# PX4FMUv2_4.net
KiCad netlist of a schematic drawn in EAGLE
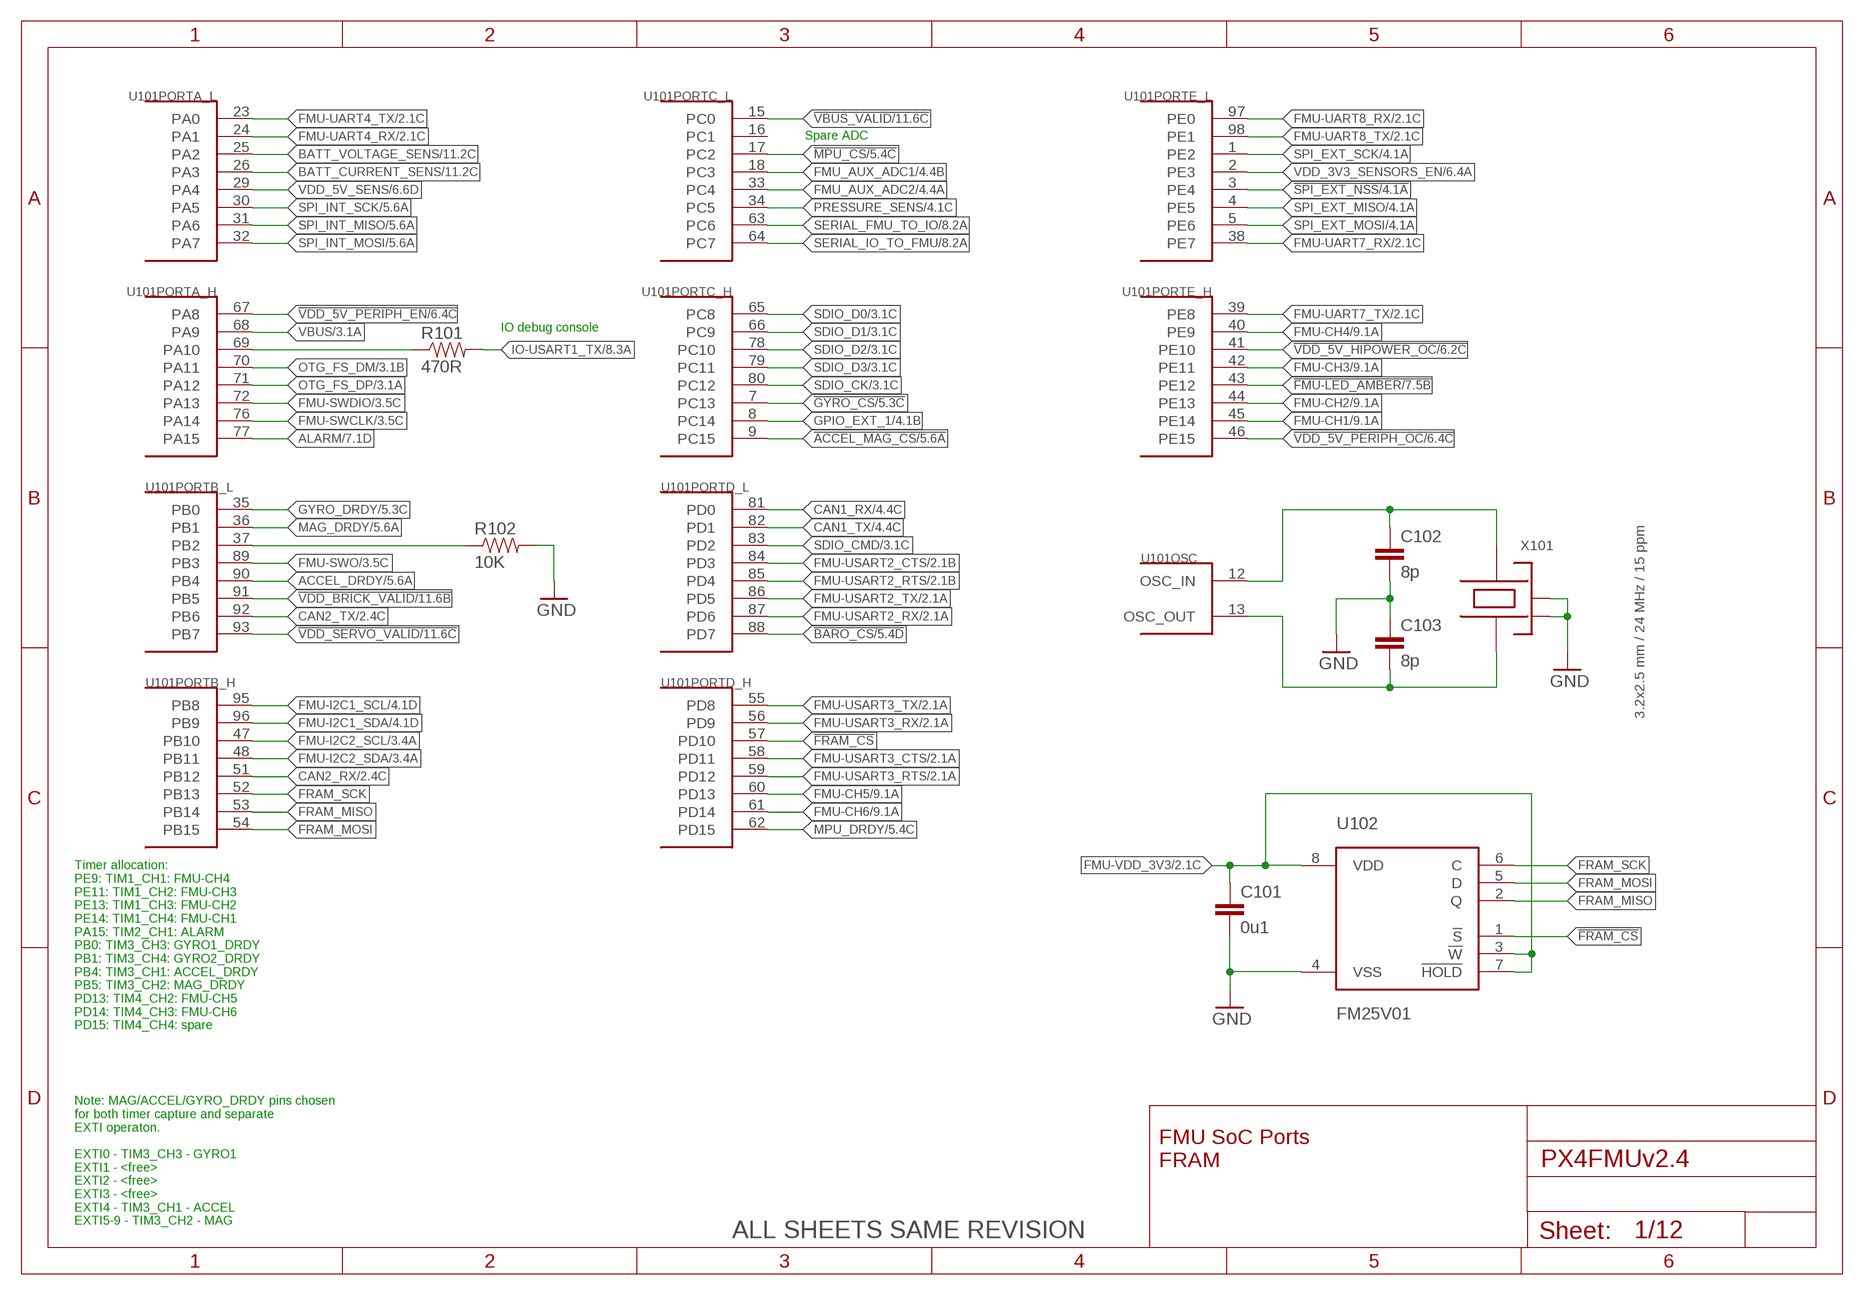
[diagram p0: schematic, sheet 1]
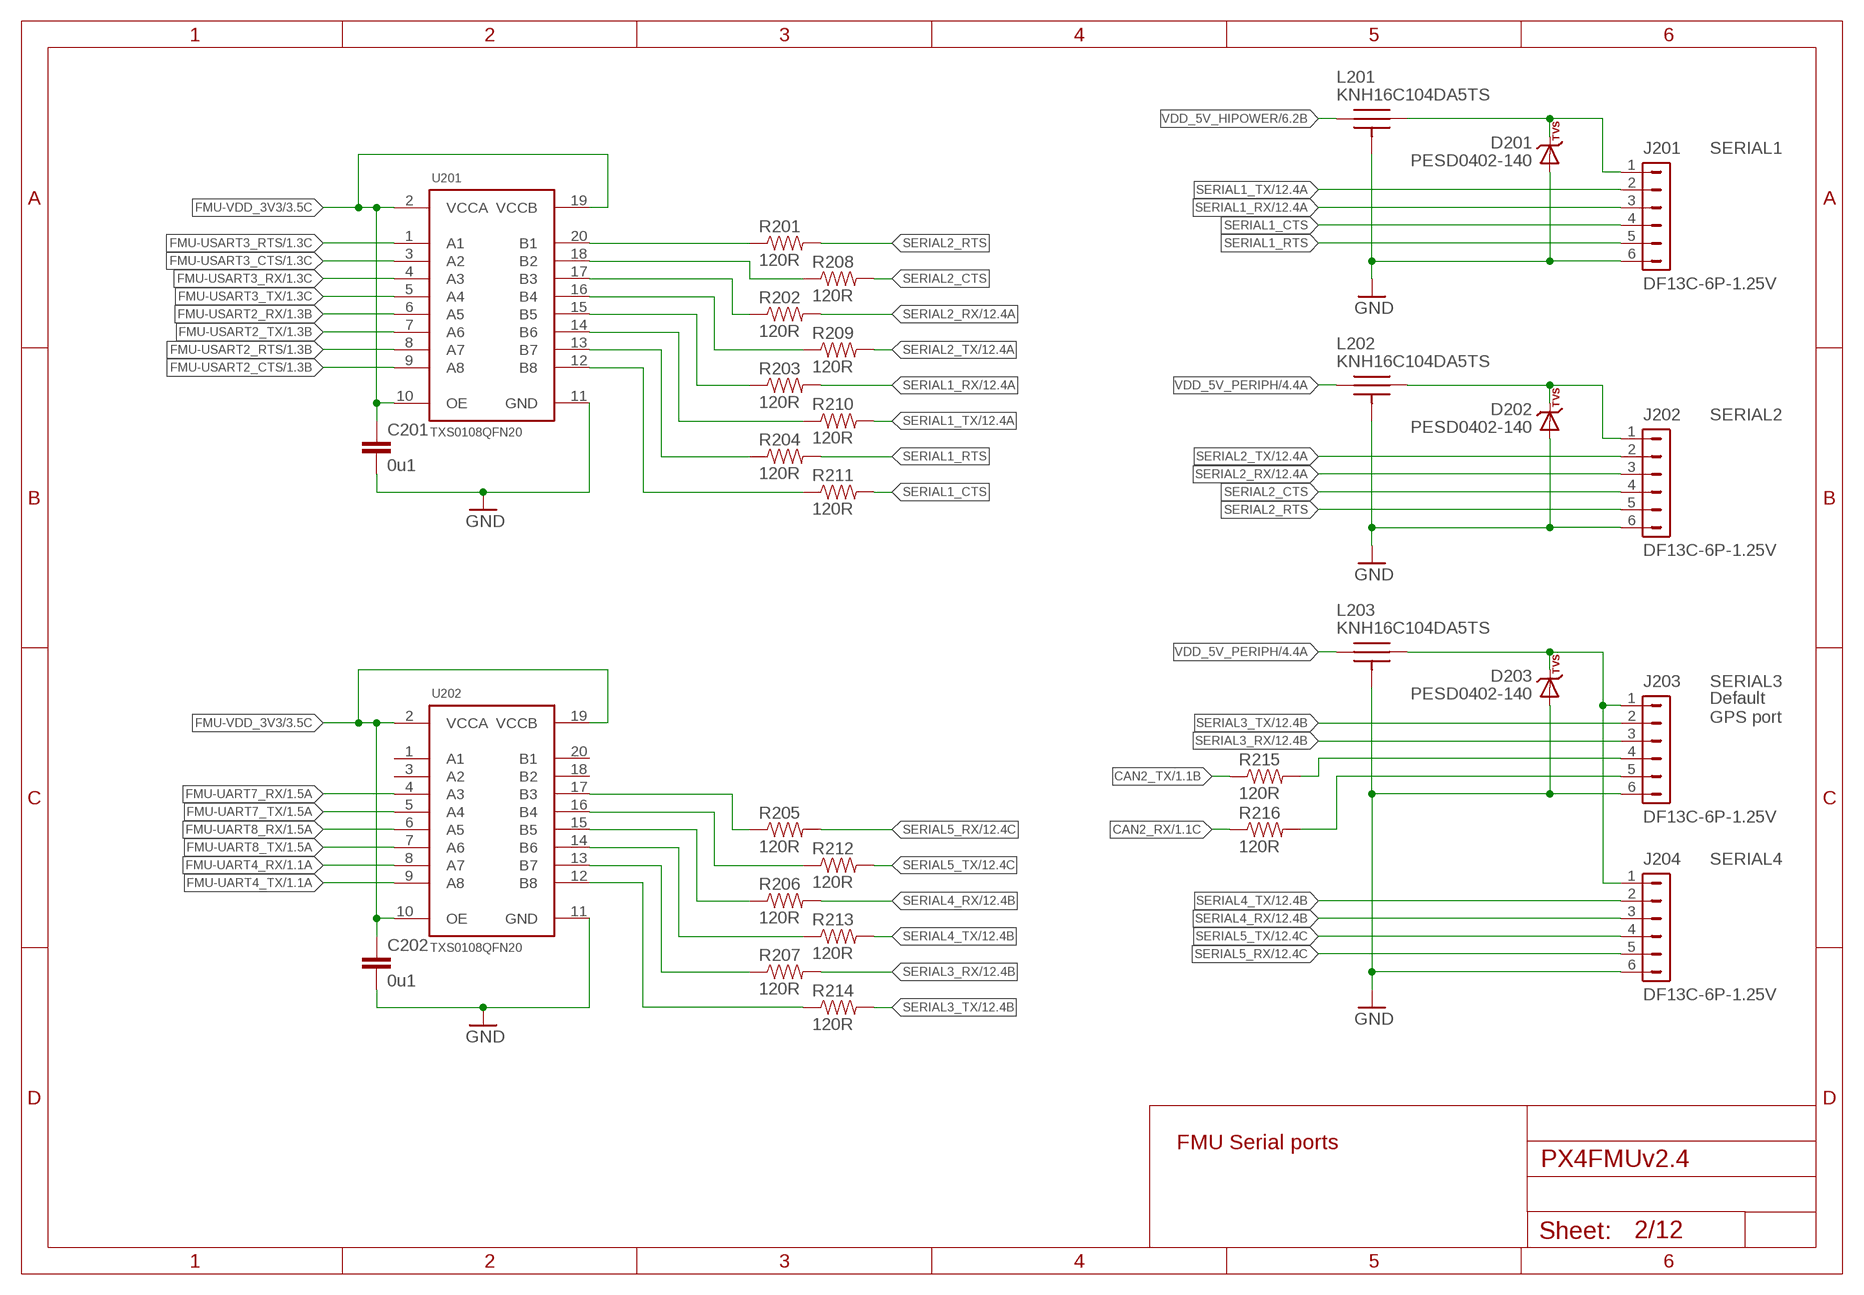
[diagram p1: schematic, sheet 2]
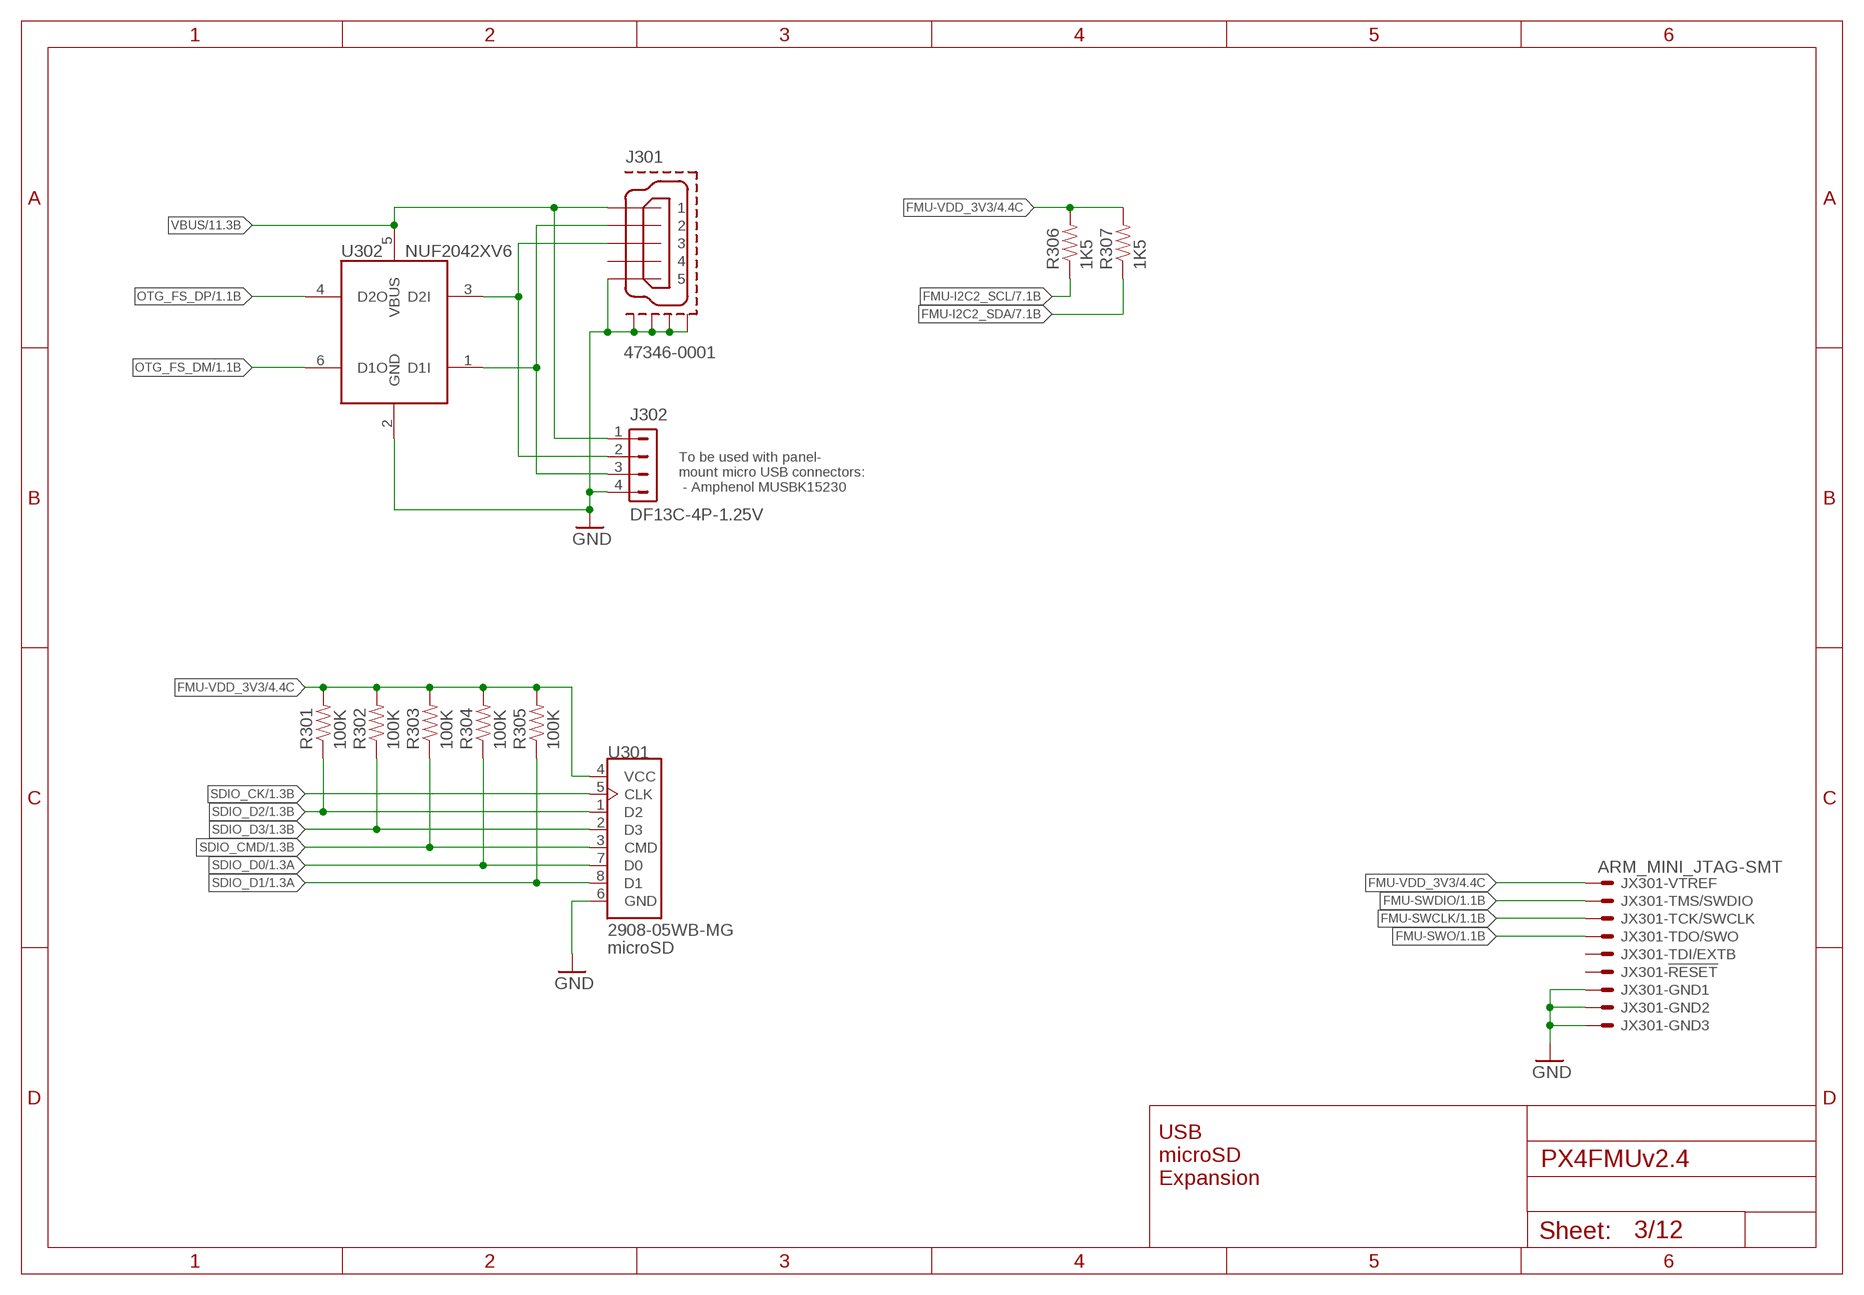
[diagram p2: schematic, sheet 3]
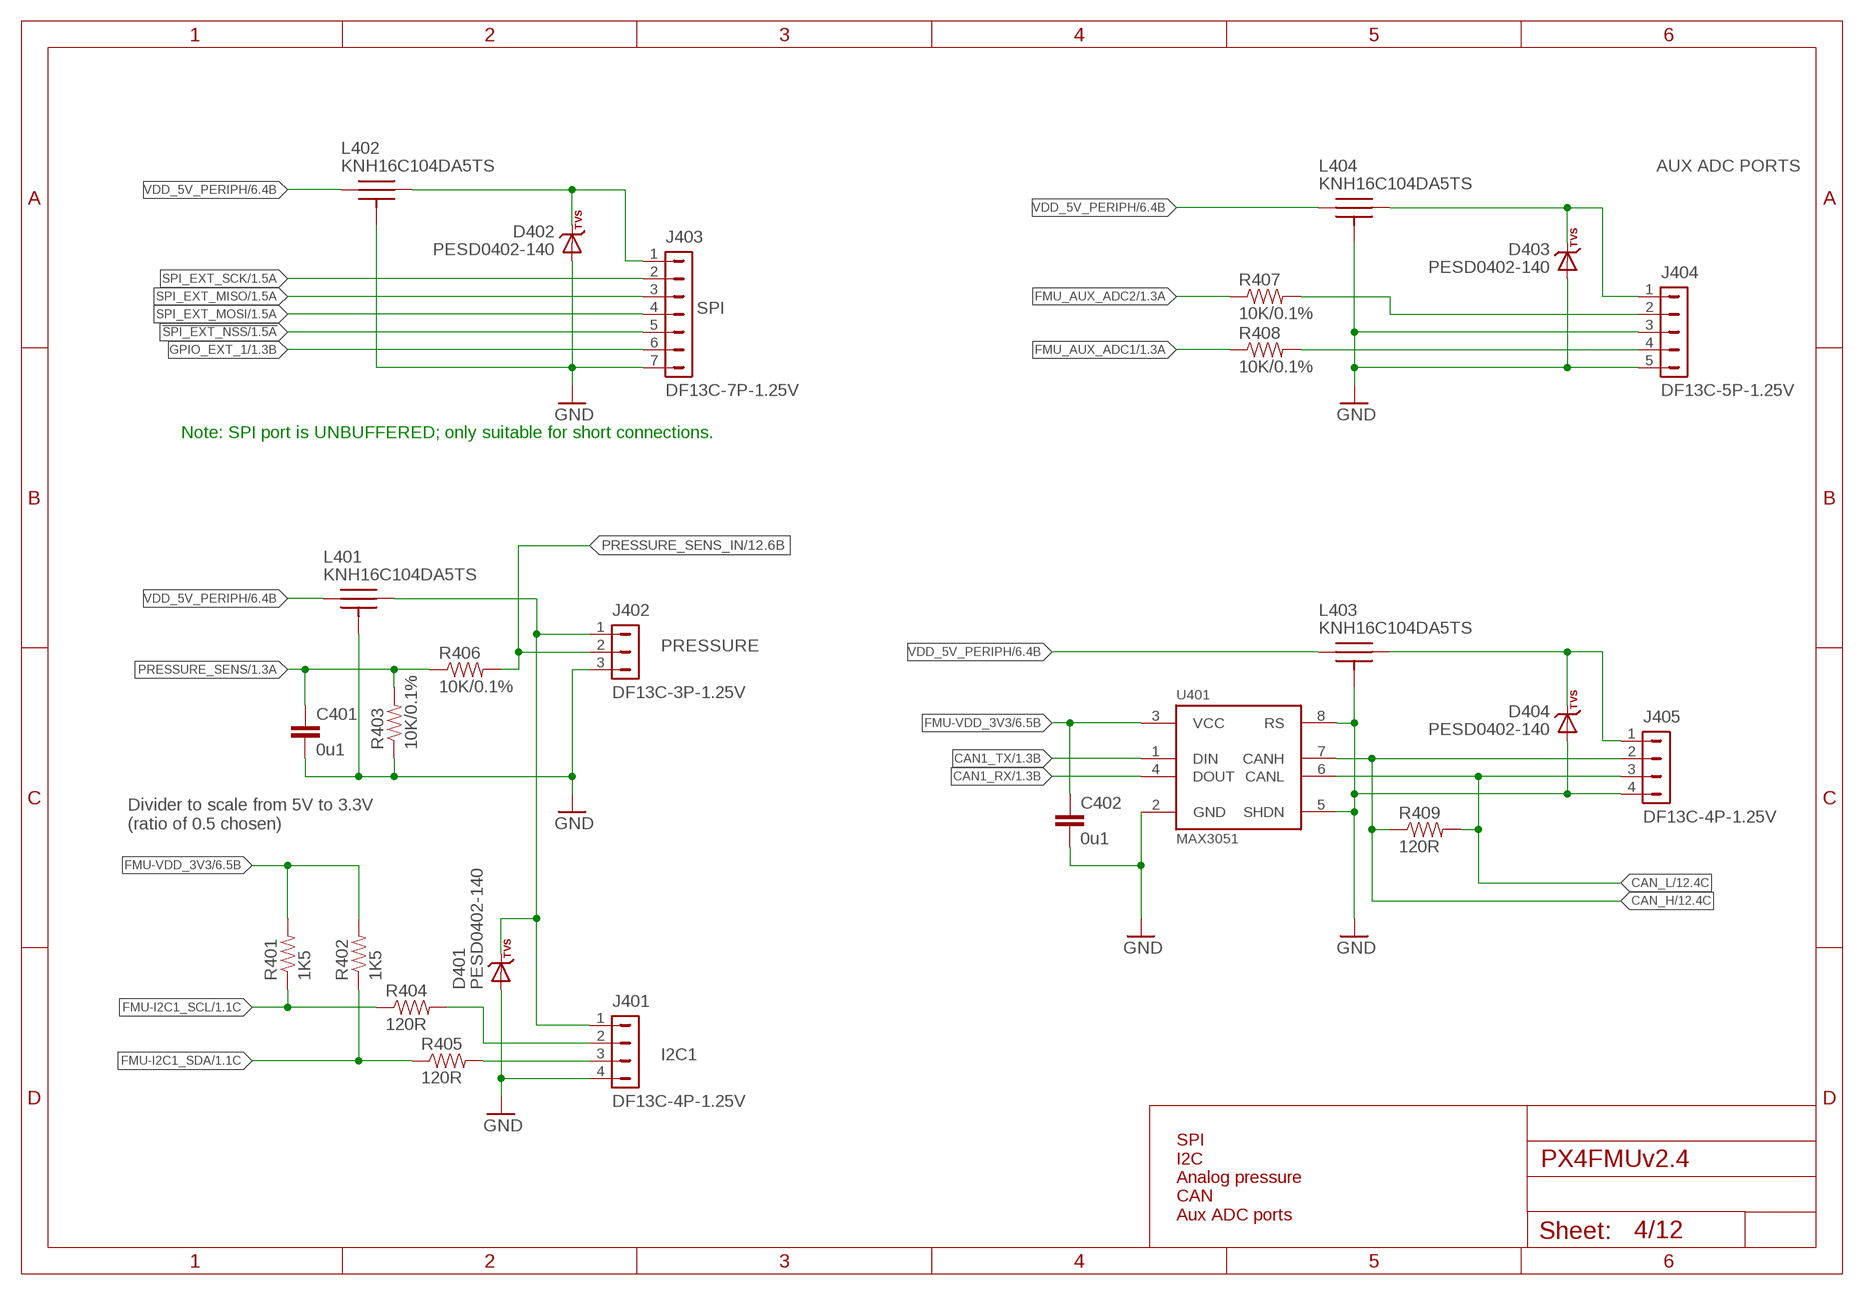
[diagram p3: schematic, sheet 4]
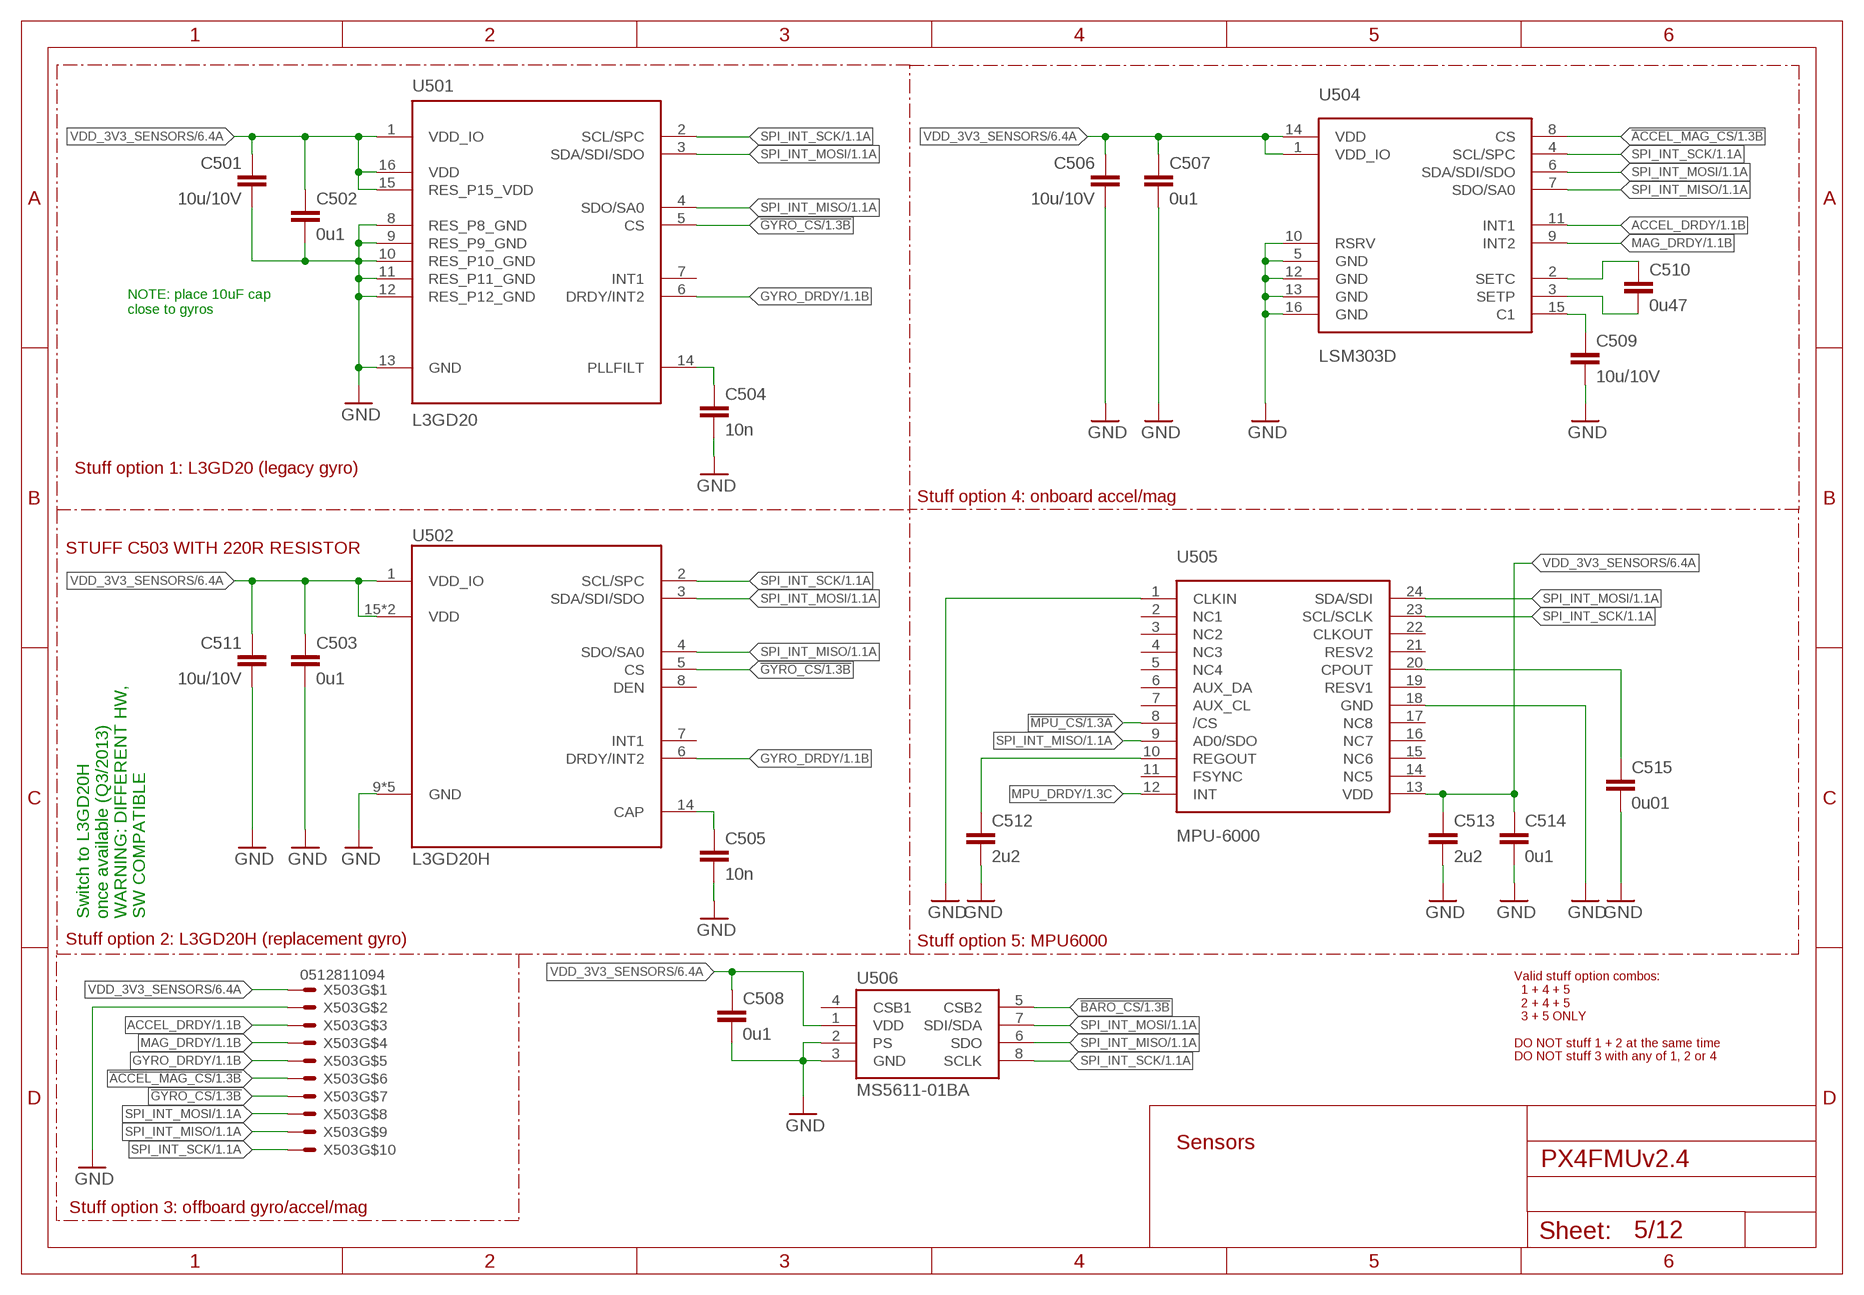
[diagram p4: schematic, sheet 5]
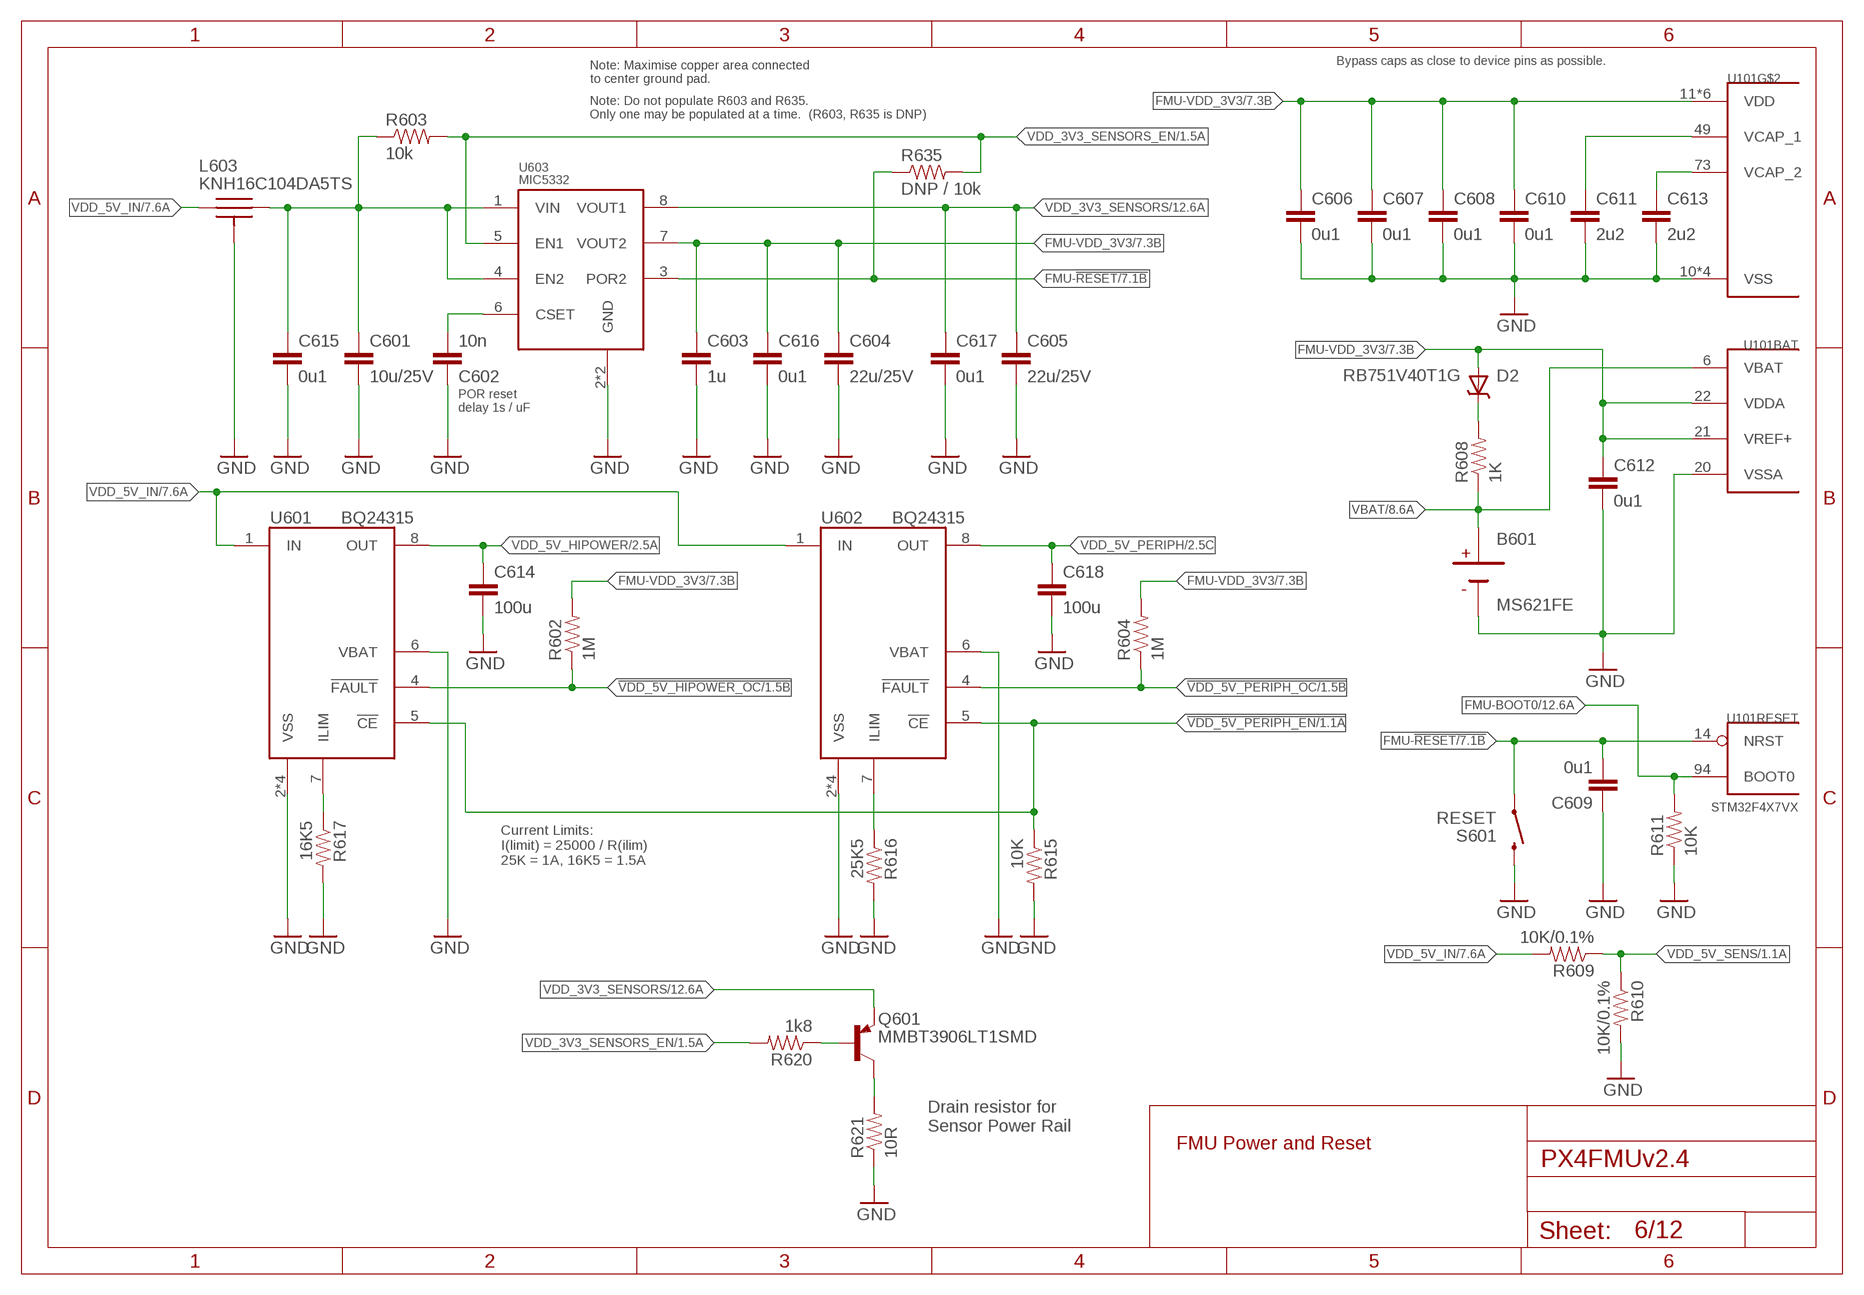
[diagram p5: schematic, sheet 6]
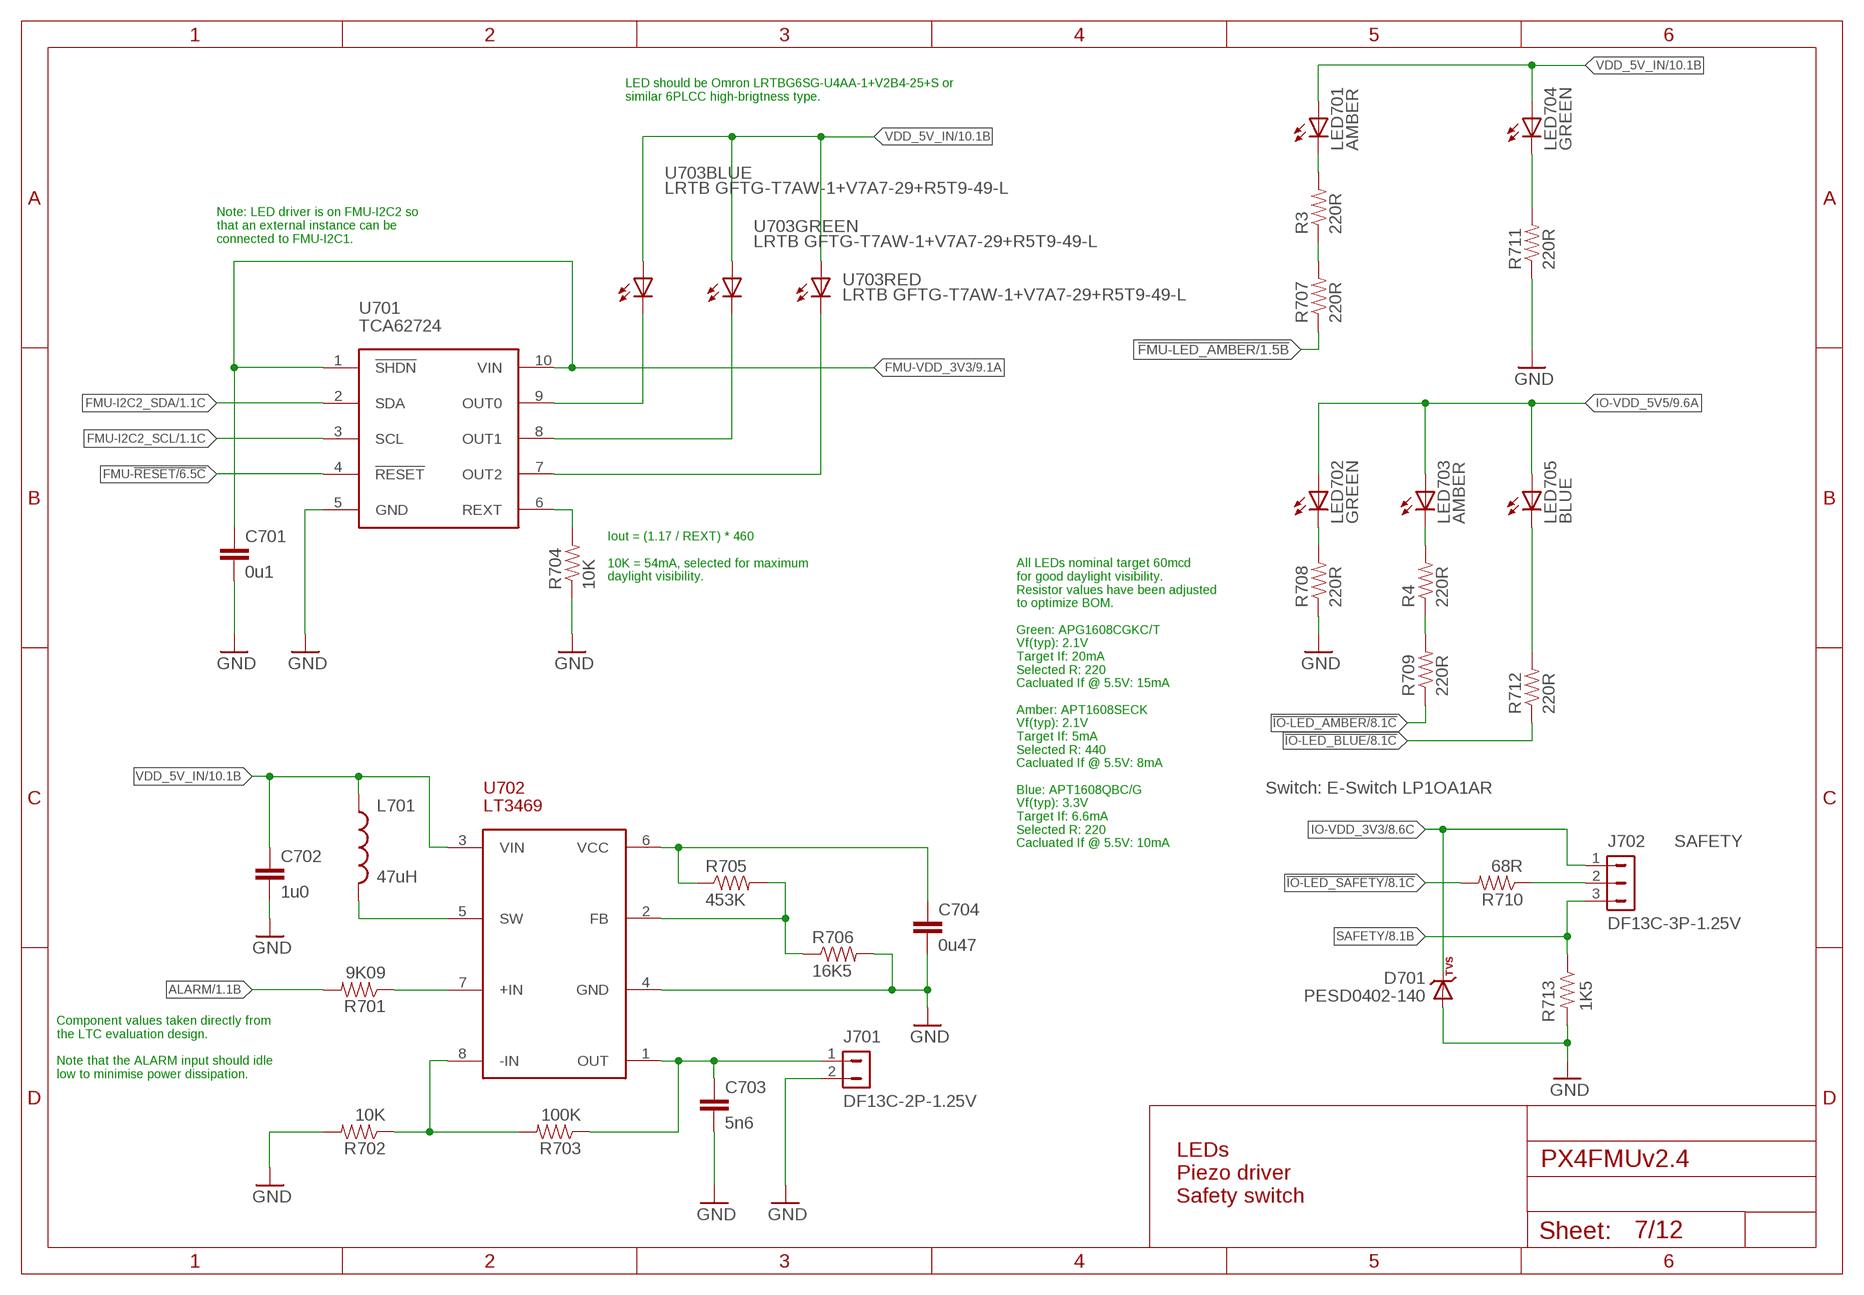
[diagram p6: schematic, sheet 7]
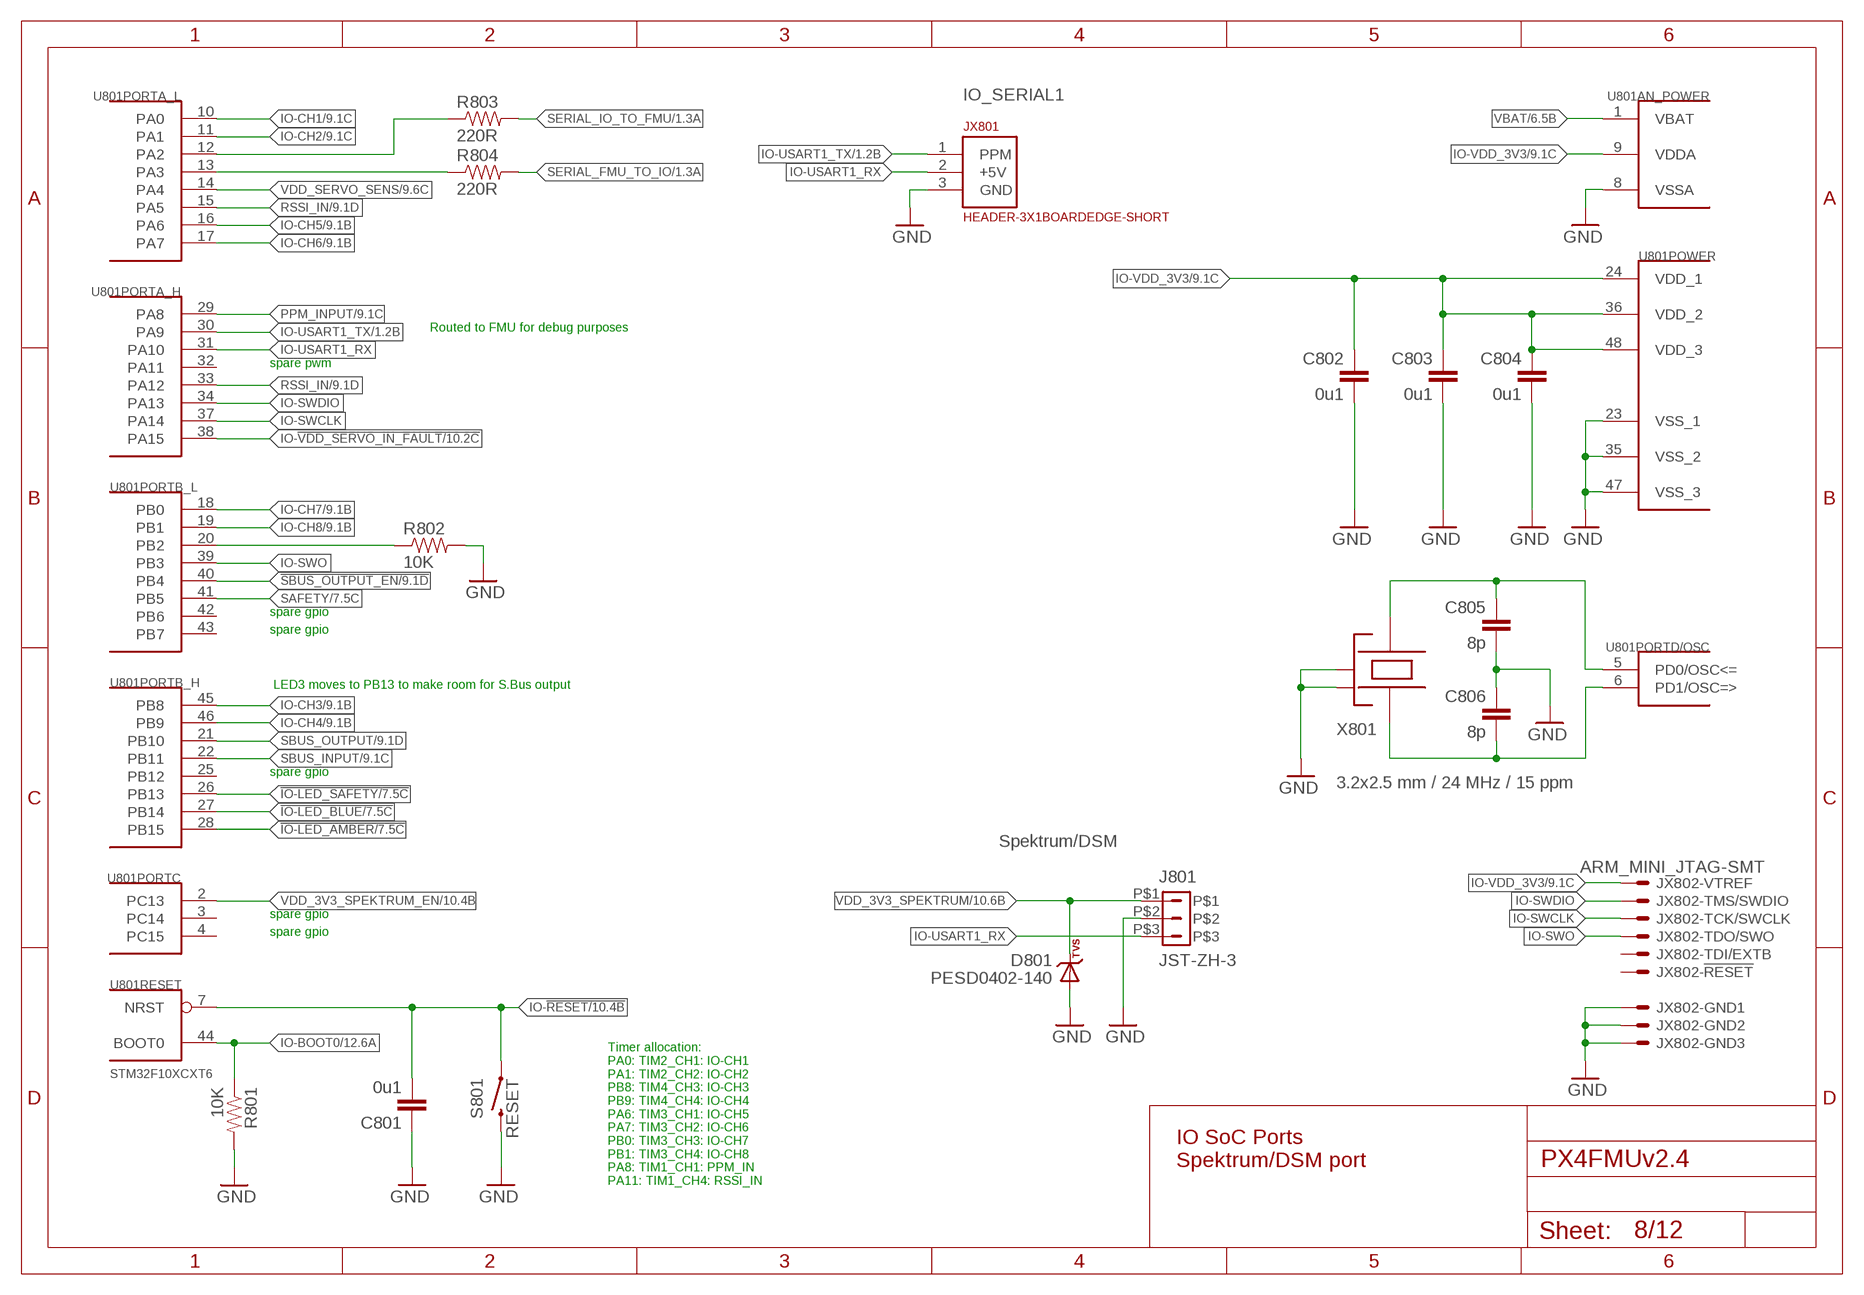
[diagram p7: schematic, sheet 8]
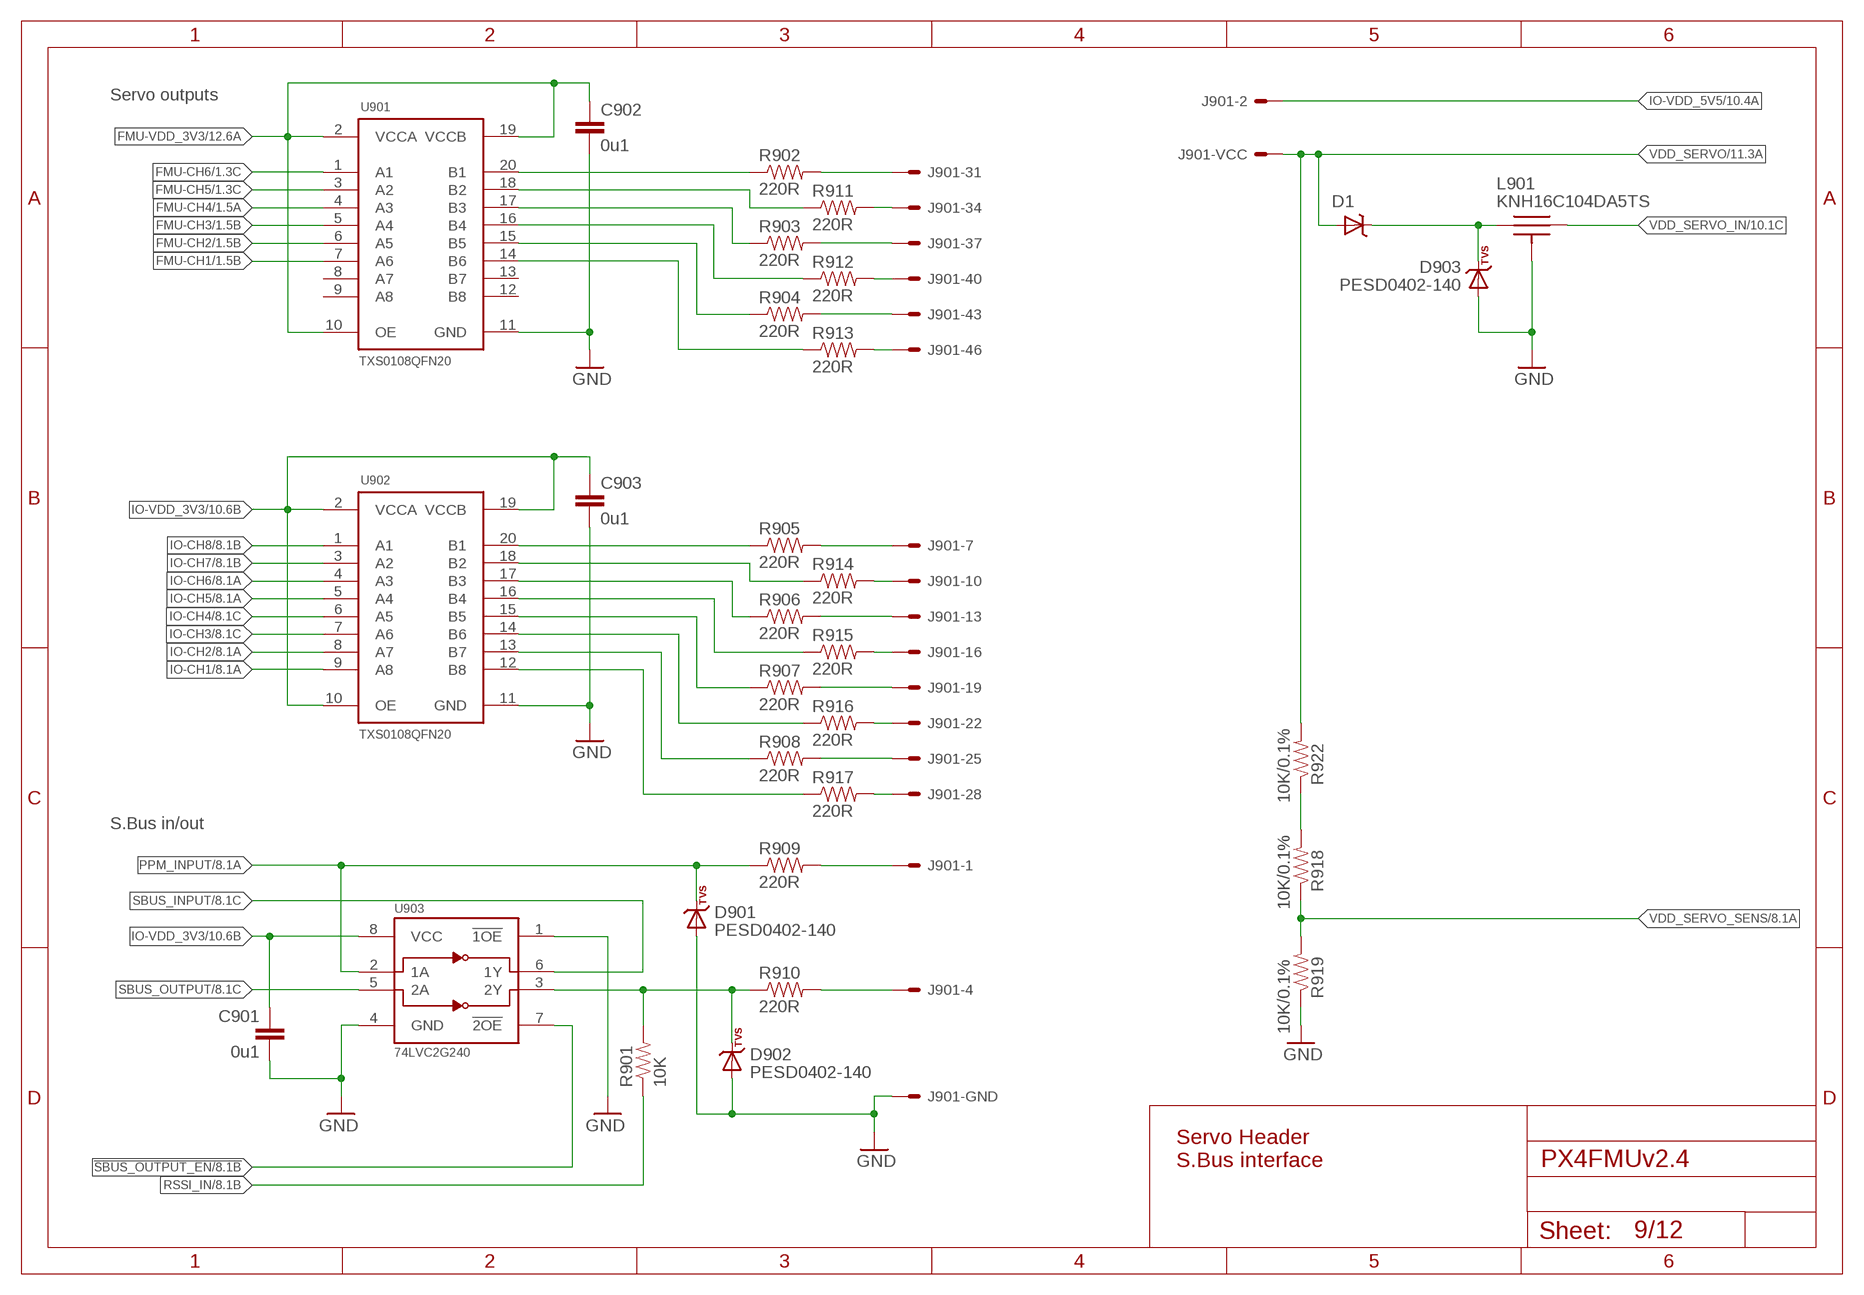
[diagram p8: schematic, sheet 9]
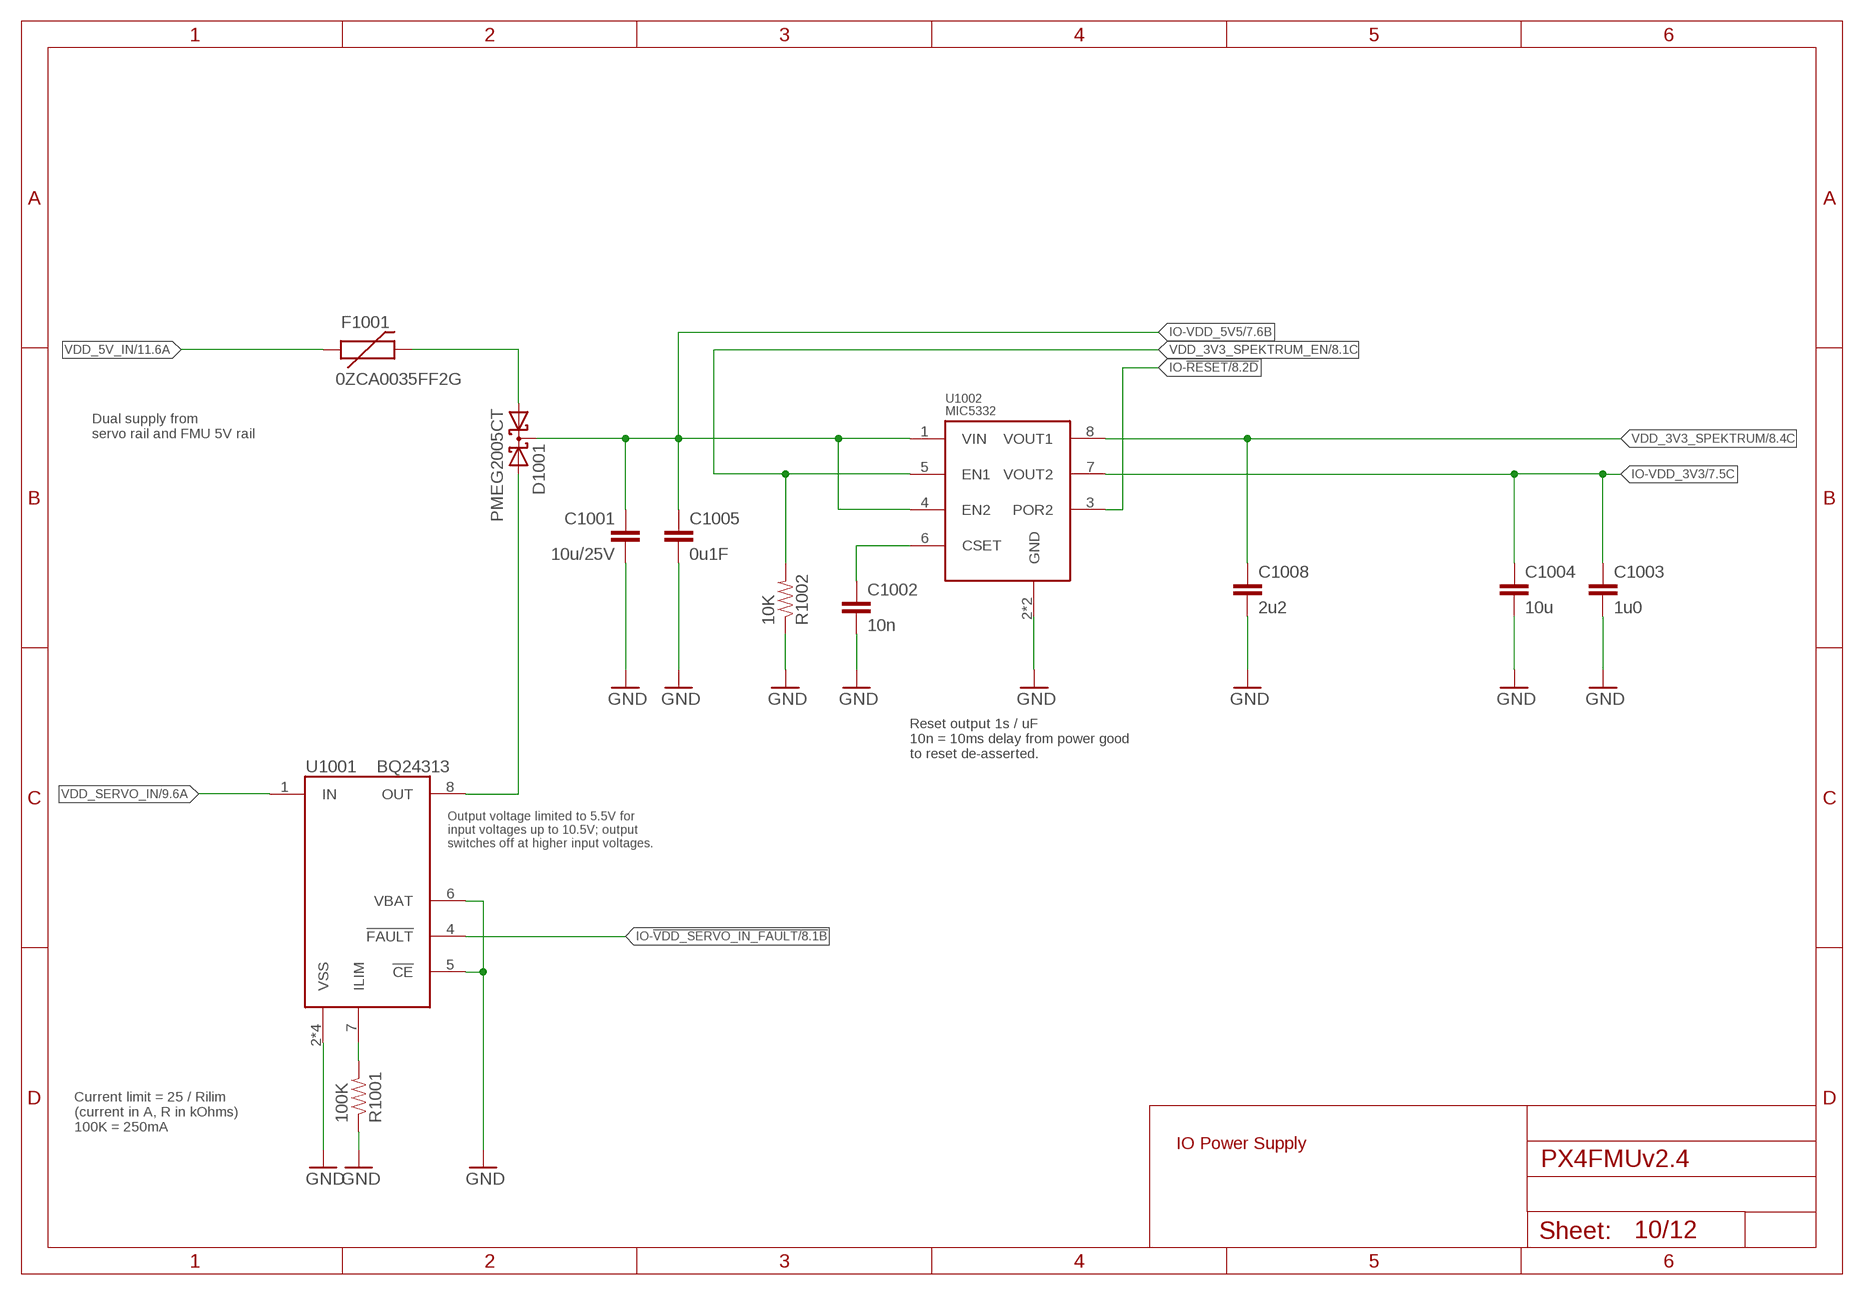
[diagram p9: schematic, sheet 10]
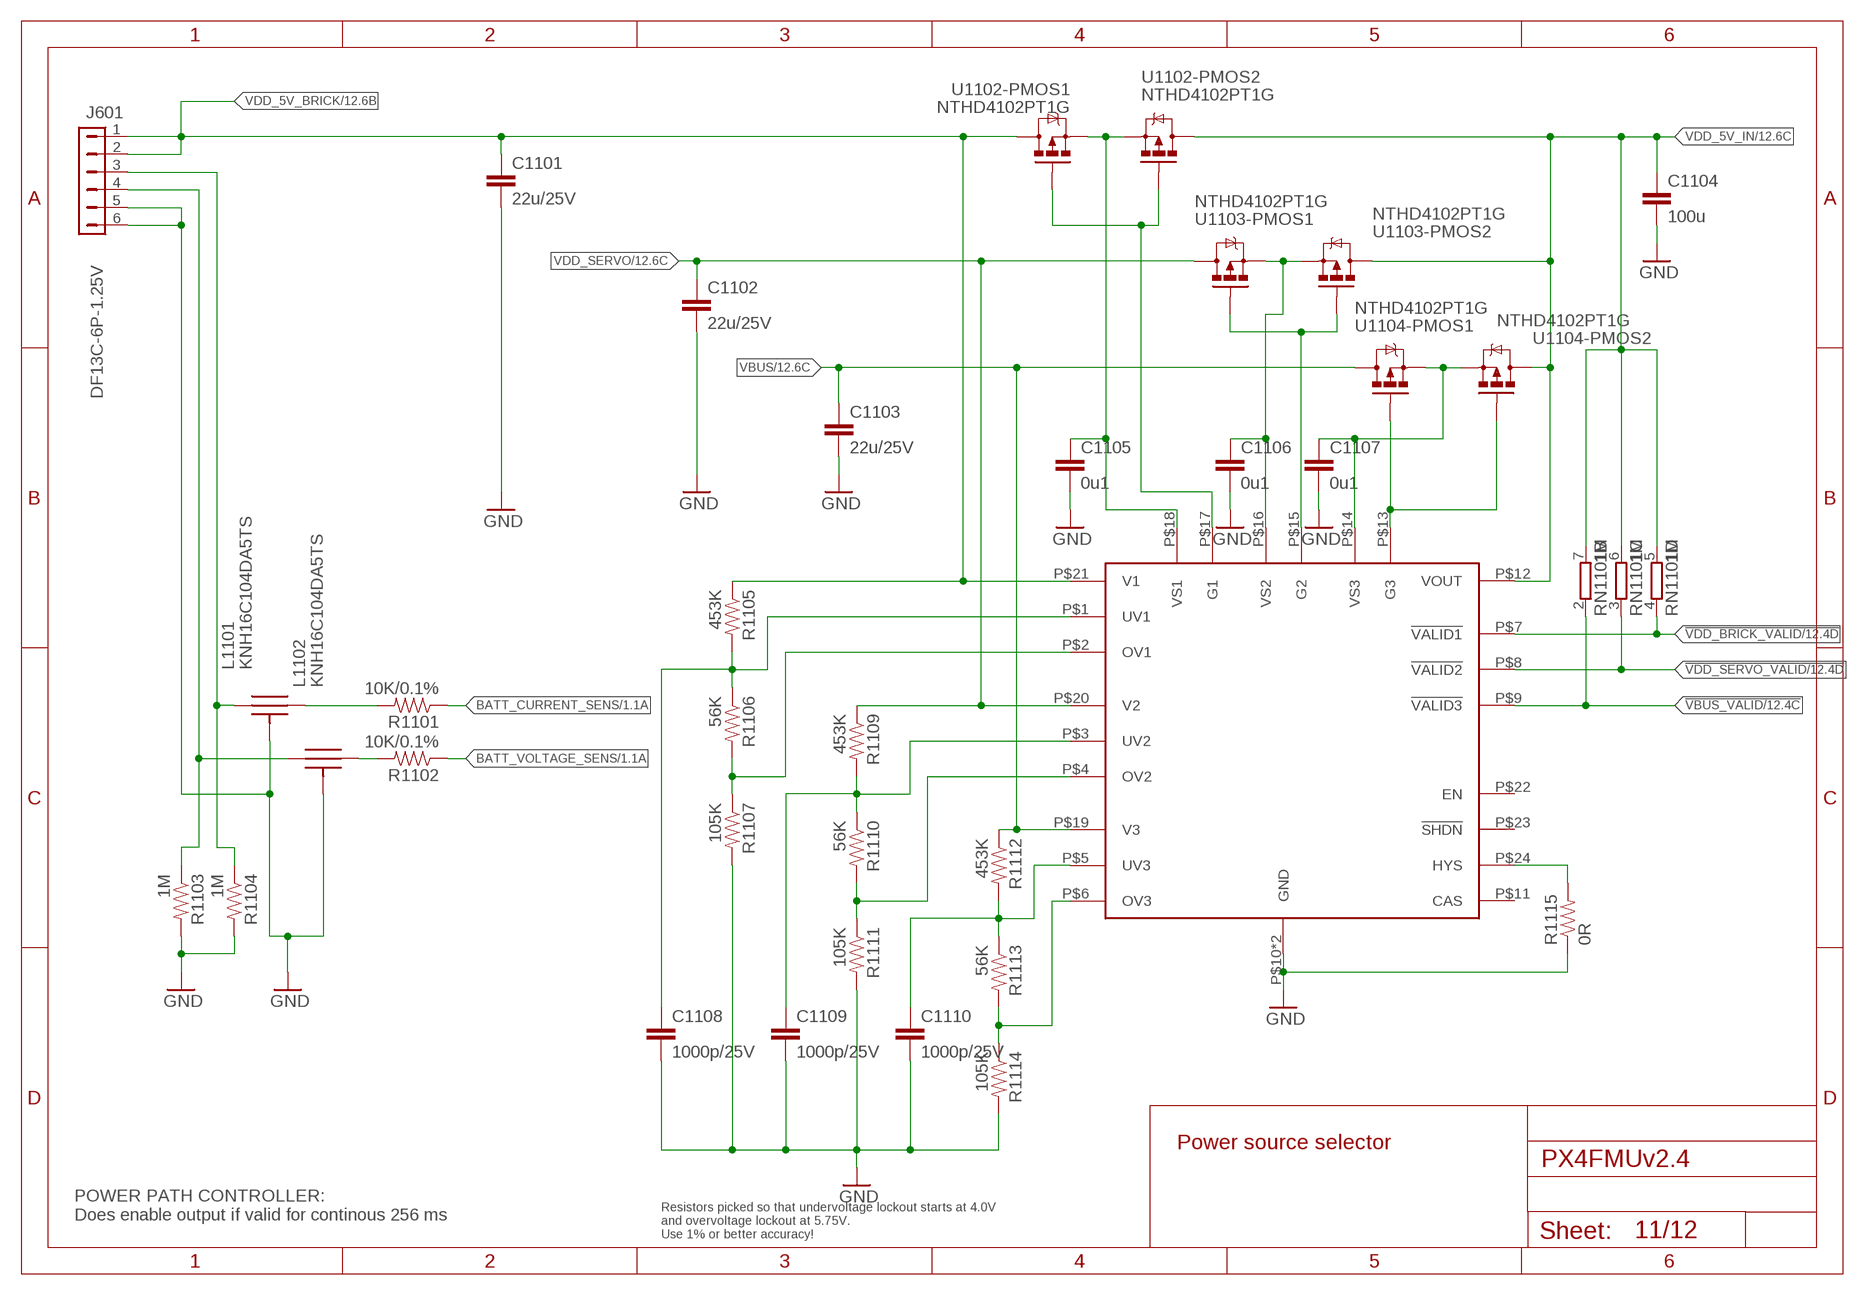
[diagram p10: schematic, sheet 11]
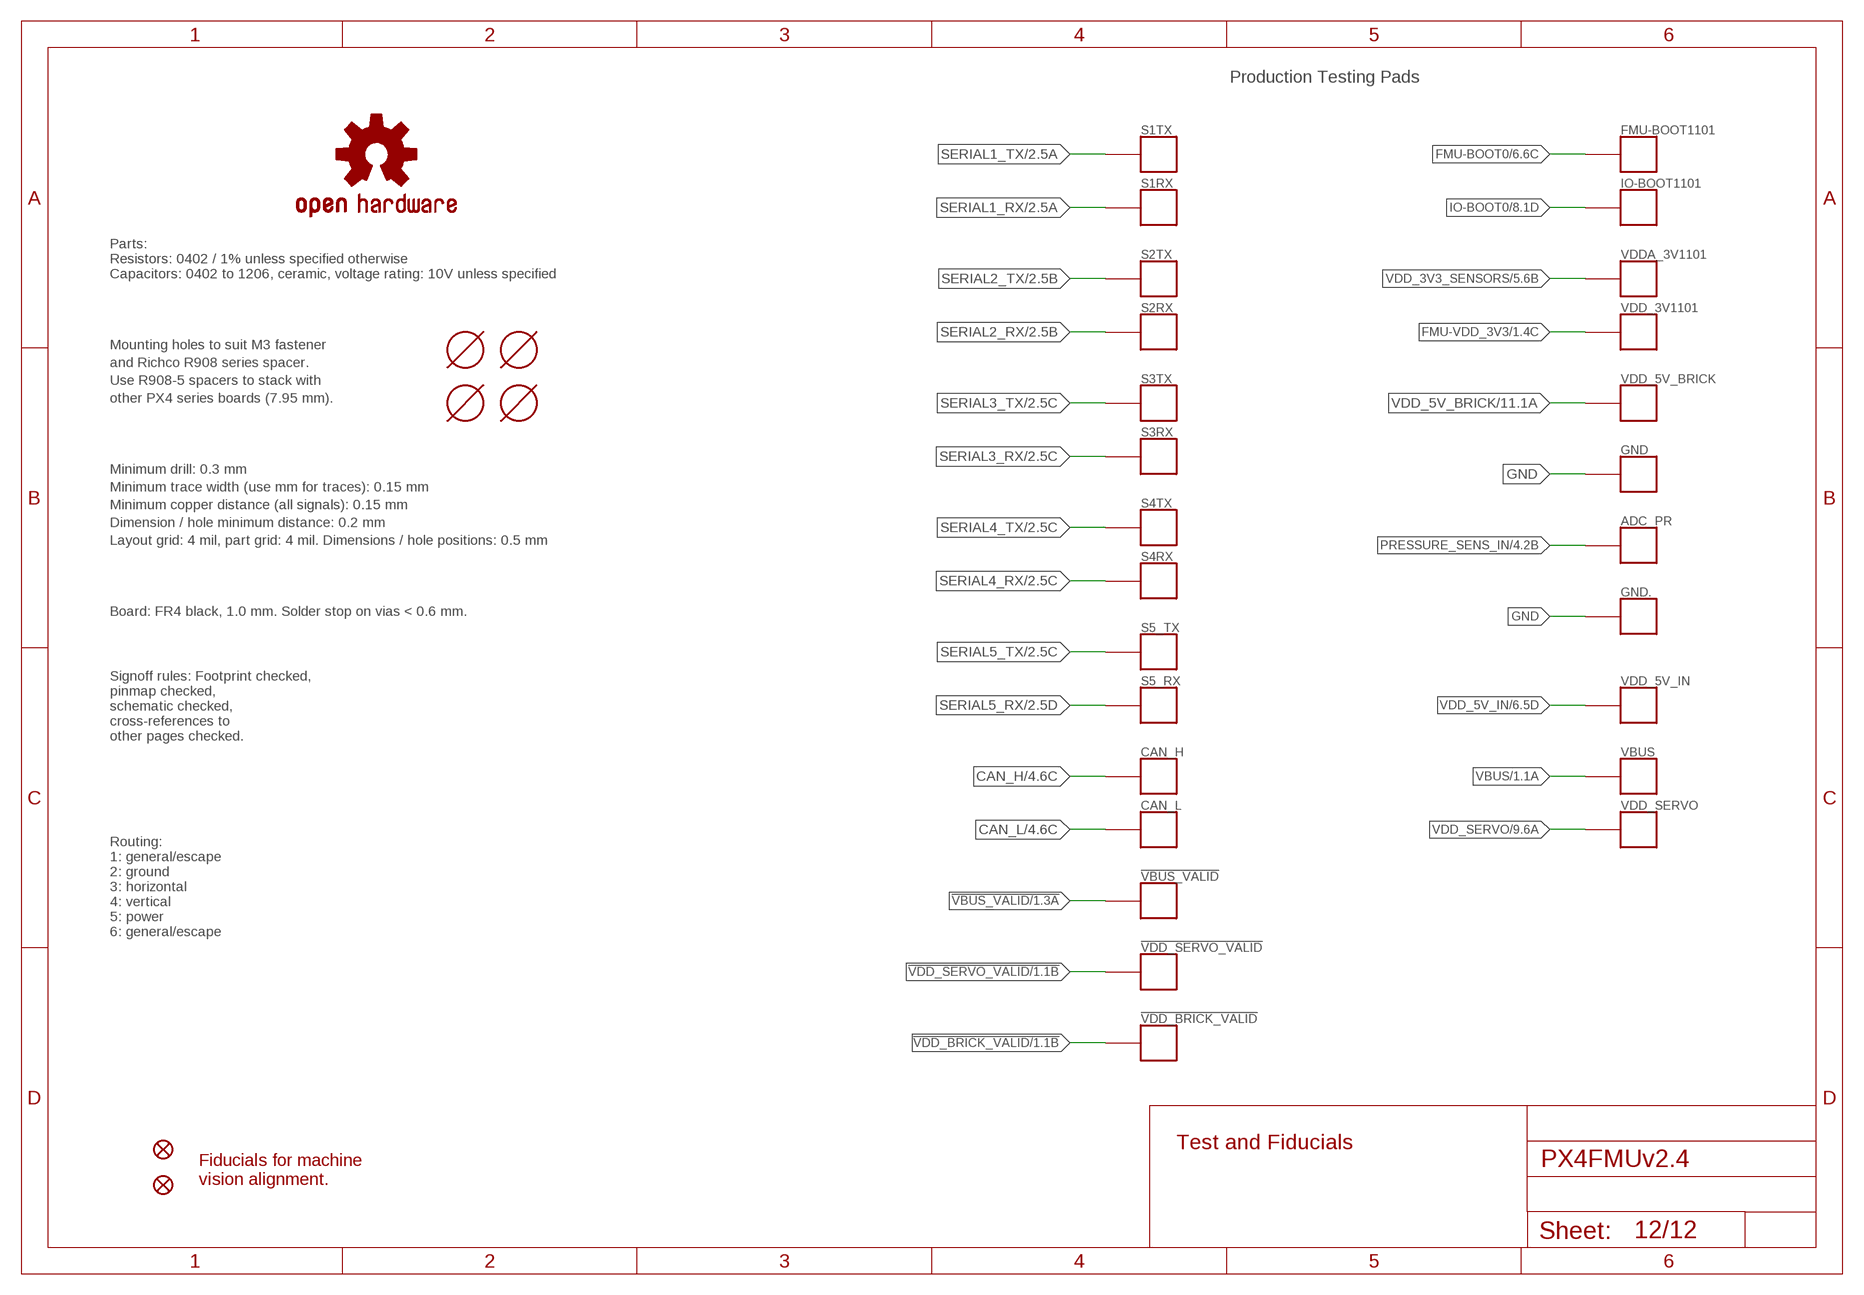
[diagram p11: schematic, sheet 12]

(export (version "E")
  (design (tool "Eeschema 10.0.6"))
  (components
    (comp (ref "!VBUS_VALID")
      (value "PAD.04")
      (footprint "eagle-import:PAD.04X.04")
      (libsource (lib "eagle-import") (part "PAD.04"))
    )
    (comp (ref "!VDD_BRICK_VALID")
      (value "PAD.04")
      (footprint "eagle-import:PAD.04X.04")
      (libsource (lib "eagle-import") (part "PAD.04"))
    )
    (comp (ref "!VDD_SERVO_VALID")
      (value "PAD.04")
      (footprint "eagle-import:PAD.04X.04")
      (libsource (lib "eagle-import") (part "PAD.04"))
    )
    (comp (ref "ADC_PR")
      (value "PAD.04")
      (footprint "eagle-import:PAD.04X.04")
      (libsource (lib "eagle-import") (part "PAD.04"))
    )
    (comp (ref "CAN_H")
      (value "PAD.04")
      (footprint "eagle-import:PAD.04X.04")
      (libsource (lib "eagle-import") (part "PAD.04"))
    )
    (comp (ref "CAN_L")
      (value "PAD.04")
      (footprint "eagle-import:PAD.04X.04")
      (libsource (lib "eagle-import") (part "PAD.04"))
    )
    (comp (ref "FMU-BOOT1101")
      (value "PAD.04")
      (footprint "eagle-import:PAD.04X.04")
      (libsource (lib "eagle-import") (part "PAD.04"))
    )
    (comp (ref "GND")
      (value "PAD.04")
      (footprint "eagle-import:PAD.04X.04")
      (libsource (lib "eagle-import") (part "PAD.04"))
    )
    (comp (ref "GND.")
      (value "PAD.04")
      (footprint "eagle-import:PAD.04X.04")
      (libsource (lib "eagle-import") (part "PAD.04"))
    )
    (comp (ref "IO-BOOT1101")
      (value "PAD.04")
      (footprint "eagle-import:PAD.04X.04")
      (libsource (lib "eagle-import") (part "PAD.04"))
    )
    (comp (ref "JP1")
      (value "FIDUCIAL1.5X3")
      (footprint "eagle-import:FIDUCIAL-1.5X3")
      (libsource (lib "eagle-import") (part "FIDUCIAL1.5X3"))
    )
    (comp (ref "JP2")
      (value "FIDUCIAL1.5X3")
      (footprint "eagle-import:FIDUCIAL-1.5X3")
      (libsource (lib "eagle-import") (part "FIDUCIAL1.5X3"))
    )
    (comp (ref "M3_MOUNT1101")
      (value "MOUNT-HOLE3.1MM")
      (footprint "eagle-import:MOUNT-HOLE3.1")
      (libsource (lib "eagle-import") (part "MOUNT-HOLE3.1MM"))
    )
    (comp (ref "M3_MOUNT1102")
      (value "MOUNT-HOLE3.1MM")
      (footprint "eagle-import:MOUNT-HOLE3.1")
      (libsource (lib "eagle-import") (part "MOUNT-HOLE3.1MM"))
    )
    (comp (ref "M3_MOUNT1103")
      (value "MOUNT-HOLE3.1MM")
      (footprint "eagle-import:MOUNT-HOLE3.1")
      (libsource (lib "eagle-import") (part "MOUNT-HOLE3.1MM"))
    )
    (comp (ref "M3_MOUNT1104")
      (value "MOUNT-HOLE3.1MM")
      (footprint "eagle-import:MOUNT-HOLE3.1")
      (libsource (lib "eagle-import") (part "MOUNT-HOLE3.1MM"))
    )
    (comp (ref "OSHW_LOGO")
      (value "OSHW-LOGOS")
      (footprint "eagle-import:OSHW-LOGO-S")
      (libsource (lib "eagle-import") (part "OSHW-LOGOS"))
    )
    (comp (ref "S1RX")
      (value "PAD.04")
      (footprint "eagle-import:PAD.04X.04")
      (libsource (lib "eagle-import") (part "PAD.04"))
    )
    (comp (ref "S1TX")
      (value "PAD.04")
      (footprint "eagle-import:PAD.04X.04")
      (libsource (lib "eagle-import") (part "PAD.04"))
    )
    (comp (ref "S2RX")
      (value "PAD.04")
      (footprint "eagle-import:PAD.04X.04")
      (libsource (lib "eagle-import") (part "PAD.04"))
    )
    (comp (ref "S2TX")
      (value "PAD.04")
      (footprint "eagle-import:PAD.04X.04")
      (libsource (lib "eagle-import") (part "PAD.04"))
    )
    (comp (ref "S3RX")
      (value "PAD.04")
      (footprint "eagle-import:PAD.04X.04")
      (libsource (lib "eagle-import") (part "PAD.04"))
    )
    (comp (ref "S3TX")
      (value "PAD.04")
      (footprint "eagle-import:PAD.04X.04")
      (libsource (lib "eagle-import") (part "PAD.04"))
    )
    (comp (ref "S4RX")
      (value "PAD.04")
      (footprint "eagle-import:PAD.04X.04")
      (libsource (lib "eagle-import") (part "PAD.04"))
    )
    (comp (ref "S4TX")
      (value "PAD.04")
      (footprint "eagle-import:PAD.04X.04")
      (libsource (lib "eagle-import") (part "PAD.04"))
    )
    (comp (ref "S5_RX")
      (value "PAD.04")
      (footprint "eagle-import:PAD.04X.04")
      (libsource (lib "eagle-import") (part "PAD.04"))
    )
    (comp (ref "S5_TX")
      (value "PAD.04")
      (footprint "eagle-import:PAD.04X.04")
      (libsource (lib "eagle-import") (part "PAD.04"))
    )
    (comp (ref "VBUS")
      (value "PAD.04")
      (footprint "eagle-import:PAD.04X.04")
      (libsource (lib "eagle-import") (part "PAD.04"))
    )
    (comp (ref "VDDA_3V1101")
      (value "PAD.04")
      (footprint "eagle-import:PAD.04X.04")
      (libsource (lib "eagle-import") (part "PAD.04"))
    )
    (comp (ref "VDD_3V1101")
      (value "PAD.04")
      (footprint "eagle-import:PAD.04X.04")
      (libsource (lib "eagle-import") (part "PAD.04"))
    )
    (comp (ref "VDD_5V_BRICK")
      (value "PAD.04")
      (footprint "eagle-import:PAD.04X.04")
      (libsource (lib "eagle-import") (part "PAD.04"))
    )
    (comp (ref "VDD_5V_IN")
      (value "PAD.04")
      (footprint "eagle-import:PAD.04X.04")
      (libsource (lib "eagle-import") (part "PAD.04"))
    )
    (comp (ref "VDD_SERVO")
      (value "PAD.04")
      (footprint "eagle-import:PAD.04X.04")
      (libsource (lib "eagle-import") (part "PAD.04"))
    )
    (comp (ref "J301")
      (value "47346-0001")
      (footprint "eagle-import:MOLEX-47346-0001")
      (libsource (lib "eagle-import") (part "MOLEX-47346-0001"))
    )
    (comp (ref "J302")
      (value "DF13C-4P-1.25V")
      (footprint "eagle-import:DF13C-4P-1.25V")
      (fields (field (name "PARTNO") "DF13C-4P-1.25V(20)"))
      (libsource (lib "eagle-import") (part "DF13-4P-1.25V"))
    )
    (comp (ref "JX301")
      (value "ARM_MINI_JTAG-SMT")
      (footprint "eagle-import:FTSH-105-01-XXX-DV-K")
      (fields (field (name "BOM") "EXCLUDE") (field (name "PARTNO") "M50-3900542"))
      (libsource (lib "eagle-import") (part "ARM_MINI_JTAG-SMT"))
    )
    (comp (ref "R301")
      (value "100K")
      (footprint "eagle-import:0402-RES")
      (fields (field (name "PARTNO") "RC0402FR-07100KL"))
      (libsource (lib "eagle-import") (part "RESISTOR0402-RES"))
    )
    (comp (ref "R302")
      (value "100K")
      (footprint "eagle-import:0402-RES")
      (fields (field (name "PARTNO") "RC0402FR-07100KL"))
      (libsource (lib "eagle-import") (part "RESISTOR0402-RES"))
    )
    (comp (ref "R303")
      (value "100K")
      (footprint "eagle-import:0402-RES")
      (fields (field (name "PARTNO") "RC0402FR-07100KL"))
      (libsource (lib "eagle-import") (part "RESISTOR0402-RES"))
    )
    (comp (ref "R304")
      (value "100K")
      (footprint "eagle-import:0402-RES")
      (fields (field (name "PARTNO") "RC0402FR-07100KL"))
      (libsource (lib "eagle-import") (part "RESISTOR0402-RES"))
    )
    (comp (ref "R305")
      (value "100K")
      (footprint "eagle-import:0402-RES")
      (fields (field (name "PARTNO") "RC0402FR-07100KL"))
      (libsource (lib "eagle-import") (part "RESISTOR0402-RES"))
    )
    (comp (ref "R306")
      (value "1K5")
      (footprint "eagle-import:0402-RES")
      (fields (field (name "PARTNO") "RC0402FR-071K5L"))
      (libsource (lib "eagle-import") (part "RESISTOR0402-RES"))
    )
    (comp (ref "R307")
      (value "1K5")
      (footprint "eagle-import:0402-RES")
      (fields (field (name "PARTNO") "RC0402FR-071K5L"))
      (libsource (lib "eagle-import") (part "RESISTOR0402-RES"))
    )
    (comp (ref "U301")
      (value "2908-05WB-MG")
      (footprint "eagle-import:MICROSD")
      (libsource (lib "eagle-import") (part "MICROSDSDI"))
    )
    (comp (ref "U302")
      (value "NUF2042XV6")
      (footprint "eagle-import:SOT563-6")
      (fields (field (name "PARTNO") "NUF2042XV6T1G"))
      (libsource (lib "eagle-import") (part "NUF2042XV6"))
    )
    (comp (ref "B601")
      (value "MS621FE")
      (footprint "eagle-import:MS621FE")
      (fields (field (name "PARTNO") "MS621FE-FL11E"))
      (libsource (lib "eagle-import") (part "MS621FE"))
    )
    (comp (ref "C601")
      (value "10u/25V")
      (footprint "eagle-import:0805-CAP")
      (fields (field (name "PARTNO") "CL21A106KAYNNNE"))
      (libsource (lib "eagle-import") (part "CAP0805"))
    )
    (comp (ref "C602")
      (value "10n")
      (footprint "eagle-import:0402-CAP")
      (fields (field (name "PARTNO") "CC0402KRX7R7BB103"))
      (libsource (lib "eagle-import") (part "CAP0402"))
    )
    (comp (ref "C603")
      (value "1u")
      (footprint "eagle-import:0603-CAP")
      (fields (field (name "PARTNO") "CC0603ZRY5V7BB105"))
      (libsource (lib "eagle-import") (part "CAP0603"))
    )
    (comp (ref "C604")
      (value "22u/25V")
      (footprint "eagle-import:0805-CAP")
      (fields (field (name "PARTNO") "CL21A226MAQNNNE"))
      (libsource (lib "eagle-import") (part "CAP0805"))
    )
    (comp (ref "C605")
      (value "22u/25V")
      (footprint "eagle-import:0805-CAP")
      (fields (field (name "PARTNO") "CL21A226MAQNNNE"))
      (libsource (lib "eagle-import") (part "CAP0805"))
    )
    (comp (ref "C606")
      (value "0u1")
      (footprint "eagle-import:0402-CAP")
      (fields (field (name "PARTNO") "CC0402ZRY5V7BB104"))
      (libsource (lib "eagle-import") (part "CAP0402"))
    )
    (comp (ref "C607")
      (value "0u1")
      (footprint "eagle-import:0402-CAP")
      (fields (field (name "PARTNO") "CC0402ZRY5V7BB104"))
      (libsource (lib "eagle-import") (part "CAP0402"))
    )
    (comp (ref "C608")
      (value "0u1")
      (footprint "eagle-import:0402-CAP")
      (fields (field (name "PARTNO") "CC0402ZRY5V7BB104"))
      (libsource (lib "eagle-import") (part "CAP0402"))
    )
    (comp (ref "C609")
      (value "0u1")
      (footprint "eagle-import:0402-CAP")
      (fields (field (name "PARTNO") "CC0402ZRY5V7BB104"))
      (libsource (lib "eagle-import") (part "CAP0402"))
    )
    (comp (ref "C610")
      (value "0u1")
      (footprint "eagle-import:0402-CAP")
      (fields (field (name "PARTNO") "CC0402ZRY5V7BB104"))
      (libsource (lib "eagle-import") (part "CAP0402"))
    )
    (comp (ref "C611")
      (value "2u2")
      (footprint "eagle-import:0603-CAP")
      (fields (field (name "PARTNO") "C1608Y5V1C225Z"))
      (libsource (lib "eagle-import") (part "CAP0603"))
    )
    (comp (ref "C612")
      (value "0u1")
      (footprint "eagle-import:0402-CAP")
      (fields (field (name "PARTNO") "CC0402ZRY5V7BB104"))
      (libsource (lib "eagle-import") (part "CAP0402"))
    )
    (comp (ref "C613")
      (value "2u2")
      (footprint "eagle-import:0603-CAP")
      (fields (field (name "PARTNO") "C1608Y5V1C225Z"))
      (libsource (lib "eagle-import") (part "CAP0603"))
    )
    (comp (ref "C614")
      (value "100u")
      (footprint "eagle-import:1206-CAP")
      (fields (field (name "PARTNO") "C3216X5R1A107M160AC"))
      (libsource (lib "eagle-import") (part "CAP1206"))
    )
    (comp (ref "C615")
      (value "0u1")
      (footprint "eagle-import:0402-CAP")
      (fields (field (name "PARTNO") "CC0402ZRY5V7BB104"))
      (libsource (lib "eagle-import") (part "CAP0402"))
    )
    (comp (ref "C616")
      (value "0u1")
      (footprint "eagle-import:0402-CAP")
      (fields (field (name "PARTNO") "CC0402ZRY5V7BB104"))
      (libsource (lib "eagle-import") (part "CAP0402"))
    )
    (comp (ref "C617")
      (value "0u1")
      (footprint "eagle-import:0402-CAP")
      (fields (field (name "PARTNO") "CC0402ZRY5V7BB104"))
      (libsource (lib "eagle-import") (part "CAP0402"))
    )
    (comp (ref "C618")
      (value "100u")
      (footprint "eagle-import:1206-CAP")
      (fields (field (name "PARTNO") "C3216X5R1A107M160AC"))
      (libsource (lib "eagle-import") (part "CAP1206"))
    )
    (comp (ref "D2")
      (value "RB751V40T1G")
      (footprint "eagle-import:SOD323")
      (libsource (lib "eagle-import") (part "DIODE-SCHOTTKY_SOD323"))
    )
    (comp (ref "L603")
      (value "KNH16C104DA5TS")
      (footprint "eagle-import:KYOCERA-KNH16-DA")
      (libsource (lib "eagle-import") (part "KNH16C104DA5TS"))
    )
    (comp (ref "Q601")
      (value "MMBT3906LT1SMD")
      (footprint "eagle-import:SOT23-BEC")
      (fields (field (name "PARTNO") "MMBT 3906 LT1"))
      (libsource (lib "eagle-import") (part "MMBT3906SMDLT1"))
    )
    (comp (ref "R602")
      (value "1M")
      (footprint "eagle-import:0402-RES")
      (fields (field (name "PARTNO") "RC0402FR-071ML"))
      (libsource (lib "eagle-import") (part "RESISTOR0402-RES"))
    )
    (comp (ref "R603")
      (value "10k")
      (footprint "eagle-import:0402-RES")
      (fields (field (name "PARTNO") "RC0402FR-0710KL"))
      (libsource (lib "eagle-import") (part "RESISTOR0402-RES"))
    )
    (comp (ref "R604")
      (value "1M")
      (footprint "eagle-import:0402-RES")
      (fields (field (name "PARTNO") "RC0402FR-071ML"))
      (libsource (lib "eagle-import") (part "RESISTOR0402-RES"))
    )
    (comp (ref "R608")
      (value "1K")
      (footprint "eagle-import:0402-RES")
      (fields (field (name "PARTNO") "RC0402FR-071KL"))
      (libsource (lib "eagle-import") (part "RESISTOR0402-RES"))
    )
    (comp (ref "R609")
      (value "10K/0.1%")
      (footprint "eagle-import:0402-RES")
      (fields (field (name "PARTNO") "ERA-2AEB103X"))
      (libsource (lib "eagle-import") (part "RESISTOR0402-RES"))
    )
    (comp (ref "R610")
      (value "10K/0.1%")
      (footprint "eagle-import:0402-RES")
      (fields (field (name "PARTNO") "ERA-2AEB103X"))
      (libsource (lib "eagle-import") (part "RESISTOR0402-RES"))
    )
    (comp (ref "R611")
      (value "10K")
      (footprint "eagle-import:0402-RES")
      (fields (field (name "PARTNO") "RC0402FR-0710KL"))
      (libsource (lib "eagle-import") (part "RESISTOR0402-RES"))
    )
    (comp (ref "R615")
      (value "10K")
      (footprint "eagle-import:0402-RES")
      (fields (field (name "PARTNO") "RC0402FR-0710KL"))
      (libsource (lib "eagle-import") (part "RESISTOR0402-RES"))
    )
    (comp (ref "R616")
      (value "25K5")
      (footprint "eagle-import:0402-RES")
      (fields (field (name "PARTNO") "RMCF0402FT25K5"))
      (libsource (lib "eagle-import") (part "RESISTOR0402-RES"))
    )
    (comp (ref "R617")
      (value "16K5")
      (footprint "eagle-import:0402-RES")
      (fields (field (name "PARTNO") "RMCF0402FT16K5"))
      (libsource (lib "eagle-import") (part "RESISTOR0402-RES"))
    )
    (comp (ref "R620")
      (value "1k8")
      (footprint "eagle-import:0402-RES")
      (fields (field (name "PARTNO") "RC1005F182CS"))
      (libsource (lib "eagle-import") (part "RESISTOR0402-RES"))
    )
    (comp (ref "R621")
      (value "10R")
      (footprint "eagle-import:0603-RES")
      (fields (field (name "PARTNO") "RC1608J100CS"))
      (libsource (lib "eagle-import") (part "RESISTOR0603-RES"))
    )
    (comp (ref "R635")
      (value "DNP / 10k")
      (footprint "eagle-import:0402-RES")
      (fields (field (name "PARTNO") "RC0402FR-0710KL"))
      (libsource (lib "eagle-import") (part "RESISTOR0402-RES"))
    )
    (comp (ref "S601")
      (value "RESET")
      (footprint "eagle-import:EVQP7J01K")
      (fields (field (name "PARTNO") "EVQP7J01K"))
      (libsource (lib "eagle-import") (part "SWITCH-MOMENTARY-2"))
    )
    (comp (ref "U101")
      (value "STM32F4X7VX")
      (footprint "eagle-import:TQFP100")
      (fields (field (name "PARTNO") "STM32F427VI"))
      (libsource (lib "eagle-import") (part "STM32F4X7VX"))
    )
    (comp (ref "U601")
      (value "BQ24315")
      (footprint "eagle-import:QFN8-DSG")
      (fields (field (name "PARTNO") "BQ24315DSGR"))
      (libsource (lib "eagle-import") (part "BQ24315"))
    )
    (comp (ref "U602")
      (value "BQ24315")
      (footprint "eagle-import:QFN8-DSG")
      (fields (field (name "PARTNO") "BQ24315DSGR"))
      (libsource (lib "eagle-import") (part "BQ24315"))
    )
    (comp (ref "U603")
      (value "MIC5332")
      (footprint "eagle-import:MLF-8-EPAD")
      (fields (field (name "PARTNO") "MIC5332-SSYMT"))
      (libsource (lib "eagle-import") (part "MIC5332"))
    )
    (comp (ref "C401")
      (value "0u1")
      (footprint "eagle-import:0402-CAP")
      (fields (field (name "PARTNO") "CC0402ZRY5V7BB104"))
      (libsource (lib "eagle-import") (part "CAP0402"))
    )
    (comp (ref "C402")
      (value "0u1")
      (footprint "eagle-import:0402-CAP")
      (fields (field (name "PARTNO") "CC0402ZRY5V7BB104"))
      (libsource (lib "eagle-import") (part "CAP0402"))
    )
    (comp (ref "D401")
      (value "PESD0402-140")
      (footprint "eagle-import:0402-TVS")
      (libsource (lib "eagle-import") (part "DIODE-TVS"))
    )
    (comp (ref "D402")
      (value "PESD0402-140")
      (footprint "eagle-import:0402-TVS")
      (libsource (lib "eagle-import") (part "DIODE-TVS"))
    )
    (comp (ref "D403")
      (value "PESD0402-140")
      (footprint "eagle-import:0402-TVS")
      (libsource (lib "eagle-import") (part "DIODE-TVS"))
    )
    (comp (ref "D404")
      (value "PESD0402-140")
      (footprint "eagle-import:0402-TVS")
      (libsource (lib "eagle-import") (part "DIODE-TVS"))
    )
    (comp (ref "J401")
      (value "DF13C-4P-1.25V")
      (footprint "eagle-import:DF13C-4P-1.25V")
      (fields (field (name "PARTNO") "DF13C-4P-1.25V(20)"))
      (libsource (lib "eagle-import") (part "DF13-4P-1.25V"))
    )
    (comp (ref "J402")
      (value "DF13C-3P-1.25V")
      (footprint "eagle-import:DF13C-3P-1.25V")
      (fields (field (name "PARTNO") "DF13C-3P-1.25V(20)"))
      (libsource (lib "eagle-import") (part "DF13-3P-1.25V"))
    )
    (comp (ref "J403")
      (value "DF13C-7P-1.25V")
      (footprint "eagle-import:DF13C-7P-1.25V")
      (fields (field (name "PARTNO") "DF13C-7P-1.25V(20)"))
      (libsource (lib "eagle-import") (part "DF13-7P-1.25V"))
    )
    (comp (ref "J404")
      (value "DF13C-5P-1.25V")
      (footprint "eagle-import:DF13C-5P-1.25V")
      (fields (field (name "PARTNO") "DF13C-5P-1.25V(20)"))
      (libsource (lib "eagle-import") (part "DF13-5P-1.25V"))
    )
    (comp (ref "J405")
      (value "DF13C-4P-1.25V")
      (footprint "eagle-import:DF13C-4P-1.25V")
      (fields (field (name "PARTNO") "DF13C-4P-1.25V(20)"))
      (libsource (lib "eagle-import") (part "DF13-4P-1.25V"))
    )
    (comp (ref "L401")
      (value "KNH16C104DA5TS")
      (footprint "eagle-import:KYOCERA-KNH16-DA")
      (libsource (lib "eagle-import") (part "KNH16C104DA5TS"))
    )
    (comp (ref "L402")
      (value "KNH16C104DA5TS")
      (footprint "eagle-import:KYOCERA-KNH16-DA")
      (libsource (lib "eagle-import") (part "KNH16C104DA5TS"))
    )
    (comp (ref "L403")
      (value "KNH16C104DA5TS")
      (footprint "eagle-import:KYOCERA-KNH16-DA")
      (libsource (lib "eagle-import") (part "KNH16C104DA5TS"))
    )
    (comp (ref "L404")
      (value "KNH16C104DA5TS")
      (footprint "eagle-import:KYOCERA-KNH16-DA")
      (libsource (lib "eagle-import") (part "KNH16C104DA5TS"))
    )
    (comp (ref "R401")
      (value "1K5")
      (footprint "eagle-import:0402-RES")
      (fields (field (name "PARTNO") "RC0402FR-071K5L"))
      (libsource (lib "eagle-import") (part "RESISTOR0402-RES"))
    )
    (comp (ref "R402")
      (value "1K5")
      (footprint "eagle-import:0402-RES")
      (fields (field (name "PARTNO") "RC0402FR-071K5L"))
      (libsource (lib "eagle-import") (part "RESISTOR0402-RES"))
    )
    (comp (ref "R403")
      (value "10K/0.1%")
      (footprint "eagle-import:0402-RES")
      (fields (field (name "PARTNO") "ERA-2AEB103X"))
      (libsource (lib "eagle-import") (part "RESISTOR0402-RES"))
    )
    (comp (ref "R404")
      (value "120R")
      (footprint "eagle-import:0402-RES")
      (fields (field (name "PARTNO") "RC0402FR-07120RL"))
      (libsource (lib "eagle-import") (part "RESISTOR0402-RES"))
    )
    (comp (ref "R405")
      (value "120R")
      (footprint "eagle-import:0402-RES")
      (fields (field (name "PARTNO") "RC0402FR-07120RL"))
      (libsource (lib "eagle-import") (part "RESISTOR0402-RES"))
    )
    (comp (ref "R406")
      (value "10K/0.1%")
      (footprint "eagle-import:0402-RES")
      (fields (field (name "PARTNO") "ERA-2AEB103X"))
      (libsource (lib "eagle-import") (part "RESISTOR0402-RES"))
    )
    (comp (ref "R407")
      (value "10K/0.1%")
      (footprint "eagle-import:0402-RES")
      (fields (field (name "PARTNO") "ERA-2AEB103X"))
      (libsource (lib "eagle-import") (part "RESISTOR0402-RES"))
    )
    (comp (ref "R408")
      (value "10K/0.1%")
      (footprint "eagle-import:0402-RES")
      (fields (field (name "PARTNO") "ERA-2AEB103X"))
      (libsource (lib "eagle-import") (part "RESISTOR0402-RES"))
    )
    (comp (ref "R409")
      (value "120R")
      (footprint "eagle-import:0402-RES")
      (fields (field (name "PARTNO") "RC0402FR-07120RL"))
      (libsource (lib "eagle-import") (part "RESISTOR0402-RES"))
    )
    (comp (ref "U401")
      (value "MAX3051")
      (footprint "eagle-import:SOT23-8")
      (fields (field (name "PARTNO") "MAX3051EKA"))
      (libsource (lib "eagle-import") (part "MAX3051MAX3051EKA"))
    )
    (comp (ref "C1101")
      (value "22u/25V")
      (footprint "eagle-import:0805-CAP")
      (fields (field (name "PARTNO") "CL21A226MAQNNNE"))
      (libsource (lib "eagle-import") (part "CAP0805"))
    )
    (comp (ref "C1102")
      (value "22u/25V")
      (footprint "eagle-import:0805-CAP")
      (fields (field (name "PARTNO") "CL21A226MAQNNNE"))
      (libsource (lib "eagle-import") (part "CAP0805"))
    )
    (comp (ref "C1103")
      (value "22u/25V")
      (footprint "eagle-import:0805-CAP")
      (fields (field (name "PARTNO") "CL21A226MAQNNNE"))
      (libsource (lib "eagle-import") (part "CAP0805"))
    )
    (comp (ref "C1104")
      (value "100u")
      (footprint "eagle-import:1206-CAP")
      (fields (field (name "PARTNO") "C3216X5R1A107M160AC"))
      (libsource (lib "eagle-import") (part "CAP1206"))
    )
    (comp (ref "C1105")
      (value "0u1")
      (footprint "eagle-import:0402-CAP")
      (fields (field (name "PARTNO") "CC0402ZRY5V7BB104"))
      (libsource (lib "eagle-import") (part "CAP0402"))
    )
    (comp (ref "C1106")
      (value "0u1")
      (footprint "eagle-import:0402-CAP")
      (fields (field (name "PARTNO") "CC0402ZRY5V7BB104"))
      (libsource (lib "eagle-import") (part "CAP0402"))
    )
    (comp (ref "C1107")
      (value "0u1")
      (footprint "eagle-import:0402-CAP")
      (fields (field (name "PARTNO") "CC0402ZRY5V7BB104"))
      (libsource (lib "eagle-import") (part "CAP0402"))
    )
    (comp (ref "C1108")
      (value "1000p/25V")
      (footprint "eagle-import:0402-CAP")
      (fields (field (name "PARTNO") "GRM1555C1E102JA01D"))
      (libsource (lib "eagle-import") (part "CAP0402"))
    )
    (comp (ref "C1109")
      (value "1000p/25V")
      (footprint "eagle-import:0402-CAP")
      (fields (field (name "PARTNO") "GRM1555C1E102JA01D"))
      (libsource (lib "eagle-import") (part "CAP0402"))
    )
    (comp (ref "C1110")
      (value "1000p/25V")
      (footprint "eagle-import:0402-CAP")
      (fields (field (name "PARTNO") "GRM1555C1E102JA01D"))
      (libsource (lib "eagle-import") (part "CAP0402"))
    )
    (comp (ref "J601")
      (value "DF13C-6P-1.25V")
      (footprint "eagle-import:DF13C-6P-1.25V")
      (fields (field (name "PARTNO") "DF13C-6P-1.25V(20)"))
      (libsource (lib "eagle-import") (part "DF13-6P-1.25V"))
    )
    (comp (ref "L1101")
      (value "KNH16C104DA5TS")
      (footprint "eagle-import:KYOCERA-KNH16-DA")
      (libsource (lib "eagle-import") (part "KNH16C104DA5TS"))
    )
    (comp (ref "L1102")
      (value "KNH16C104DA5TS")
      (footprint "eagle-import:KYOCERA-KNH16-DA")
      (libsource (lib "eagle-import") (part "KNH16C104DA5TS"))
    )
    (comp (ref "R1101")
      (value "10K/0.1%")
      (footprint "eagle-import:0402-RES")
      (fields (field (name "PARTNO") "ERA-2AEB103X"))
      (libsource (lib "eagle-import") (part "RESISTOR0402-RES"))
    )
    (comp (ref "R1102")
      (value "10K/0.1%")
      (footprint "eagle-import:0402-RES")
      (fields (field (name "PARTNO") "ERA-2AEB103X"))
      (libsource (lib "eagle-import") (part "RESISTOR0402-RES"))
    )
    (comp (ref "R1103")
      (value "1M")
      (footprint "eagle-import:0402-RES")
      (fields (field (name "PARTNO") "RC0402FR-071ML"))
      (libsource (lib "eagle-import") (part "RESISTOR0402-RES"))
    )
    (comp (ref "R1104")
      (value "1M")
      (footprint "eagle-import:0402-RES")
      (fields (field (name "PARTNO") "RC0402FR-071ML"))
      (libsource (lib "eagle-import") (part "RESISTOR0402-RES"))
    )
    (comp (ref "R1105")
      (value "453K")
      (footprint "eagle-import:0402-RES")
      (fields (field (name "PARTNO") "RMCF0402FT453K"))
      (libsource (lib "eagle-import") (part "RESISTOR0402-RES"))
    )
    (comp (ref "R1106")
      (value "56K")
      (footprint "eagle-import:0402-RES")
      (fields (field (name "PARTNO") "ERA-2AEB563X"))
      (libsource (lib "eagle-import") (part "RESISTOR0402-RES"))
    )
    (comp (ref "R1107")
      (value "105K")
      (footprint "eagle-import:0402-RES")
      (fields (field (name "PARTNO") "ERJ-2RKF1053X"))
      (libsource (lib "eagle-import") (part "RESISTOR0402-RES"))
    )
    (comp (ref "R1109")
      (value "453K")
      (footprint "eagle-import:0402-RES")
      (fields (field (name "PARTNO") "RMCF0402FT453K"))
      (libsource (lib "eagle-import") (part "RESISTOR0402-RES"))
    )
    (comp (ref "R1110")
      (value "56K")
      (footprint "eagle-import:0402-RES")
      (fields (field (name "PARTNO") "ERA-2AEB563X"))
      (libsource (lib "eagle-import") (part "RESISTOR0402-RES"))
    )
    (comp (ref "R1111")
      (value "105K")
      (footprint "eagle-import:0402-RES")
      (fields (field (name "PARTNO") "ERJ-2RKF1053X"))
      (libsource (lib "eagle-import") (part "RESISTOR0402-RES"))
    )
    (comp (ref "R1112")
      (value "453K")
      (footprint "eagle-import:0402-RES")
      (fields (field (name "PARTNO") "RMCF0402FT453K"))
      (libsource (lib "eagle-import") (part "RESISTOR0402-RES"))
    )
    (comp (ref "R1113")
      (value "56K")
      (footprint "eagle-import:0402-RES")
      (fields (field (name "PARTNO") "ERA-2AEB563X"))
      (libsource (lib "eagle-import") (part "RESISTOR0402-RES"))
    )
    (comp (ref "R1114")
      (value "105K")
      (footprint "eagle-import:0402-RES")
      (fields (field (name "PARTNO") "ERJ-2RKF1053X"))
      (libsource (lib "eagle-import") (part "RESISTOR0402-RES"))
    )
    (comp (ref "R1115")
      (value "0R")
      (footprint "eagle-import:0402-RES")
      (fields (field (name "PARTNO") "ERJ-2GE0R00X"))
      (libsource (lib "eagle-import") (part "RESISTOR0402-RES"))
    )
    (comp (ref "RN1101")
      (value "1M")
      (footprint "eagle-import:EXB28V")
      (fields (field (name "PARTNO") "EXB-28V105JX"))
      (libsource (lib "eagle-import") (part "4R-NEXB28V"))
    )
    (comp (ref "U1101")
      (value "LTC4417")
      (footprint "eagle-import:MO-220")
      (fields (field (name "PARTNO") "LTC4417IUF#PBF"))
      (libsource (lib "eagle-import") (part "LTC4117"))
    )
    (comp (ref "U1102")
      (value "NTHD4102PT1G")
      (footprint "eagle-import:1206-8")
      (fields (field (name "PARTNO") "NTHD4102PT1G"))
      (libsource (lib "eagle-import") (part "MOSFET-DUAL-PCHANNEL-CHIPFET"))
    )
    (comp (ref "U1103")
      (value "NTHD4102PT1G")
      (footprint "eagle-import:1206-8")
      (fields (field (name "PARTNO") "NTHD4102PT1G"))
      (libsource (lib "eagle-import") (part "MOSFET-DUAL-PCHANNEL-CHIPFET"))
    )
    (comp (ref "U1104")
      (value "NTHD4102PT1G")
      (footprint "eagle-import:1206-8")
      (fields (field (name "PARTNO") "NTHD4102PT1G"))
      (libsource (lib "eagle-import") (part "MOSFET-DUAL-PCHANNEL-CHIPFET"))
    )
    (comp (ref "C501")
      (value "10u/10V")
      (footprint "eagle-import:0805-CAP")
      (fields (field (name "PARTNO") "CC0805ZKY5V6BB106"))
      (libsource (lib "eagle-import") (part "CAP0805"))
    )
    (comp (ref "C502")
      (value "0u1")
      (footprint "eagle-import:0402-CAP")
      (fields (field (name "PARTNO") "CC0402ZRY5V7BB104"))
      (libsource (lib "eagle-import") (part "CAP0402"))
    )
    (comp (ref "C503")
      (value "0u1")
      (footprint "eagle-import:0402-CAP")
      (fields (field (name "PARTNO") "CC0402ZRY5V7BB104"))
      (libsource (lib "eagle-import") (part "CAP0402"))
    )
    (comp (ref "C504")
      (value "10n")
      (footprint "eagle-import:0402-CAP")
      (fields (field (name "PARTNO") "CC0402KRX7R7BB103"))
      (libsource (lib "eagle-import") (part "CAP0402"))
    )
    (comp (ref "C505")
      (value "10n")
      (footprint "eagle-import:0402-CAP")
      (fields (field (name "PARTNO") "CC0402KRX7R7BB103"))
      (libsource (lib "eagle-import") (part "CAP0402"))
    )
    (comp (ref "C506")
      (value "10u/10V")
      (footprint "eagle-import:0805-CAP")
      (fields (field (name "PARTNO") "CC0805ZKY5V6BB106"))
      (libsource (lib "eagle-import") (part "CAP0805"))
    )
    (comp (ref "C507")
      (value "0u1")
      (footprint "eagle-import:0402-CAP")
      (fields (field (name "PARTNO") "CC0402ZRY5V7BB104"))
      (libsource (lib "eagle-import") (part "CAP0402"))
    )
    (comp (ref "C508")
      (value "0u1")
      (footprint "eagle-import:0402-CAP")
      (fields (field (name "PARTNO") "CC0402ZRY5V7BB104"))
      (libsource (lib "eagle-import") (part "CAP0402"))
    )
    (comp (ref "C509")
      (value "10u/10V")
      (footprint "eagle-import:0805-CAP")
      (fields (field (name "PARTNO") "CC0805ZKY5V6BB106"))
      (libsource (lib "eagle-import") (part "CAP0805"))
    )
    (comp (ref "C510")
      (value "0u47")
      (footprint "eagle-import:0402-CAP")
      (fields (field (name "PARTNO") "C1005X5R1C474K050BC"))
      (libsource (lib "eagle-import") (part "CAP0402"))
    )
    (comp (ref "C511")
      (value "10u/10V")
      (footprint "eagle-import:0805-CAP")
      (fields (field (name "PARTNO") "CC0805ZKY5V6BB106"))
      (libsource (lib "eagle-import") (part "CAP0805"))
    )
    (comp (ref "C512")
      (value "2u2")
      (footprint "eagle-import:0603-CAP")
      (fields (field (name "PARTNO") "CC0402ZRY5V7BB104"))
      (libsource (lib "eagle-import") (part "CAP0603"))
    )
    (comp (ref "C513")
      (value "2u2")
      (footprint "eagle-import:0603-CAP")
      (fields (field (name "PARTNO") "CC0402ZRY5V7BB104"))
      (libsource (lib "eagle-import") (part "CAP0603"))
    )
    (comp (ref "C514")
      (value "0u1")
      (footprint "eagle-import:0402-CAP")
      (fields (field (name "PARTNO") "CC0402ZRY5V7BB104"))
      (libsource (lib "eagle-import") (part "CAP0402"))
    )
    (comp (ref "C515")
      (value "0u01")
      (footprint "eagle-import:0603-CAP")
      (fields (field (name "PARTNO") "GRM155R71E103JA01J"))
      (libsource (lib "eagle-import") (part "CAP0603"))
    )
    (comp (ref "U501")
      (value "L3GD20")
      (footprint "eagle-import:L3G4200DH-MAN")
      (libsource (lib "eagle-import") (part "L3G4200DH-LL"))
    )
    (comp (ref "U502")
      (value "L3GD20H")
      (footprint "eagle-import:LGA-16L")
      (libsource (lib "eagle-import") (part "L3GD20H"))
    )
    (comp (ref "U504")
      (value "LSM303D")
      (footprint "eagle-import:LGA-16L")
      (libsource (lib "eagle-import") (part "LSM303D"))
    )
    (comp (ref "U505")
      (value "MPU-6000")
      (footprint "eagle-import:QFN-24")
      (libsource (lib "eagle-import") (part "MPU-6000"))
    )
    (comp (ref "U506")
      (value "MS5611-01BA")
      (footprint "eagle-import:MS5611-01BA")
      (libsource (lib "eagle-import") (part "MS5611-01BA"))
    )
    (comp (ref "X503")
      (value "0512811094")
      (footprint "eagle-import:51281-1094")
      (fields (field (name "PARTNO") "0781191109"))
      (libsource (lib "eagle-import") (part "CONN_FPC_10RA"))
    )
    (comp (ref "C901")
      (value "0u1")
      (footprint "eagle-import:0402-CAP")
      (fields (field (name "PARTNO") "CC0402ZRY5V7BB104"))
      (libsource (lib "eagle-import") (part "CAP0402"))
    )
    (comp (ref "C902")
      (value "0u1")
      (footprint "eagle-import:0402-CAP")
      (fields (field (name "PARTNO") "CC0402ZRY5V7BB104"))
      (libsource (lib "eagle-import") (part "CAP0402"))
    )
    (comp (ref "C903")
      (value "0u1")
      (footprint "eagle-import:0402-CAP")
      (fields (field (name "PARTNO") "CC0402ZRY5V7BB104"))
      (libsource (lib "eagle-import") (part "CAP0402"))
    )
    (comp (ref "D1")
      (value "MSS1P4-M3")
      (footprint "eagle-import:MICROSMP")
      (fields (field (name "PARTNO") "MSS1P4-M3/89A"))
      (libsource (lib "eagle-import") (part "DIODE-SCHOTTKY_MSMP"))
    )
    (comp (ref "D901")
      (value "PESD0402-140")
      (footprint "eagle-import:0402-TVS")
      (libsource (lib "eagle-import") (part "DIODE-TVS"))
    )
    (comp (ref "D902")
      (value "PESD0402-140")
      (footprint "eagle-import:0402-TVS")
      (libsource (lib "eagle-import") (part "DIODE-TVS"))
    )
    (comp (ref "D903")
      (value "PESD0402-140")
      (footprint "eagle-import:0402-TVS")
      (libsource (lib "eagle-import") (part "DIODE-TVS"))
    )
    (comp (ref "J901")
      (value "HEADER-3X163X16RA")
      (footprint "eagle-import:3X16RA")
      (fields (field (name "BOM") "EXCLUDE"))
      (libsource (lib "eagle-import") (part "HEADER-3X163X16RA"))
    )
    (comp (ref "L901")
      (value "KNH16C104DA5TS")
      (footprint "eagle-import:KYOCERA-KNH16-DA")
      (libsource (lib "eagle-import") (part "KNH16C104DA5TS"))
    )
    (comp (ref "R901")
      (value "10K")
      (footprint "eagle-import:0402-RES")
      (fields (field (name "PARTNO") "RC0402FR-0710KL"))
      (libsource (lib "eagle-import") (part "RESISTOR0402-RES"))
    )
    (comp (ref "R902")
      (value "220R")
      (footprint "eagle-import:0402-RES")
      (fields (field (name "PARTNO") "RC0402FR-07220RL"))
      (libsource (lib "eagle-import") (part "RESISTOR0402-RES"))
    )
    (comp (ref "R903")
      (value "220R")
      (footprint "eagle-import:0402-RES")
      (fields (field (name "PARTNO") "RC0402FR-07220RL"))
      (libsource (lib "eagle-import") (part "RESISTOR0402-RES"))
    )
    (comp (ref "R904")
      (value "220R")
      (footprint "eagle-import:0402-RES")
      (fields (field (name "PARTNO") "RC0402FR-07220RL"))
      (libsource (lib "eagle-import") (part "RESISTOR0402-RES"))
    )
    (comp (ref "R905")
      (value "220R")
      (footprint "eagle-import:0402-RES")
      (fields (field (name "PARTNO") "RC0402FR-07220RL"))
      (libsource (lib "eagle-import") (part "RESISTOR0402-RES"))
    )
    (comp (ref "R906")
      (value "220R")
      (footprint "eagle-import:0402-RES")
      (fields (field (name "PARTNO") "RC0402FR-07220RL"))
      (libsource (lib "eagle-import") (part "RESISTOR0402-RES"))
    )
    (comp (ref "R907")
      (value "220R")
      (footprint "eagle-import:0402-RES")
      (fields (field (name "PARTNO") "RC0402FR-07220RL"))
      (libsource (lib "eagle-import") (part "RESISTOR0402-RES"))
    )
    (comp (ref "R908")
      (value "220R")
      (footprint "eagle-import:0402-RES")
      (fields (field (name "PARTNO") "RC0402FR-07220RL"))
      (libsource (lib "eagle-import") (part "RESISTOR0402-RES"))
    )
    (comp (ref "R909")
      (value "220R")
      (footprint "eagle-import:0402-RES")
      (fields (field (name "PARTNO") "RC0402FR-07220RL"))
      (libsource (lib "eagle-import") (part "RESISTOR0402-RES"))
    )
    (comp (ref "R910")
      (value "220R")
      (footprint "eagle-import:0402-RES")
      (fields (field (name "PARTNO") "RC0402FR-07220RL"))
      (libsource (lib "eagle-import") (part "RESISTOR0402-RES"))
    )
    (comp (ref "R911")
      (value "220R")
      (footprint "eagle-import:0402-RES")
      (fields (field (name "PARTNO") "RC0402FR-07220RL"))
      (libsource (lib "eagle-import") (part "RESISTOR0402-RES"))
    )
    (comp (ref "R912")
      (value "220R")
      (footprint "eagle-import:0402-RES")
      (fields (field (name "PARTNO") "RC0402FR-07220RL"))
      (libsource (lib "eagle-import") (part "RESISTOR0402-RES"))
    )
    (comp (ref "R913")
      (value "220R")
      (footprint "eagle-import:0402-RES")
      (fields (field (name "PARTNO") "RC0402FR-07220RL"))
      (libsource (lib "eagle-import") (part "RESISTOR0402-RES"))
    )
    (comp (ref "R914")
      (value "220R")
      (footprint "eagle-import:0402-RES")
      (fields (field (name "PARTNO") "RC0402FR-07220RL"))
      (libsource (lib "eagle-import") (part "RESISTOR0402-RES"))
    )
    (comp (ref "R915")
      (value "220R")
      (footprint "eagle-import:0402-RES")
      (fields (field (name "PARTNO") "RC0402FR-07220RL"))
      (libsource (lib "eagle-import") (part "RESISTOR0402-RES"))
    )
    (comp (ref "R916")
      (value "220R")
      (footprint "eagle-import:0402-RES")
      (fields (field (name "PARTNO") "RC0402FR-07220RL"))
      (libsource (lib "eagle-import") (part "RESISTOR0402-RES"))
    )
    (comp (ref "R917")
      (value "220R")
      (footprint "eagle-import:0402-RES")
      (fields (field (name "PARTNO") "RC0402FR-07220RL"))
      (libsource (lib "eagle-import") (part "RESISTOR0402-RES"))
    )
    (comp (ref "R918")
      (value "10K/0.1%")
      (footprint "eagle-import:0402-RES")
      (fields (field (name "PARTNO") "ERA-2AEB103X"))
      (libsource (lib "eagle-import") (part "RESISTOR0402-RES"))
    )
    (comp (ref "R919")
      (value "10K/0.1%")
      (footprint "eagle-import:0402-RES")
      (fields (field (name "PARTNO") "ERA-2AEB103X"))
      (libsource (lib "eagle-import") (part "RESISTOR0402-RES"))
    )
    (comp (ref "R922")
      (value "10K/0.1%")
      (footprint "eagle-import:0402-RES")
      (fields (field (name "PARTNO") "ERA-2AEB103X"))
      (libsource (lib "eagle-import") (part "RESISTOR0402-RES"))
    )
    (comp (ref "U901")
      (value "TXS0108QFN20")
      (footprint "eagle-import:QFN20-RGY")
      (fields (field (name "PARTNO") "TXS0108ERGYR"))
      (libsource (lib "eagle-import") (part "TXS0108QFN20"))
    )
    (comp (ref "U902")
      (value "TXS0108QFN20")
      (footprint "eagle-import:QFN20-RGY")
      (fields (field (name "PARTNO") "TXS0108ERGYR"))
      (libsource (lib "eagle-import") (part "TXS0108QFN20"))
    )
    (comp (ref "U903")
      (value "74LVC2G240")
      (footprint "eagle-import:TSSOP8_SOT505-2")
      (fields (field (name "PARTNO") "74LVC2G240DP,125"))
      (libsource (lib "eagle-import") (part "74LVC2G240-TSSOP-8"))
    )
    (comp (ref "C1001")
      (value "10u/25V")
      (footprint "eagle-import:0805-CAP")
      (fields (field (name "PARTNO") "CL21A106KAYNNNE"))
      (libsource (lib "eagle-import") (part "CAP0805"))
    )
    (comp (ref "C1002")
      (value "10n")
      (footprint "eagle-import:0402-CAP")
      (fields (field (name "PARTNO") "CC0402KRX7R7BB103"))
      (libsource (lib "eagle-import") (part "CAP0402"))
    )
    (comp (ref "C1003")
      (value "1u0")
      (footprint "eagle-import:0603-CAP")
      (fields (field (name "PARTNO") "CC0603ZRY5V7BB105"))
      (libsource (lib "eagle-import") (part "CAP0603"))
    )
    (comp (ref "C1004")
      (value "10u")
      (footprint "eagle-import:0603-CAP")
      (fields (field (name "PARTNO") "CC0603ZRY5V7BB105"))
      (libsource (lib "eagle-import") (part "CAP0603"))
    )
    (comp (ref "C1005")
      (value "0u1F")
      (footprint "eagle-import:0402-CAP")
      (fields (field (name "PARTNO") "CC0402ZRY5V7BB104"))
      (libsource (lib "eagle-import") (part "CAP0402"))
    )
    (comp (ref "C1008")
      (value "2u2")
      (footprint "eagle-import:0402-CAP")
      (fields (field (name "PARTNO") "CC0603ZRY5V7BB105"))
      (libsource (lib "eagle-import") (part "CAP0402"))
    )
    (comp (ref "D1001")
      (value "PMEG2005CT")
      (footprint "eagle-import:SOT23-3")
      (libsource (lib "eagle-import") (part "PMEG2005CT"))
    )
    (comp (ref "F1001")
      (value "0ZCA0035FF2G")
      (footprint "eagle-import:PTC-1206")
      (libsource (lib "eagle-import") (part "PTCSMD"))
    )
    (comp (ref "R1001")
      (value "100K")
      (footprint "eagle-import:0402-RES")
      (fields (field (name "PARTNO") "RC0402FR-07100KL"))
      (libsource (lib "eagle-import") (part "RESISTOR0402-RES"))
    )
    (comp (ref "R1002")
      (value "10K")
      (footprint "eagle-import:0402-RES")
      (fields (field (name "PARTNO") "RC0402FR-0710KL"))
      (libsource (lib "eagle-import") (part "RESISTOR0402-RES"))
    )
    (comp (ref "U1001")
      (value "BQ24313")
      (footprint "eagle-import:QFN8-DSG")
      (fields (field (name "PARTNO") "BQ24313DSGT"))
      (libsource (lib "eagle-import") (part "BQ24313"))
    )
    (comp (ref "U1002")
      (value "MIC5332")
      (footprint "eagle-import:MLF-8-EPAD")
      (fields (field (name "PARTNO") "MIC5332-SSYMT"))
      (libsource (lib "eagle-import") (part "MIC5332"))
    )
    (comp (ref "C801")
      (value "0u1")
      (footprint "eagle-import:0402-CAP")
      (fields (field (name "PARTNO") "CC0402ZRY5V7BB104"))
      (libsource (lib "eagle-import") (part "CAP0402"))
    )
    (comp (ref "C802")
      (value "0u1")
      (footprint "eagle-import:0402-CAP")
      (fields (field (name "PARTNO") "CC0402ZRY5V7BB104"))
      (libsource (lib "eagle-import") (part "CAP0402"))
    )
    (comp (ref "C803")
      (value "0u1")
      (footprint "eagle-import:0402-CAP")
      (fields (field (name "PARTNO") "CC0402ZRY5V7BB104"))
      (libsource (lib "eagle-import") (part "CAP0402"))
    )
    (comp (ref "C804")
      (value "0u1")
      (footprint "eagle-import:0402-CAP")
      (fields (field (name "PARTNO") "CC0402ZRY5V7BB104"))
      (libsource (lib "eagle-import") (part "CAP0402"))
    )
    (comp (ref "C805")
      (value "8p")
      (footprint "eagle-import:0402-CAP")
      (fields (field (name "PARTNO") "C1005C0G1H080C"))
      (libsource (lib "eagle-import") (part "CAP0402"))
    )
    (comp (ref "C806")
      (value "8p")
      (footprint "eagle-import:0402-CAP")
      (fields (field (name "PARTNO") "C1005C0G1H080C"))
      (libsource (lib "eagle-import") (part "CAP0402"))
    )
    (comp (ref "D801")
      (value "PESD0402-140")
      (footprint "eagle-import:0402-TVS")
      (libsource (lib "eagle-import") (part "DIODE-TVS"))
    )
    (comp (ref "J801")
      (value "JST-ZH-3")
      (footprint "eagle-import:JST-ZH-SMT-VERTICAL")
      (fields (field (name "PARTNO") "B3B-ZR-SM4-TF (LF)(SN)(P)"))
      (libsource (lib "eagle-import") (part "JST-ZH-3"))
    )
    (comp (ref "JX801")
      (value "HEADER-3X1BOARDEDGE-SHORT")
      (footprint "eagle-import:HEADER_3X01_SMD_H_BOARD_EDGE_SHORT")
      (libsource (lib "eagle-import") (part "HEADER-3X1BOARDEDGE-SHORT"))
    )
    (comp (ref "JX802")
      (value "ARM_MINI_JTAG-SMT")
      (footprint "eagle-import:FTSH-105-01-XXX-DV-K")
      (fields (field (name "BOM") "EXCLUDE") (field (name "PARTNO") "M50-3900542"))
      (libsource (lib "eagle-import") (part "ARM_MINI_JTAG-SMT"))
    )
    (comp (ref "R801")
      (value "10K")
      (footprint "eagle-import:0402-RES")
      (fields (field (name "PARTNO") "RC0402FR-0710KL"))
      (libsource (lib "eagle-import") (part "RESISTOR0402-RES"))
    )
    (comp (ref "R802")
      (value "10K")
      (footprint "eagle-import:0402-RES")
      (fields (field (name "PARTNO") "RC0402FR-0710KL"))
      (libsource (lib "eagle-import") (part "RESISTOR0402-RES"))
    )
    (comp (ref "R803")
      (value "220R")
      (footprint "eagle-import:0402-RES")
      (fields (field (name "PARTNO") "RC0402FR-07220RL"))
      (libsource (lib "eagle-import") (part "RESISTOR0402-RES"))
    )
    (comp (ref "R804")
      (value "220R")
      (footprint "eagle-import:0402-RES")
      (fields (field (name "PARTNO") "RC0402FR-07220RL"))
      (libsource (lib "eagle-import") (part "RESISTOR0402-RES"))
    )
    (comp (ref "S801")
      (value "RESET")
      (footprint "eagle-import:EVQP7J01K")
      (fields (field (name "PARTNO") "EVQP7J01K"))
      (libsource (lib "eagle-import") (part "SWITCH-MOMENTARY-2"))
    )
    (comp (ref "U801")
      (value "STM32F10XCXT6")
      (footprint "eagle-import:TQFP48")
      (fields (field (name "PARTNO") "STM32F100C8T6B"))
      (libsource (lib "eagle-import") (part "STM32F10XCXT6"))
    )
    (comp (ref "X801")
      (value "3.2x2.5 mm / 24 MHz / 15 ppm")
      (footprint "eagle-import:OSCILLATOR-3.2X2.5")
      (fields (field (name "PARTNO") "NX3225SA-24.000000MHZ"))
      (libsource (lib "eagle-import") (part "OSCILLATOR-3.2X2.5"))
    )
    (comp (ref "C201")
      (value "0u1")
      (footprint "eagle-import:0402-CAP")
      (fields (field (name "PARTNO") "CC0402ZRY5V7BB104"))
      (libsource (lib "eagle-import") (part "CAP0402"))
    )
    (comp (ref "C202")
      (value "0u1")
      (footprint "eagle-import:0402-CAP")
      (fields (field (name "PARTNO") "CC0402ZRY5V7BB104"))
      (libsource (lib "eagle-import") (part "CAP0402"))
    )
    (comp (ref "D201")
      (value "PESD0402-140")
      (footprint "eagle-import:0402-TVS")
      (libsource (lib "eagle-import") (part "DIODE-TVS"))
    )
    (comp (ref "D202")
      (value "PESD0402-140")
      (footprint "eagle-import:0402-TVS")
      (libsource (lib "eagle-import") (part "DIODE-TVS"))
    )
    (comp (ref "D203")
      (value "PESD0402-140")
      (footprint "eagle-import:0402-TVS")
      (libsource (lib "eagle-import") (part "DIODE-TVS"))
    )
    (comp (ref "J201")
      (value "DF13C-6P-1.25V")
      (footprint "eagle-import:DF13C-6P-1.25V")
      (fields (field (name "PARTNO") "DF13C-6P-1.25V(20)"))
      (libsource (lib "eagle-import") (part "DF13-6P-1.25V"))
    )
    (comp (ref "J202")
      (value "DF13C-6P-1.25V")
      (footprint "eagle-import:DF13C-6P-1.25V")
      (fields (field (name "PARTNO") "DF13C-6P-1.25V(20)"))
      (libsource (lib "eagle-import") (part "DF13-6P-1.25V"))
    )
    (comp (ref "J203")
      (value "DF13C-6P-1.25V")
      (footprint "eagle-import:DF13C-6P-1.25V")
      (fields (field (name "PARTNO") "DF13C-6P-1.25V(20)"))
      (libsource (lib "eagle-import") (part "DF13-6P-1.25V"))
    )
    (comp (ref "J204")
      (value "DF13C-6P-1.25V")
      (footprint "eagle-import:DF13C-6P-1.25V")
      (fields (field (name "PARTNO") "DF13C-6P-1.25V(20)"))
      (libsource (lib "eagle-import") (part "DF13-6P-1.25V"))
    )
    (comp (ref "L201")
      (value "KNH16C104DA5TS")
      (footprint "eagle-import:KYOCERA-KNH16-DA")
      (libsource (lib "eagle-import") (part "KNH16C104DA5TS"))
    )
    (comp (ref "L202")
      (value "KNH16C104DA5TS")
      (footprint "eagle-import:KYOCERA-KNH16-DA")
      (libsource (lib "eagle-import") (part "KNH16C104DA5TS"))
    )
    (comp (ref "L203")
      (value "KNH16C104DA5TS")
      (footprint "eagle-import:KYOCERA-KNH16-DA")
      (libsource (lib "eagle-import") (part "KNH16C104DA5TS"))
    )
    (comp (ref "R201")
      (value "120R")
      (footprint "eagle-import:0402-RES")
      (fields (field (name "PARTNO") "RC0402FR-07120RL"))
      (libsource (lib "eagle-import") (part "RESISTOR0402-RES"))
    )
    (comp (ref "R202")
      (value "120R")
      (footprint "eagle-import:0402-RES")
      (fields (field (name "PARTNO") "RC0402FR-07120RL"))
      (libsource (lib "eagle-import") (part "RESISTOR0402-RES"))
    )
    (comp (ref "R203")
      (value "120R")
      (footprint "eagle-import:0402-RES")
      (fields (field (name "PARTNO") "RC0402FR-07120RL"))
      (libsource (lib "eagle-import") (part "RESISTOR0402-RES"))
    )
    (comp (ref "R204")
      (value "120R")
      (footprint "eagle-import:0402-RES")
      (fields (field (name "PARTNO") "RC0402FR-07120RL"))
      (libsource (lib "eagle-import") (part "RESISTOR0402-RES"))
    )
    (comp (ref "R205")
      (value "120R")
      (footprint "eagle-import:0402-RES")
      (fields (field (name "PARTNO") "RC0402FR-07120RL"))
      (libsource (lib "eagle-import") (part "RESISTOR0402-RES"))
    )
    (comp (ref "R206")
      (value "120R")
      (footprint "eagle-import:0402-RES")
      (fields (field (name "PARTNO") "RC0402FR-07120RL"))
      (libsource (lib "eagle-import") (part "RESISTOR0402-RES"))
    )
    (comp (ref "R207")
      (value "120R")
      (footprint "eagle-import:0402-RES")
      (fields (field (name "PARTNO") "RC0402FR-07120RL"))
      (libsource (lib "eagle-import") (part "RESISTOR0402-RES"))
    )
    (comp (ref "R208")
      (value "120R")
      (footprint "eagle-import:0402-RES")
      (fields (field (name "PARTNO") "RC0402FR-07120RL"))
      (libsource (lib "eagle-import") (part "RESISTOR0402-RES"))
    )
    (comp (ref "R209")
      (value "120R")
      (footprint "eagle-import:0402-RES")
      (fields (field (name "PARTNO") "RC0402FR-07120RL"))
      (libsource (lib "eagle-import") (part "RESISTOR0402-RES"))
    )
    (comp (ref "R210")
      (value "120R")
      (footprint "eagle-import:0402-RES")
      (fields (field (name "PARTNO") "RC0402FR-07120RL"))
      (libsource (lib "eagle-import") (part "RESISTOR0402-RES"))
    )
    (comp (ref "R211")
      (value "120R")
      (footprint "eagle-import:0402-RES")
      (fields (field (name "PARTNO") "RC0402FR-07120RL"))
      (libsource (lib "eagle-import") (part "RESISTOR0402-RES"))
    )
    (comp (ref "R212")
      (value "120R")
      (footprint "eagle-import:0402-RES")
      (fields (field (name "PARTNO") "RC0402FR-07120RL"))
      (libsource (lib "eagle-import") (part "RESISTOR0402-RES"))
    )
    (comp (ref "R213")
      (value "120R")
      (footprint "eagle-import:0402-RES")
      (fields (field (name "PARTNO") "RC0402FR-07120RL"))
      (libsource (lib "eagle-import") (part "RESISTOR0402-RES"))
    )
    (comp (ref "R214")
      (value "120R")
      (footprint "eagle-import:0402-RES")
      (fields (field (name "PARTNO") "RC0402FR-07120RL"))
      (libsource (lib "eagle-import") (part "RESISTOR0402-RES"))
    )
    (comp (ref "R215")
      (value "120R")
      (footprint "eagle-import:0402-RES")
      (fields (field (name "PARTNO") "RC0402FR-07120RL"))
      (libsource (lib "eagle-import") (part "RESISTOR0402-RES"))
    )
    (comp (ref "R216")
      (value "120R")
      (footprint "eagle-import:0402-RES")
      (fields (field (name "PARTNO") "RC0402FR-07120RL"))
      (libsource (lib "eagle-import") (part "RESISTOR0402-RES"))
    )
    (comp (ref "U201")
      (value "TXS0108QFN20")
      (footprint "eagle-import:QFN20-RGY")
      (fields (field (name "PARTNO") "TXS0108ERGYR"))
      (libsource (lib "eagle-import") (part "TXS0108QFN20"))
    )
    (comp (ref "U202")
      (value "TXS0108QFN20")
      (footprint "eagle-import:QFN20-RGY")
      (fields (field (name "PARTNO") "TXS0108ERGYR"))
      (libsource (lib "eagle-import") (part "TXS0108QFN20"))
    )
    (comp (ref "C101")
      (value "0u1")
      (footprint "eagle-import:0402-CAP")
      (fields (field (name "PARTNO") "CC0402ZRY5V7BB104"))
      (libsource (lib "eagle-import") (part "CAP0402"))
    )
    (comp (ref "C102")
      (value "8p")
      (footprint "eagle-import:0402-CAP")
      (fields (field (name "PARTNO") "C1005C0G1H080C"))
      (libsource (lib "eagle-import") (part "CAP0402"))
    )
    (comp (ref "C103")
      (value "8p")
      (footprint "eagle-import:0402-CAP")
      (fields (field (name "PARTNO") "C1005C0G1H080C"))
      (libsource (lib "eagle-import") (part "CAP0402"))
    )
    (comp (ref "R101")
      (value "470R")
      (footprint "eagle-import:0402-RES")
      (fields (field (name "PARTNO") "RC0402FR-07470RL"))
      (libsource (lib "eagle-import") (part "RESISTOR0402-RES"))
    )
    (comp (ref "R102")
      (value "10K")
      (footprint "eagle-import:0402-RES")
      (fields (field (name "PARTNO") "RC0402FR-0710KL"))
      (libsource (lib "eagle-import") (part "RESISTOR0402-RES"))
    )
    (comp (ref "U102")
      (value "FM25V01")
      (footprint "eagle-import:SO08")
      (fields (field (name "PARTNO") "FM25V01-G"))
      (libsource (lib "eagle-import") (part "FM25V01"))
    )
    (comp (ref "X101")
      (value "3.2x2.5 mm / 24 MHz / 15 ppm")
      (footprint "eagle-import:OSCILLATOR-3.2X2.5")
      (fields (field (name "PARTNO") "NX3225SA-24.000000MHZ"))
      (libsource (lib "eagle-import") (part "OSCILLATOR-3.2X2.5"))
    )
    (comp (ref "C701")
      (value "0u1")
      (footprint "eagle-import:0402-CAP")
      (fields (field (name "PARTNO") "CC0402ZRY5V7BB104"))
      (libsource (lib "eagle-import") (part "CAP0402"))
    )
    (comp (ref "C702")
      (value "1u0")
      (footprint "eagle-import:0603-CAP")
      (fields (field (name "PARTNO") "CC0603ZRY5V7BB105"))
      (libsource (lib "eagle-import") (part "CAP0603"))
    )
    (comp (ref "C703")
      (value "5n6")
      (footprint "eagle-import:0402-CAP")
      (fields (field (name "PARTNO") "CC0402KRX7R7BB562"))
      (libsource (lib "eagle-import") (part "CAP0402"))
    )
    (comp (ref "C704")
      (value "0u47")
      (footprint "eagle-import:0402-CAP")
      (fields (field (name "PARTNO") "C1005X5R1C474K050BC"))
      (libsource (lib "eagle-import") (part "CAP0402"))
    )
    (comp (ref "D701")
      (value "PESD0402-140")
      (footprint "eagle-import:0402-TVS")
      (libsource (lib "eagle-import") (part "DIODE-TVS"))
    )
    (comp (ref "J701")
      (value "DF13C-2P-1.25V")
      (footprint "eagle-import:DF13C-2P-1.25V")
      (fields (field (name "PARTNO") "DF13C-2P-1.25V(20)"))
      (libsource (lib "eagle-import") (part "DF13-2P-1.25V"))
    )
    (comp (ref "J702")
      (value "DF13C-3P-1.25V")
      (footprint "eagle-import:DF13C-3P-1.25V")
      (fields (field (name "PARTNO") "DF13C-3P-1.25V(20)"))
      (libsource (lib "eagle-import") (part "DF13-3P-1.25V"))
    )
    (comp (ref "L701")
      (value "47uH")
      (footprint "eagle-import:0805-IND")
      (fields (field (name "PARTNO") "MLZ2012M470W"))
      (libsource (lib "eagle-import") (part "INDUCTOR0805"))
    )
    (comp (ref "LED701")
      (value "AMBER")
      (footprint "eagle-import:0603-LED")
      (fields (field (name "PARTNO") "APTD1608SECK"))
      (libsource (lib "eagle-import") (part "LED0603"))
    )
    (comp (ref "LED702")
      (value "GREEN")
      (footprint "eagle-import:0603-LED")
      (fields (field (name "PARTNO") "APTD1608CGCK"))
      (libsource (lib "eagle-import") (part "LED0603"))
    )
    (comp (ref "LED703")
      (value "AMBER")
      (footprint "eagle-import:0603-LED")
      (fields (field (name "PARTNO") "APTD1608SECK"))
      (libsource (lib "eagle-import") (part "LED0603"))
    )
    (comp (ref "LED704")
      (value "GREEN")
      (footprint "eagle-import:0603-LED")
      (fields (field (name "PARTNO") "APTD1608CGCK"))
      (libsource (lib "eagle-import") (part "LED0603"))
    )
    (comp (ref "LED705")
      (value "BLUE")
      (footprint "eagle-import:0603-LED")
      (fields (field (name "PARTNO") "APTD1608QBC/D"))
      (libsource (lib "eagle-import") (part "LED0603"))
    )
    (comp (ref "R3")
      (value "220R")
      (footprint "eagle-import:0402-RES")
      (fields (field (name "PARTNO") "RC0402FR-07220RL"))
      (libsource (lib "eagle-import") (part "RESISTOR0402-RES"))
    )
    (comp (ref "R4")
      (value "220R")
      (footprint "eagle-import:0402-RES")
      (fields (field (name "PARTNO") "RC0402FR-07220RL"))
      (libsource (lib "eagle-import") (part "RESISTOR0402-RES"))
    )
    (comp (ref "R701")
      (value "9K09")
      (footprint "eagle-import:0402-RES")
      (fields (field (name "PARTNO") "RMCF0402FT9K09"))
      (libsource (lib "eagle-import") (part "RESISTOR0402-RES"))
    )
    (comp (ref "R702")
      (value "10K")
      (footprint "eagle-import:0402-RES")
      (fields (field (name "PARTNO") "RC0402FR-0710KL"))
      (libsource (lib "eagle-import") (part "RESISTOR0402-RES"))
    )
    (comp (ref "R703")
      (value "100K")
      (footprint "eagle-import:0402-RES")
      (fields (field (name "PARTNO") "RC0402FR-07100KL"))
      (libsource (lib "eagle-import") (part "RESISTOR0402-RES"))
    )
    (comp (ref "R704")
      (value "10K")
      (footprint "eagle-import:0402-RES")
      (fields (field (name "PARTNO") "RC0402FR-0710KL"))
      (libsource (lib "eagle-import") (part "RESISTOR0402-RES"))
    )
    (comp (ref "R705")
      (value "453K")
      (footprint "eagle-import:0402-RES")
      (fields (field (name "PARTNO") "RMCF0402FT453K"))
      (libsource (lib "eagle-import") (part "RESISTOR0402-RES"))
    )
    (comp (ref "R706")
      (value "16K5")
      (footprint "eagle-import:0402-RES")
      (fields (field (name "PARTNO") "RMCF0402FT16K5"))
      (libsource (lib "eagle-import") (part "RESISTOR0402-RES"))
    )
    (comp (ref "R707")
      (value "220R")
      (footprint "eagle-import:0402-RES")
      (fields (field (name "PARTNO") "RC0402FR-07220RL"))
      (libsource (lib "eagle-import") (part "RESISTOR0402-RES"))
    )
    (comp (ref "R708")
      (value "220R")
      (footprint "eagle-import:0402-RES")
      (fields (field (name "PARTNO") "RC0402FR-07220RL"))
      (libsource (lib "eagle-import") (part "RESISTOR0402-RES"))
    )
    (comp (ref "R709")
      (value "220R")
      (footprint "eagle-import:0402-RES")
      (fields (field (name "PARTNO") "RC0402FR-07220RL"))
      (libsource (lib "eagle-import") (part "RESISTOR0402-RES"))
    )
    (comp (ref "R710")
      (value "68R")
      (footprint "eagle-import:0402-RES")
      (fields (field (name "PARTNO") "ERJ-2GEJ680X"))
      (libsource (lib "eagle-import") (part "RESISTOR0402-RES"))
    )
    (comp (ref "R711")
      (value "220R")
      (footprint "eagle-import:0402-RES")
      (fields (field (name "PARTNO") "RC0402FR-07220RL"))
      (libsource (lib "eagle-import") (part "RESISTOR0402-RES"))
    )
    (comp (ref "R712")
      (value "220R")
      (footprint "eagle-import:0402-RES")
      (fields (field (name "PARTNO") "RC0402FR-07220RL"))
      (libsource (lib "eagle-import") (part "RESISTOR0402-RES"))
    )
    (comp (ref "R713")
      (value "1K5")
      (footprint "eagle-import:0402-RES")
      (fields (field (name "PARTNO") "RC0402FR-071K5L"))
      (libsource (lib "eagle-import") (part "RESISTOR0402-RES"))
    )
    (comp (ref "U701")
      (value "TCA62724FMG")
      (footprint "eagle-import:SON10")
      (libsource (lib "eagle-import") (part "TCA62724FMG"))
    )
    (comp (ref "U702")
      (value "LT3469")
      (footprint "eagle-import:SOT23-8")
      (fields (field (name "PARTNO") "LT3469ETS8"))
      (libsource (lib "eagle-import") (part "LT3469"))
    )
    (comp (ref "U703")
      (value "LRTB GFTG-T7AW-1+V7A7-29+R5T9-49-L")
      (footprint "eagle-import:6-PLCC")
      (fields (field (name "PARTNO") "LRTB GFTG-T7AW-1+V7A7-29+R5T9-49-L"))
      (libsource (lib "eagle-import") (part "RGB-LED6-PLCC"))
    )
  )
  (nets
    (net (code "1") (name "ACCEL_DRDY") (class "Default")
      (node (ref "U101") (pin "90") (pinfunction "PB4_90") (pintype "bidirectional"))
      (node (ref "U504") (pin "11") (pinfunction "INT1_11") (pintype "bidirectional"))
      (node (ref "X503") (pin "3") (pinfunction "S_3") (pintype "passive"))
    )
    (net (code "2") (name "ALARM") (class "Default")
      (node (ref "R701") (pin "P$2") (pinfunction "2_P$2") (pintype "passive"))
      (node (ref "U101") (pin "77") (pinfunction "PA15_77") (pintype "bidirectional"))
    )
    (net (code "3") (name "BATT_CURRENT_SENS") (class "Default")
      (node (ref "R1101") (pin "P$1") (pinfunction "1_P$1") (pintype "passive"))
      (node (ref "U101") (pin "26") (pinfunction "PA3_26") (pintype "bidirectional"))
    )
    (net (code "4") (name "BATT_VOLTAGE_SENS") (class "Default")
      (node (ref "R1102") (pin "P$1") (pinfunction "1_P$1") (pintype "passive"))
      (node (ref "U101") (pin "25") (pinfunction "PA2_25") (pintype "bidirectional"))
    )
    (net (code "5") (name "CAN1_RX") (class "Default")
      (node (ref "U101") (pin "81") (pinfunction "PD0_81") (pintype "bidirectional"))
      (node (ref "U401") (pin "4") (pinfunction "DOUT_4") (pintype "output"))
    )
    (net (code "6") (name "CAN1_TX") (class "Default")
      (node (ref "U101") (pin "82") (pinfunction "PD1_82") (pintype "bidirectional"))
      (node (ref "U401") (pin "1") (pinfunction "DIN_1") (pintype "input"))
    )
    (net (code "7") (name "CAN2_RX") (class "Default")
      (node (ref "R216") (pin "P$1") (pinfunction "1_P$1") (pintype "passive"))
      (node (ref "U101") (pin "51") (pinfunction "PB12_51") (pintype "bidirectional"))
    )
    (net (code "8") (name "CAN2_TX") (class "Default")
      (node (ref "R215") (pin "P$1") (pinfunction "1_P$1") (pintype "passive"))
      (node (ref "U101") (pin "92") (pinfunction "PB6_92") (pintype "bidirectional"))
    )
    (net (code "9") (name "CAN_H") (class "Default")
      (node (ref "CAN_H") (pin "P$1") (pinfunction "P$1_P$1") (pintype "passive"))
      (node (ref "J405") (pin "2") (pinfunction "2_2") (pintype "passive"))
      (node (ref "R409") (pin "P$1") (pinfunction "1_P$1") (pintype "passive"))
      (node (ref "U401") (pin "7") (pinfunction "CANH_7") (pintype "bidirectional"))
    )
    (net (code "10") (name "CAN_L") (class "Default")
      (node (ref "CAN_L") (pin "P$1") (pinfunction "P$1_P$1") (pintype "passive"))
      (node (ref "J405") (pin "3") (pinfunction "3_3") (pintype "passive"))
      (node (ref "R409") (pin "P$2") (pinfunction "2_P$2") (pintype "passive"))
      (node (ref "U401") (pin "6") (pinfunction "CANL_6") (pintype "bidirectional"))
    )
    (net (code "11") (name "FMU-BOOT0") (class "Default")
      (node (ref "FMU-BOOT1101") (pin "P$1") (pinfunction "P$1_P$1") (pintype "passive"))
      (node (ref "R611") (pin "P$2") (pinfunction "2_P$2") (pintype "passive"))
      (node (ref "U101") (pin "94") (pinfunction "BOOT0_94") (pintype "input"))
    )
    (net (code "12") (name "FMU-CH1") (class "Default")
      (node (ref "U101") (pin "45") (pinfunction "PE14_45") (pintype "bidirectional"))
      (node (ref "U901") (pin "7") (pinfunction "A6_7") (pintype "bidirectional"))
    )
    (net (code "13") (name "FMU-CH2") (class "Default")
      (node (ref "U101") (pin "44") (pinfunction "PE13_44") (pintype "bidirectional"))
      (node (ref "U901") (pin "6") (pinfunction "A5_6") (pintype "bidirectional"))
    )
    (net (code "14") (name "FMU-CH3") (class "Default")
      (node (ref "U101") (pin "42") (pinfunction "PE11_42") (pintype "bidirectional"))
      (node (ref "U901") (pin "5") (pinfunction "A4_5") (pintype "bidirectional"))
    )
    (net (code "15") (name "FMU-CH4") (class "Default")
      (node (ref "U101") (pin "40") (pinfunction "PE9_40") (pintype "bidirectional"))
      (node (ref "U901") (pin "4") (pinfunction "A3_4") (pintype "bidirectional"))
    )
    (net (code "16") (name "FMU-CH5") (class "Default")
      (node (ref "U101") (pin "60") (pinfunction "PD13_60") (pintype "bidirectional"))
      (node (ref "U901") (pin "3") (pinfunction "A2_3") (pintype "bidirectional"))
    )
    (net (code "17") (name "FMU-CH6") (class "Default")
      (node (ref "U101") (pin "61") (pinfunction "PD14_61") (pintype "bidirectional"))
      (node (ref "U901") (pin "1") (pinfunction "A1_1") (pintype "bidirectional"))
    )
    (net (code "18") (name "FMU-I2C1_SCL") (class "Default")
      (node (ref "R401") (pin "P$1") (pinfunction "1_P$1") (pintype "passive"))
      (node (ref "R404") (pin "P$1") (pinfunction "1_P$1") (pintype "passive"))
      (node (ref "U101") (pin "95") (pinfunction "PB8_95") (pintype "bidirectional"))
    )
    (net (code "19") (name "FMU-I2C1_SDA") (class "Default")
      (node (ref "R402") (pin "P$1") (pinfunction "1_P$1") (pintype "passive"))
      (node (ref "R405") (pin "P$1") (pinfunction "1_P$1") (pintype "passive"))
      (node (ref "U101") (pin "96") (pinfunction "PB9_96") (pintype "bidirectional"))
    )
    (net (code "20") (name "FMU-I2C2_SCL") (class "Default")
      (node (ref "R306") (pin "P$1") (pinfunction "1_P$1") (pintype "passive"))
      (node (ref "U101") (pin "47") (pinfunction "PB10_47") (pintype "bidirectional"))
      (node (ref "U701") (pin "3") (pinfunction "SCL_3") (pintype "bidirectional"))
    )
    (net (code "21") (name "FMU-I2C2_SDA") (class "Default")
      (node (ref "R307") (pin "P$1") (pinfunction "1_P$1") (pintype "passive"))
      (node (ref "U101") (pin "48") (pinfunction "PB11_48") (pintype "bidirectional"))
      (node (ref "U701") (pin "2") (pinfunction "SDA_2") (pintype "bidirectional"))
    )
    (net (code "22") (name "FMU-SWCLK") (class "Default")
      (node (ref "JX301") (pin "4") (pinfunction "S_4") (pintype "passive"))
      (node (ref "U101") (pin "76") (pinfunction "PA14_76") (pintype "bidirectional"))
    )
    (net (code "23") (name "FMU-SWDIO") (class "Default")
      (node (ref "JX301") (pin "2") (pinfunction "S_2") (pintype "passive"))
      (node (ref "U101") (pin "72") (pinfunction "PA13_72") (pintype "bidirectional"))
    )
    (net (code "24") (name "FMU-SWO") (class "Default")
      (node (ref "JX301") (pin "6") (pinfunction "S_6") (pintype "passive"))
      (node (ref "U101") (pin "89") (pinfunction "PB3_89") (pintype "bidirectional"))
    )
    (net (code "25") (name "FMU-UART4_RX") (class "Default")
      (node (ref "U101") (pin "24") (pinfunction "PA1_24") (pintype "bidirectional"))
      (node (ref "U202") (pin "8") (pinfunction "A7_8") (pintype "bidirectional"))
    )
    (net (code "26") (name "FMU-UART4_TX") (class "Default")
      (node (ref "U101") (pin "23") (pinfunction "PA0_23") (pintype "bidirectional"))
      (node (ref "U202") (pin "9") (pinfunction "A8_9") (pintype "bidirectional"))
    )
    (net (code "27") (name "FMU-UART7_RX") (class "Default")
      (node (ref "U101") (pin "38") (pinfunction "PE7_38") (pintype "bidirectional"))
      (node (ref "U202") (pin "4") (pinfunction "A3_4") (pintype "bidirectional"))
    )
    (net (code "28") (name "FMU-UART7_TX") (class "Default")
      (node (ref "U101") (pin "39") (pinfunction "PE8_39") (pintype "bidirectional"))
      (node (ref "U202") (pin "5") (pinfunction "A4_5") (pintype "bidirectional"))
    )
    (net (code "29") (name "FMU-UART8_RX") (class "Default")
      (node (ref "U101") (pin "97") (pinfunction "PE0_97") (pintype "bidirectional"))
      (node (ref "U202") (pin "6") (pinfunction "A5_6") (pintype "bidirectional"))
    )
    (net (code "30") (name "FMU-UART8_TX") (class "Default")
      (node (ref "U101") (pin "98") (pinfunction "PE1_98") (pintype "bidirectional"))
      (node (ref "U202") (pin "7") (pinfunction "A6_7") (pintype "bidirectional"))
    )
    (net (code "31") (name "FMU-USART2_CTS") (class "Default")
      (node (ref "U101") (pin "84") (pinfunction "PD3_84") (pintype "bidirectional"))
      (node (ref "U201") (pin "9") (pinfunction "A8_9") (pintype "bidirectional"))
    )
    (net (code "32") (name "FMU-USART2_RTS") (class "Default")
      (node (ref "U101") (pin "85") (pinfunction "PD4_85") (pintype "bidirectional"))
      (node (ref "U201") (pin "8") (pinfunction "A7_8") (pintype "bidirectional"))
    )
    (net (code "33") (name "FMU-USART2_RX") (class "Default")
      (node (ref "U101") (pin "87") (pinfunction "PD6_87") (pintype "bidirectional"))
      (node (ref "U201") (pin "6") (pinfunction "A5_6") (pintype "bidirectional"))
    )
    (net (code "34") (name "FMU-USART2_TX") (class "Default")
      (node (ref "U101") (pin "86") (pinfunction "PD5_86") (pintype "bidirectional"))
      (node (ref "U201") (pin "7") (pinfunction "A6_7") (pintype "bidirectional"))
    )
    (net (code "35") (name "FMU-USART3_CTS") (class "Default")
      (node (ref "U101") (pin "58") (pinfunction "PD11_58") (pintype "bidirectional"))
      (node (ref "U201") (pin "3") (pinfunction "A2_3") (pintype "bidirectional"))
    )
    (net (code "36") (name "FMU-USART3_RTS") (class "Default")
      (node (ref "U101") (pin "59") (pinfunction "PD12_59") (pintype "bidirectional"))
      (node (ref "U201") (pin "1") (pinfunction "A1_1") (pintype "bidirectional"))
    )
    (net (code "37") (name "FMU-USART3_RX") (class "Default")
      (node (ref "U101") (pin "56") (pinfunction "PD9_56") (pintype "bidirectional"))
      (node (ref "U201") (pin "4") (pinfunction "A3_4") (pintype "bidirectional"))
    )
    (net (code "38") (name "FMU-USART3_TX") (class "Default")
      (node (ref "U101") (pin "55") (pinfunction "PD8_55") (pintype "bidirectional"))
      (node (ref "U201") (pin "5") (pinfunction "A4_5") (pintype "bidirectional"))
    )
    (net (code "39") (name "FMU-VDD_3V3") (class "Default")
      (node (ref "C101") (pin "P$1") (pinfunction "1_P$1") (pintype "passive"))
      (node (ref "C201") (pin "P$1") (pinfunction "1_P$1") (pintype "passive"))
      (node (ref "C202") (pin "P$1") (pinfunction "1_P$1") (pintype "passive"))
      (node (ref "C402") (pin "P$1") (pinfunction "1_P$1") (pintype "passive"))
      (node (ref "C603") (pin "P$1") (pinfunction "1_P$1") (pintype "passive"))
      (node (ref "C604") (pin "P$1") (pinfunction "1_P$1") (pintype "passive"))
      (node (ref "C606") (pin "P$1") (pinfunction "1_P$1") (pintype "passive"))
      (node (ref "C607") (pin "P$1") (pinfunction "1_P$1") (pintype "passive"))
      (node (ref "C608") (pin "P$1") (pinfunction "1_P$1") (pintype "passive"))
      (node (ref "C610") (pin "P$1") (pinfunction "1_P$1") (pintype "passive"))
      (node (ref "C612") (pin "P$1") (pinfunction "1_P$1") (pintype "passive"))
      (node (ref "C616") (pin "P$1") (pinfunction "1_P$1") (pintype "passive"))
      (node (ref "C701") (pin "P$1") (pinfunction "1_P$1") (pintype "passive"))
      (node (ref "C902") (pin "P$1") (pinfunction "1_P$1") (pintype "passive"))
      (node (ref "D2") (pin "A") (pinfunction "A_A") (pintype "passive"))
      (node (ref "JX301") (pin "1") (pinfunction "S_1") (pintype "passive"))
      (node (ref "R301") (pin "P$2") (pinfunction "2_P$2") (pintype "passive"))
      (node (ref "R302") (pin "P$2") (pinfunction "2_P$2") (pintype "passive"))
      (node (ref "R303") (pin "P$2") (pinfunction "2_P$2") (pintype "passive"))
      (node (ref "R304") (pin "P$2") (pinfunction "2_P$2") (pintype "passive"))
      (node (ref "R305") (pin "P$2") (pinfunction "2_P$2") (pintype "passive"))
      (node (ref "R306") (pin "P$2") (pinfunction "2_P$2") (pintype "passive"))
      (node (ref "R307") (pin "P$2") (pinfunction "2_P$2") (pintype "passive"))
      (node (ref "R401") (pin "P$2") (pinfunction "2_P$2") (pintype "passive"))
      (node (ref "R402") (pin "P$2") (pinfunction "2_P$2") (pintype "passive"))
      (node (ref "R602") (pin "P$2") (pinfunction "2_P$2") (pintype "passive"))
      (node (ref "R604") (pin "P$2") (pinfunction "2_P$2") (pintype "passive"))
      (node (ref "U101") (pin "100") (pinfunction "VDD_100") (pintype "power_in"))
      (node (ref "U101") (pin "11") (pinfunction "VDD_11") (pintype "power_in"))
      (node (ref "U101") (pin "19") (pinfunction "VDD_19") (pintype "power_in"))
      (node (ref "U101") (pin "21") (pinfunction "VREF+_21") (pintype "input"))
      (node (ref "U101") (pin "22") (pinfunction "VDDA_22") (pintype "power_in"))
      (node (ref "U101") (pin "28") (pinfunction "VDD_28") (pintype "power_in"))
      (node (ref "U101") (pin "50") (pinfunction "VDD_50") (pintype "power_in"))
      (node (ref "U101") (pin "75") (pinfunction "VDD_75") (pintype "power_in"))
      (node (ref "U102") (pin "3") (pinfunction "~{W}_3") (pintype "bidirectional"))
      (node (ref "U102") (pin "7") (pinfunction "~{HOLD}_7") (pintype "bidirectional"))
      (node (ref "U102") (pin "8") (pinfunction "VDD_8") (pintype "bidirectional"))
      (node (ref "U201") (pin "10") (pinfunction "OE_10") (pintype "input"))
      (node (ref "U201") (pin "19") (pinfunction "VCCB_19") (pintype "input"))
      (node (ref "U201") (pin "2") (pinfunction "VCCA_2") (pintype "input"))
      (node (ref "U202") (pin "10") (pinfunction "OE_10") (pintype "input"))
      (node (ref "U202") (pin "19") (pinfunction "VCCB_19") (pintype "input"))
      (node (ref "U202") (pin "2") (pinfunction "VCCA_2") (pintype "input"))
      (node (ref "U301") (pin "4") (pinfunction "VCC_4") (pintype "passive"))
      (node (ref "U401") (pin "3") (pinfunction "VCC_3") (pintype "input"))
      (node (ref "U603") (pin "7") (pinfunction "VOUT2_7") (pintype "bidirectional"))
      (node (ref "U701") (pin "1") (pinfunction "~{SHDN}_1") (pintype "input"))
      (node (ref "U701") (pin "10") (pinfunction "VIN_10") (pintype "power_in"))
      (node (ref "U901") (pin "10") (pinfunction "OE_10") (pintype "input"))
      (node (ref "U901") (pin "19") (pinfunction "VCCB_19") (pintype "input"))
      (node (ref "U901") (pin "2") (pinfunction "VCCA_2") (pintype "input"))
      (node (ref "VDD_3V1101") (pin "P$1") (pinfunction "P$1_P$1") (pintype "passive"))
    )
    (net (code "40") (name "FMU-~{RESET}") (class "Default")
      (node (ref "C609") (pin "P$2") (pinfunction "2_P$2") (pintype "passive"))
      (node (ref "R635") (pin "P$1") (pinfunction "1_P$1") (pintype "passive"))
      (node (ref "S601") (pin "A1") (pinfunction "1_A1") (pintype "passive"))
      (node (ref "U101") (pin "14") (pinfunction "NRST_14") (pintype "input"))
      (node (ref "U603") (pin "3") (pinfunction "POR2_3") (pintype "bidirectional"))
      (node (ref "U701") (pin "4") (pinfunction "~{RESET}_4") (pintype "input"))
    )
    (net (code "41") (name "FMU_AUX_ADC1") (class "Default")
      (node (ref "R408") (pin "P$1") (pinfunction "1_P$1") (pintype "passive"))
      (node (ref "U101") (pin "18") (pinfunction "PC3_18") (pintype "bidirectional"))
    )
    (net (code "42") (name "FMU_AUX_ADC2") (class "Default")
      (node (ref "R407") (pin "P$1") (pinfunction "1_P$1") (pintype "passive"))
      (node (ref "U101") (pin "33") (pinfunction "PC4_33") (pintype "bidirectional"))
    )
    (net (code "43") (name "FRAM_MISO") (class "Default")
      (node (ref "U101") (pin "53") (pinfunction "PB14_53") (pintype "bidirectional"))
      (node (ref "U102") (pin "2") (pinfunction "Q_2") (pintype "bidirectional"))
    )
    (net (code "44") (name "FRAM_MOSI") (class "Default")
      (node (ref "U101") (pin "54") (pinfunction "PB15_54") (pintype "bidirectional"))
      (node (ref "U102") (pin "5") (pinfunction "D_5") (pintype "bidirectional"))
    )
    (net (code "45") (name "FRAM_SCK") (class "Default")
      (node (ref "U101") (pin "52") (pinfunction "PB13_52") (pintype "bidirectional"))
      (node (ref "U102") (pin "6") (pinfunction "C_6") (pintype "bidirectional"))
    )
    (net (code "46") (name "GND") (class "Default")
      (node (ref "B601") (pin "2") (pinfunction "NEG_2") (pintype "bidirectional"))
      (node (ref "C1001") (pin "P$2") (pinfunction "2_P$2") (pintype "passive"))
      (node (ref "C1002") (pin "P$2") (pinfunction "2_P$2") (pintype "passive"))
      (node (ref "C1003") (pin "P$2") (pinfunction "2_P$2") (pintype "passive"))
      (node (ref "C1004") (pin "P$2") (pinfunction "2_P$2") (pintype "passive"))
      (node (ref "C1005") (pin "P$2") (pinfunction "2_P$2") (pintype "passive"))
      (node (ref "C1008") (pin "P$2") (pinfunction "2_P$2") (pintype "passive"))
      (node (ref "C101") (pin "P$2") (pinfunction "2_P$2") (pintype "passive"))
      (node (ref "C102") (pin "P$2") (pinfunction "2_P$2") (pintype "passive"))
      (node (ref "C103") (pin "P$1") (pinfunction "1_P$1") (pintype "passive"))
      (node (ref "C1101") (pin "P$2") (pinfunction "2_P$2") (pintype "passive"))
      (node (ref "C1102") (pin "P$2") (pinfunction "2_P$2") (pintype "passive"))
      (node (ref "C1103") (pin "P$2") (pinfunction "2_P$2") (pintype "passive"))
      (node (ref "C1104") (pin "P$2") (pinfunction "2_P$2") (pintype "passive"))
      (node (ref "C1105") (pin "P$2") (pinfunction "2_P$2") (pintype "passive"))
      (node (ref "C1106") (pin "P$2") (pinfunction "2_P$2") (pintype "passive"))
      (node (ref "C1107") (pin "P$2") (pinfunction "2_P$2") (pintype "passive"))
      (node (ref "C1108") (pin "P$2") (pinfunction "2_P$2") (pintype "passive"))
      (node (ref "C1109") (pin "P$2") (pinfunction "2_P$2") (pintype "passive"))
      (node (ref "C1110") (pin "P$2") (pinfunction "2_P$2") (pintype "passive"))
      (node (ref "C201") (pin "P$2") (pinfunction "2_P$2") (pintype "passive"))
      (node (ref "C202") (pin "P$2") (pinfunction "2_P$2") (pintype "passive"))
      (node (ref "C401") (pin "P$2") (pinfunction "2_P$2") (pintype "passive"))
      (node (ref "C402") (pin "P$2") (pinfunction "2_P$2") (pintype "passive"))
      (node (ref "C501") (pin "P$2") (pinfunction "2_P$2") (pintype "passive"))
      (node (ref "C502") (pin "P$2") (pinfunction "2_P$2") (pintype "passive"))
      (node (ref "C503") (pin "P$2") (pinfunction "2_P$2") (pintype "passive"))
      (node (ref "C504") (pin "P$2") (pinfunction "2_P$2") (pintype "passive"))
      (node (ref "C505") (pin "P$2") (pinfunction "2_P$2") (pintype "passive"))
      (node (ref "C506") (pin "P$2") (pinfunction "2_P$2") (pintype "passive"))
      (node (ref "C507") (pin "P$2") (pinfunction "2_P$2") (pintype "passive"))
      (node (ref "C508") (pin "P$2") (pinfunction "2_P$2") (pintype "passive"))
      (node (ref "C509") (pin "P$2") (pinfunction "2_P$2") (pintype "passive"))
      (node (ref "C511") (pin "P$2") (pinfunction "2_P$2") (pintype "passive"))
      (node (ref "C512") (pin "P$2") (pinfunction "2_P$2") (pintype "passive"))
      (node (ref "C513") (pin "P$2") (pinfunction "2_P$2") (pintype "passive"))
      (node (ref "C514") (pin "P$2") (pinfunction "2_P$2") (pintype "passive"))
      (node (ref "C515") (pin "P$2") (pinfunction "2_P$2") (pintype "passive"))
      (node (ref "C601") (pin "P$2") (pinfunction "2_P$2") (pintype "passive"))
      (node (ref "C602") (pin "P$1") (pinfunction "1_P$1") (pintype "passive"))
      (node (ref "C603") (pin "P$2") (pinfunction "2_P$2") (pintype "passive"))
      (node (ref "C604") (pin "P$2") (pinfunction "2_P$2") (pintype "passive"))
      (node (ref "C605") (pin "P$2") (pinfunction "2_P$2") (pintype "passive"))
      (node (ref "C606") (pin "P$2") (pinfunction "2_P$2") (pintype "passive"))
      (node (ref "C607") (pin "P$2") (pinfunction "2_P$2") (pintype "passive"))
      (node (ref "C608") (pin "P$2") (pinfunction "2_P$2") (pintype "passive"))
      (node (ref "C609") (pin "P$1") (pinfunction "1_P$1") (pintype "passive"))
      (node (ref "C610") (pin "P$2") (pinfunction "2_P$2") (pintype "passive"))
      (node (ref "C611") (pin "P$2") (pinfunction "2_P$2") (pintype "passive"))
      (node (ref "C612") (pin "P$2") (pinfunction "2_P$2") (pintype "passive"))
      (node (ref "C613") (pin "P$2") (pinfunction "2_P$2") (pintype "passive"))
      (node (ref "C614") (pin "P$2") (pinfunction "2_P$2") (pintype "passive"))
      (node (ref "C615") (pin "P$2") (pinfunction "2_P$2") (pintype "passive"))
      (node (ref "C616") (pin "P$2") (pinfunction "2_P$2") (pintype "passive"))
      (node (ref "C617") (pin "P$2") (pinfunction "2_P$2") (pintype "passive"))
      (node (ref "C618") (pin "P$2") (pinfunction "2_P$2") (pintype "passive"))
      (node (ref "C701") (pin "P$2") (pinfunction "2_P$2") (pintype "passive"))
      (node (ref "C702") (pin "P$2") (pinfunction "2_P$2") (pintype "passive"))
      (node (ref "C703") (pin "P$2") (pinfunction "2_P$2") (pintype "passive"))
      (node (ref "C704") (pin "P$2") (pinfunction "2_P$2") (pintype "passive"))
      (node (ref "C801") (pin "P$1") (pinfunction "1_P$1") (pintype "passive"))
      (node (ref "C802") (pin "P$2") (pinfunction "2_P$2") (pintype "passive"))
      (node (ref "C803") (pin "P$2") (pinfunction "2_P$2") (pintype "passive"))
      (node (ref "C804") (pin "P$2") (pinfunction "2_P$2") (pintype "passive"))
      (node (ref "C805") (pin "P$2") (pinfunction "2_P$2") (pintype "passive"))
      (node (ref "C806") (pin "P$1") (pinfunction "1_P$1") (pintype "passive"))
      (node (ref "C901") (pin "P$2") (pinfunction "2_P$2") (pintype "passive"))
      (node (ref "C902") (pin "P$2") (pinfunction "2_P$2") (pintype "passive"))
      (node (ref "C903") (pin "P$2") (pinfunction "2_P$2") (pintype "passive"))
      (node (ref "D201") (pin "A") (pinfunction "A_A") (pintype "passive"))
      (node (ref "D202") (pin "A") (pinfunction "A_A") (pintype "passive"))
      (node (ref "D203") (pin "A") (pinfunction "A_A") (pintype "passive"))
      (node (ref "D401") (pin "A") (pinfunction "A_A") (pintype "passive"))
      (node (ref "D402") (pin "A") (pinfunction "A_A") (pintype "passive"))
      (node (ref "D403") (pin "A") (pinfunction "A_A") (pintype "passive"))
      (node (ref "D404") (pin "A") (pinfunction "A_A") (pintype "passive"))
      (node (ref "D701") (pin "A") (pinfunction "A_A") (pintype "passive"))
      (node (ref "D801") (pin "A") (pinfunction "A_A") (pintype "passive"))
      (node (ref "D901") (pin "A") (pinfunction "A_A") (pintype "passive"))
      (node (ref "D902") (pin "A") (pinfunction "A_A") (pintype "passive"))
      (node (ref "D903") (pin "A") (pinfunction "A_A") (pintype "passive"))
      (node (ref "GND") (pin "P$1") (pinfunction "P$1_P$1") (pintype "passive"))
      (node (ref "GND.") (pin "P$1") (pinfunction "P$1_P$1") (pintype "passive"))
      (node (ref "J201") (pin "6") (pinfunction "6_6") (pintype "passive"))
      (node (ref "J202") (pin "6") (pinfunction "6_6") (pintype "passive"))
      (node (ref "J203") (pin "6") (pinfunction "6_6") (pintype "passive"))
      (node (ref "J204") (pin "6") (pinfunction "6_6") (pintype "passive"))
      (node (ref "J301") (pin "GND") (pinfunction "5_GND") (pintype "power_in"))
      (node (ref "J301") (pin "GND1") (pinfunction "GND1_GND1") (pintype "bidirectional"))
      (node (ref "J301") (pin "GND2") (pinfunction "GND2_GND2") (pintype "bidirectional"))
      (node (ref "J301") (pin "GND3") (pinfunction "GND3_GND3") (pintype "bidirectional"))
      (node (ref "J301") (pin "GND4") (pinfunction "GND4_GND4") (pintype "bidirectional"))
      (node (ref "J302") (pin "4") (pinfunction "4_4") (pintype "passive"))
      (node (ref "J401") (pin "4") (pinfunction "4_4") (pintype "passive"))
      (node (ref "J402") (pin "3") (pinfunction "3_3") (pintype "passive"))
      (node (ref "J403") (pin "7") (pinfunction "7_7") (pintype "passive"))
      (node (ref "J404") (pin "3") (pinfunction "3_3") (pintype "passive"))
      (node (ref "J404") (pin "5") (pinfunction "5_5") (pintype "passive"))
      (node (ref "J405") (pin "4") (pinfunction "4_4") (pintype "passive"))
      (node (ref "J601") (pin "5") (pinfunction "5_5") (pintype "passive"))
      (node (ref "J601") (pin "6") (pinfunction "6_6") (pintype "passive"))
      (node (ref "J701") (pin "2") (pinfunction "2_2") (pintype "passive"))
      (node (ref "J801") (pin "P$2") (pinfunction "P$2_P$2") (pintype "bidirectional"))
      (node (ref "J901") (pin "12") (pinfunction "S_12") (pintype "passive"))
      (node (ref "J901") (pin "15") (pinfunction "S_15") (pintype "passive"))
      (node (ref "J901") (pin "18") (pinfunction "S_18") (pintype "passive"))
      (node (ref "J901") (pin "21") (pinfunction "S_21") (pintype "passive"))
      (node (ref "J901") (pin "24") (pinfunction "S_24") (pintype "passive"))
      (node (ref "J901") (pin "27") (pinfunction "S_27") (pintype "passive"))
      (node (ref "J901") (pin "3") (pinfunction "S_3") (pintype "passive"))
      (node (ref "J901") (pin "30") (pinfunction "S_30") (pintype "passive"))
      (node (ref "J901") (pin "33") (pinfunction "S_33") (pintype "passive"))
      (node (ref "J901") (pin "36") (pinfunction "S_36") (pintype "passive"))
      (node (ref "J901") (pin "39") (pinfunction "S_39") (pintype "passive"))
      (node (ref "J901") (pin "42") (pinfunction "S_42") (pintype "passive"))
      (node (ref "J901") (pin "45") (pinfunction "S_45") (pintype "passive"))
      (node (ref "J901") (pin "48") (pinfunction "S_48") (pintype "passive"))
      (node (ref "J901") (pin "6") (pinfunction "S_6") (pintype "passive"))
      (node (ref "J901") (pin "9") (pinfunction "S_9") (pintype "passive"))
      (node (ref "JX301") (pin "3") (pinfunction "S_3") (pintype "passive"))
      (node (ref "JX301") (pin "5") (pinfunction "S_5") (pintype "passive"))
      (node (ref "JX301") (pin "9") (pinfunction "S_9") (pintype "passive"))
      (node (ref "JX801") (pin "3") (pinfunction "GND_3") (pintype "bidirectional"))
      (node (ref "JX802") (pin "3") (pinfunction "S_3") (pintype "passive"))
      (node (ref "JX802") (pin "5") (pinfunction "S_5") (pintype "passive"))
      (node (ref "JX802") (pin "9") (pinfunction "S_9") (pintype "passive"))
      (node (ref "L1101") (pin "P$3") (pinfunction "P$3_P$3") (pintype "bidirectional"))
      (node (ref "L1101") (pin "P$4") (pinfunction "P$3_P$4") (pintype "bidirectional"))
      (node (ref "L1101") (pin "P$5") (pinfunction "P$3_P$5") (pintype "bidirectional"))
      (node (ref "L1102") (pin "P$3") (pinfunction "P$3_P$3") (pintype "bidirectional"))
      (node (ref "L1102") (pin "P$4") (pinfunction "P$3_P$4") (pintype "bidirectional"))
      (node (ref "L1102") (pin "P$5") (pinfunction "P$3_P$5") (pintype "bidirectional"))
      (node (ref "L201") (pin "P$3") (pinfunction "P$3_P$3") (pintype "bidirectional"))
      (node (ref "L201") (pin "P$4") (pinfunction "P$3_P$4") (pintype "bidirectional"))
      (node (ref "L201") (pin "P$5") (pinfunction "P$3_P$5") (pintype "bidirectional"))
      (node (ref "L202") (pin "P$3") (pinfunction "P$3_P$3") (pintype "bidirectional"))
      (node (ref "L202") (pin "P$4") (pinfunction "P$3_P$4") (pintype "bidirectional"))
      (node (ref "L202") (pin "P$5") (pinfunction "P$3_P$5") (pintype "bidirectional"))
      (node (ref "L203") (pin "P$3") (pinfunction "P$3_P$3") (pintype "bidirectional"))
      (node (ref "L203") (pin "P$4") (pinfunction "P$3_P$4") (pintype "bidirectional"))
      (node (ref "L203") (pin "P$5") (pinfunction "P$3_P$5") (pintype "bidirectional"))
      (node (ref "L401") (pin "P$3") (pinfunction "P$3_P$3") (pintype "bidirectional"))
      (node (ref "L401") (pin "P$4") (pinfunction "P$3_P$4") (pintype "bidirectional"))
      (node (ref "L401") (pin "P$5") (pinfunction "P$3_P$5") (pintype "bidirectional"))
      (node (ref "L402") (pin "P$3") (pinfunction "P$3_P$3") (pintype "bidirectional"))
      (node (ref "L402") (pin "P$4") (pinfunction "P$3_P$4") (pintype "bidirectional"))
      (node (ref "L402") (pin "P$5") (pinfunction "P$3_P$5") (pintype "bidirectional"))
      (node (ref "L403") (pin "P$3") (pinfunction "P$3_P$3") (pintype "bidirectional"))
      (node (ref "L403") (pin "P$4") (pinfunction "P$3_P$4") (pintype "bidirectional"))
      (node (ref "L403") (pin "P$5") (pinfunction "P$3_P$5") (pintype "bidirectional"))
      (node (ref "L404") (pin "P$3") (pinfunction "P$3_P$3") (pintype "bidirectional"))
      (node (ref "L404") (pin "P$4") (pinfunction "P$3_P$4") (pintype "bidirectional"))
      (node (ref "L404") (pin "P$5") (pinfunction "P$3_P$5") (pintype "bidirectional"))
      (node (ref "L603") (pin "P$3") (pinfunction "P$3_P$3") (pintype "bidirectional"))
      (node (ref "L603") (pin "P$4") (pinfunction "P$3_P$4") (pintype "bidirectional"))
      (node (ref "L603") (pin "P$5") (pinfunction "P$3_P$5") (pintype "bidirectional"))
      (node (ref "L901") (pin "P$3") (pinfunction "P$3_P$3") (pintype "bidirectional"))
      (node (ref "L901") (pin "P$4") (pinfunction "P$3_P$4") (pintype "bidirectional"))
      (node (ref "L901") (pin "P$5") (pinfunction "P$3_P$5") (pintype "bidirectional"))
      (node (ref "R1001") (pin "P$1") (pinfunction "1_P$1") (pintype "passive"))
      (node (ref "R1002") (pin "P$1") (pinfunction "1_P$1") (pintype "passive"))
      (node (ref "R102") (pin "P$2") (pinfunction "2_P$2") (pintype "passive"))
      (node (ref "R1103") (pin "P$2") (pinfunction "2_P$2") (pintype "passive"))
      (node (ref "R1104") (pin "P$2") (pinfunction "2_P$2") (pintype "passive"))
      (node (ref "R1107") (pin "P$2") (pinfunction "2_P$2") (pintype "passive"))
      (node (ref "R1111") (pin "P$2") (pinfunction "2_P$2") (pintype "passive"))
      (node (ref "R1114") (pin "P$2") (pinfunction "2_P$2") (pintype "passive"))
      (node (ref "R1115") (pin "P$1") (pinfunction "1_P$1") (pintype "passive"))
      (node (ref "R403") (pin "P$1") (pinfunction "1_P$1") (pintype "passive"))
      (node (ref "R610") (pin "P$2") (pinfunction "2_P$2") (pintype "passive"))
      (node (ref "R611") (pin "P$1") (pinfunction "1_P$1") (pintype "passive"))
      (node (ref "R615") (pin "P$2") (pinfunction "2_P$2") (pintype "passive"))
      (node (ref "R616") (pin "P$2") (pinfunction "2_P$2") (pintype "passive"))
      (node (ref "R617") (pin "P$2") (pinfunction "2_P$2") (pintype "passive"))
      (node (ref "R621") (pin "1") (pinfunction "1_1") (pintype "passive"))
      (node (ref "R702") (pin "P$2") (pinfunction "2_P$2") (pintype "passive"))
      (node (ref "R704") (pin "P$1") (pinfunction "1_P$1") (pintype "passive"))
      (node (ref "R706") (pin "P$2") (pinfunction "2_P$2") (pintype "passive"))
      (node (ref "R708") (pin "P$1") (pinfunction "1_P$1") (pintype "passive"))
      (node (ref "R711") (pin "P$1") (pinfunction "1_P$1") (pintype "passive"))
      (node (ref "R713") (pin "P$2") (pinfunction "2_P$2") (pintype "passive"))
      (node (ref "R801") (pin "P$2") (pinfunction "2_P$2") (pintype "passive"))
      (node (ref "R802") (pin "P$2") (pinfunction "2_P$2") (pintype "passive"))
      (node (ref "R919") (pin "P$1") (pinfunction "1_P$1") (pintype "passive"))
      (node (ref "S601") (pin "B3") (pinfunction "2_B3") (pintype "passive"))
      (node (ref "S801") (pin "B3") (pinfunction "2_B3") (pintype "passive"))
      (node (ref "U1001") (pin "2") (pinfunction "VSS_2") (pintype "bidirectional"))
      (node (ref "U1001") (pin "5") (pinfunction "~{CE}_5") (pintype "bidirectional"))
      (node (ref "U1001") (pin "6") (pinfunction "VBAT_6") (pintype "bidirectional"))
      (node (ref "U1001") (pin "GND") (pinfunction "VSS_GND") (pintype "bidirectional"))
      (node (ref "U1001") (pin "P$2") (pinfunction "VSS_P$2") (pintype "bidirectional"))
      (node (ref "U1001") (pin "P$3") (pinfunction "VSS_P$3") (pintype "bidirectional"))
      (node (ref "U1002") (pin "2") (pinfunction "GND_2") (pintype "bidirectional"))
      (node (ref "U1002") (pin "GND") (pinfunction "GND_GND") (pintype "bidirectional"))
      (node (ref "U101") (pin "10") (pinfunction "VSS_10") (pintype "power_in"))
      (node (ref "U101") (pin "20") (pinfunction "VSSA_20") (pintype "power_in"))
      (node (ref "U101") (pin "27") (pinfunction "VSS_27") (pintype "power_in"))
      (node (ref "U101") (pin "74") (pinfunction "VSS_74") (pintype "power_in"))
      (node (ref "U101") (pin "99") (pinfunction "VSS_99") (pintype "power_in"))
      (node (ref "U102") (pin "4") (pinfunction "VSS_4") (pintype "bidirectional"))
      (node (ref "U1101") (pin "P$10") (pinfunction "GND_P$10") (pintype "bidirectional"))
      (node (ref "U1101") (pin "P$25") (pinfunction "GND_P$25") (pintype "bidirectional"))
      (node (ref "U201") (pin "11") (pinfunction "GND_11") (pintype "power_in"))
      (node (ref "U202") (pin "11") (pinfunction "GND_11") (pintype "power_in"))
      (node (ref "U301") (pin "6") (pinfunction "GND_6") (pintype "power_in"))
      (node (ref "U302") (pin "2") (pinfunction "GND_2") (pintype "bidirectional"))
      (node (ref "U401") (pin "2") (pinfunction "GND_2") (pintype "power_in"))
      (node (ref "U401") (pin "5") (pinfunction "SHDN_5") (pintype "input"))
      (node (ref "U401") (pin "8") (pinfunction "RS_8") (pintype "input"))
      (node (ref "U501") (pin "10") (pinfunction "RES_P10_GND_10") (pintype "bidirectional"))
      (node (ref "U501") (pin "11") (pinfunction "RES_P11_GND_11") (pintype "bidirectional"))
      (node (ref "U501") (pin "12") (pinfunction "RES_P12_GND_12") (pintype "bidirectional"))
      (node (ref "U501") (pin "13") (pinfunction "GND_13") (pintype "bidirectional"))
      (node (ref "U501") (pin "8") (pinfunction "RES_P8_GND_8") (pintype "bidirectional"))
      (node (ref "U501") (pin "9") (pinfunction "RES_P9_GND_9") (pintype "bidirectional"))
      (node (ref "U502") (pin "10") (pinfunction "GND_10") (pintype "bidirectional"))
      (node (ref "U502") (pin "11") (pinfunction "GND_11") (pintype "bidirectional"))
      (node (ref "U502") (pin "12") (pinfunction "GND_12") (pintype "bidirectional"))
      (node (ref "U502") (pin "13") (pinfunction "GND_13") (pintype "bidirectional"))
      (node (ref "U502") (pin "9") (pinfunction "GND_9") (pintype "bidirectional"))
      (node (ref "U504") (pin "10") (pinfunction "RSRV_10") (pintype "bidirectional"))
      (node (ref "U504") (pin "12") (pinfunction "GND_12") (pintype "bidirectional"))
      (node (ref "U504") (pin "13") (pinfunction "GND_13") (pintype "bidirectional"))
      (node (ref "U504") (pin "16") (pinfunction "GND_16") (pintype "bidirectional"))
      (node (ref "U504") (pin "5") (pinfunction "GND_5") (pintype "bidirectional"))
      (node (ref "U505") (pin "1") (pinfunction "CLKIN_1") (pintype "bidirectional"))
      (node (ref "U505") (pin "18") (pinfunction "GND_18") (pintype "bidirectional"))
      (node (ref "U506") (pin "2") (pinfunction "PS_2") (pintype "bidirectional"))
      (node (ref "U506") (pin "3") (pinfunction "GND_3") (pintype "bidirectional"))
      (node (ref "U601") (pin "2") (pinfunction "VSS_2") (pintype "bidirectional"))
      (node (ref "U601") (pin "6") (pinfunction "VBAT_6") (pintype "bidirectional"))
      (node (ref "U601") (pin "GND") (pinfunction "VSS_GND") (pintype "bidirectional"))
      (node (ref "U601") (pin "P$2") (pinfunction "VSS_P$2") (pintype "bidirectional"))
      (node (ref "U601") (pin "P$3") (pinfunction "VSS_P$3") (pintype "bidirectional"))
      (node (ref "U602") (pin "2") (pinfunction "VSS_2") (pintype "bidirectional"))
      (node (ref "U602") (pin "6") (pinfunction "VBAT_6") (pintype "bidirectional"))
      (node (ref "U602") (pin "GND") (pinfunction "VSS_GND") (pintype "bidirectional"))
      (node (ref "U602") (pin "P$2") (pinfunction "VSS_P$2") (pintype "bidirectional"))
      (node (ref "U602") (pin "P$3") (pinfunction "VSS_P$3") (pintype "bidirectional"))
      (node (ref "U603") (pin "2") (pinfunction "GND_2") (pintype "bidirectional"))
      (node (ref "U603") (pin "GND") (pinfunction "GND_GND") (pintype "bidirectional"))
      (node (ref "U701") (pin "5") (pinfunction "GND_5") (pintype "power_in"))
      (node (ref "U702") (pin "4") (pinfunction "GND_4") (pintype "power_in"))
      (node (ref "U801") (pin "23") (pinfunction "VSS_1_23") (pintype "power_in"))
      (node (ref "U801") (pin "35") (pinfunction "VSS_2_35") (pintype "power_in"))
      (node (ref "U801") (pin "47") (pinfunction "VSS_3_47") (pintype "power_in"))
      (node (ref "U801") (pin "8") (pinfunction "VSSA_8") (pintype "power_in"))
      (node (ref "U901") (pin "11") (pinfunction "GND_11") (pintype "power_in"))
      (node (ref "U902") (pin "11") (pinfunction "GND_11") (pintype "power_in"))
      (node (ref "U903") (pin "1") (pinfunction "~{1OE}_1") (pintype "input"))
      (node (ref "U903") (pin "4") (pinfunction "GND_4") (pintype "power_in"))
      (node (ref "X101") (pin "2") (pinfunction "NC_2_2") (pintype "power_in"))
      (node (ref "X101") (pin "4") (pinfunction "NC_4_4") (pintype "power_in"))
      (node (ref "X503") (pin "2") (pinfunction "S_2") (pintype "passive"))
      (node (ref "X801") (pin "2") (pinfunction "NC_2_2") (pintype "power_in"))
      (node (ref "X801") (pin "4") (pinfunction "NC_4_4") (pintype "power_in"))
    )
    (net (code "47") (name "GPIO_EXT_1") (class "Default")
      (node (ref "J403") (pin "6") (pinfunction "6_6") (pintype "passive"))
      (node (ref "U101") (pin "8") (pinfunction "PC14_8") (pintype "bidirectional"))
    )
    (net (code "48") (name "GYRO_DRDY") (class "Default")
      (node (ref "U101") (pin "35") (pinfunction "PB0_35") (pintype "bidirectional"))
      (node (ref "U501") (pin "6") (pinfunction "DRDY/INT2_6") (pintype "output"))
      (node (ref "U502") (pin "6") (pinfunction "DRDY/INT2_6") (pintype "bidirectional"))
      (node (ref "X503") (pin "5") (pinfunction "S_5") (pintype "passive"))
    )
    (net (code "49") (name "IO-BOOT0") (class "Default")
      (node (ref "IO-BOOT1101") (pin "P$1") (pinfunction "P$1_P$1") (pintype "passive"))
      (node (ref "R801") (pin "P$1") (pinfunction "1_P$1") (pintype "passive"))
      (node (ref "U801") (pin "44") (pinfunction "BOOT0_44") (pintype "input"))
    )
    (net (code "50") (name "IO-CH1") (class "Default")
      (node (ref "U801") (pin "10") (pinfunction "PA0_10") (pintype "bidirectional"))
      (node (ref "U902") (pin "9") (pinfunction "A8_9") (pintype "bidirectional"))
    )
    (net (code "51") (name "IO-CH2") (class "Default")
      (node (ref "U801") (pin "11") (pinfunction "PA1_11") (pintype "bidirectional"))
      (node (ref "U902") (pin "8") (pinfunction "A7_8") (pintype "bidirectional"))
    )
    (net (code "52") (name "IO-CH3") (class "Default")
      (node (ref "U801") (pin "45") (pinfunction "PB8_45") (pintype "bidirectional"))
      (node (ref "U902") (pin "7") (pinfunction "A6_7") (pintype "bidirectional"))
    )
    (net (code "53") (name "IO-CH4") (class "Default")
      (node (ref "U801") (pin "46") (pinfunction "PB9_46") (pintype "bidirectional"))
      (node (ref "U902") (pin "6") (pinfunction "A5_6") (pintype "bidirectional"))
    )
    (net (code "54") (name "IO-CH5") (class "Default")
      (node (ref "U801") (pin "16") (pinfunction "PA6_16") (pintype "bidirectional"))
      (node (ref "U902") (pin "5") (pinfunction "A4_5") (pintype "bidirectional"))
    )
    (net (code "55") (name "IO-CH6") (class "Default")
      (node (ref "U801") (pin "17") (pinfunction "PA7_17") (pintype "bidirectional"))
      (node (ref "U902") (pin "4") (pinfunction "A3_4") (pintype "bidirectional"))
    )
    (net (code "56") (name "IO-CH7") (class "Default")
      (node (ref "U801") (pin "18") (pinfunction "PB0_18") (pintype "bidirectional"))
      (node (ref "U902") (pin "3") (pinfunction "A2_3") (pintype "bidirectional"))
    )
    (net (code "57") (name "IO-CH8") (class "Default")
      (node (ref "U801") (pin "19") (pinfunction "PB1_19") (pintype "bidirectional"))
      (node (ref "U902") (pin "1") (pinfunction "A1_1") (pintype "bidirectional"))
    )
    (net (code "58") (name "IO-SWCLK") (class "Default")
      (node (ref "JX802") (pin "4") (pinfunction "S_4") (pintype "passive"))
      (node (ref "U801") (pin "37") (pinfunction "PA14_37") (pintype "bidirectional"))
    )
    (net (code "59") (name "IO-SWDIO") (class "Default")
      (node (ref "JX802") (pin "2") (pinfunction "S_2") (pintype "passive"))
      (node (ref "U801") (pin "34") (pinfunction "PA13_34") (pintype "bidirectional"))
    )
    (net (code "60") (name "IO-SWO") (class "Default")
      (node (ref "JX802") (pin "6") (pinfunction "S_6") (pintype "passive"))
      (node (ref "U801") (pin "39") (pinfunction "PB3_39") (pintype "bidirectional"))
    )
    (net (code "61") (name "IO-USART1_RX") (class "Default")
      (node (ref "J801") (pin "P$3") (pinfunction "P$3_P$3") (pintype "bidirectional"))
      (node (ref "JX801") (pin "2") (pinfunction "+5V_2") (pintype "bidirectional"))
      (node (ref "U801") (pin "31") (pinfunction "PA10_31") (pintype "bidirectional"))
    )
    (net (code "62") (name "IO-USART1_TX") (class "Default")
      (node (ref "JX801") (pin "1") (pinfunction "PPM_1") (pintype "bidirectional"))
      (node (ref "R101") (pin "P$2") (pinfunction "2_P$2") (pintype "passive"))
      (node (ref "U801") (pin "30") (pinfunction "PA9_30") (pintype "bidirectional"))
    )
    (net (code "63") (name "IO-VDD_3V3") (class "Default")
      (node (ref "C1003") (pin "P$1") (pinfunction "1_P$1") (pintype "passive"))
      (node (ref "C1004") (pin "P$1") (pinfunction "1_P$1") (pintype "passive"))
      (node (ref "C802") (pin "P$1") (pinfunction "1_P$1") (pintype "passive"))
      (node (ref "C803") (pin "P$1") (pinfunction "1_P$1") (pintype "passive"))
      (node (ref "C804") (pin "P$1") (pinfunction "1_P$1") (pintype "passive"))
      (node (ref "C901") (pin "P$1") (pinfunction "1_P$1") (pintype "passive"))
      (node (ref "C903") (pin "P$1") (pinfunction "1_P$1") (pintype "passive"))
      (node (ref "D701") (pin "C") (pinfunction "C_C") (pintype "passive"))
      (node (ref "J702") (pin "1") (pinfunction "1_1") (pintype "passive"))
      (node (ref "JX802") (pin "1") (pinfunction "S_1") (pintype "passive"))
      (node (ref "U1002") (pin "7") (pinfunction "VOUT2_7") (pintype "bidirectional"))
      (node (ref "U801") (pin "24") (pinfunction "VDD_1_24") (pintype "power_in"))
      (node (ref "U801") (pin "36") (pinfunction "VDD_2_36") (pintype "power_in"))
      (node (ref "U801") (pin "48") (pinfunction "VDD_3_48") (pintype "power_in"))
      (node (ref "U801") (pin "9") (pinfunction "VDDA_9") (pintype "power_in"))
      (node (ref "U902") (pin "10") (pinfunction "OE_10") (pintype "input"))
      (node (ref "U902") (pin "19") (pinfunction "VCCB_19") (pintype "input"))
      (node (ref "U902") (pin "2") (pinfunction "VCCA_2") (pintype "input"))
      (node (ref "U903") (pin "8") (pinfunction "VCC_8") (pintype "power_in"))
    )
    (net (code "64") (name "IO-VDD_5V5") (class "Default")
      (node (ref "C1001") (pin "P$1") (pinfunction "1_P$1") (pintype "passive"))
      (node (ref "C1005") (pin "P$1") (pinfunction "1_P$1") (pintype "passive"))
      (node (ref "D1001") (pin "3") (pinfunction "CC_3") (pintype "passive"))
      (node (ref "J901") (pin "2") (pinfunction "S_2") (pintype "passive"))
      (node (ref "LED702") (pin "A") (pinfunction "A_A") (pintype "passive"))
      (node (ref "LED703") (pin "A") (pinfunction "A_A") (pintype "passive"))
      (node (ref "LED705") (pin "A") (pinfunction "A_A") (pintype "passive"))
      (node (ref "U1002") (pin "1") (pinfunction "VIN_1") (pintype "bidirectional"))
      (node (ref "U1002") (pin "4") (pinfunction "EN2_4") (pintype "bidirectional"))
    )
    (net (code "65") (name "IO-~{RESET}") (class "Default")
      (node (ref "C801") (pin "P$2") (pinfunction "2_P$2") (pintype "passive"))
      (node (ref "S801") (pin "A1") (pinfunction "1_A1") (pintype "passive"))
      (node (ref "U1002") (pin "3") (pinfunction "POR2_3") (pintype "bidirectional"))
      (node (ref "U801") (pin "7") (pinfunction "NRST_7") (pintype "input"))
    )
    (net (code "66") (name "IO-~{VDD_SERVO_IN_FAULT}") (class "Default")
      (node (ref "U1001") (pin "4") (pinfunction "~{FAULT}_4") (pintype "bidirectional"))
      (node (ref "U801") (pin "38") (pinfunction "PA15_38") (pintype "bidirectional"))
    )
    (net (code "67") (name "MAG_DRDY") (class "Default")
      (node (ref "U101") (pin "36") (pinfunction "PB1_36") (pintype "bidirectional"))
      (node (ref "U504") (pin "9") (pinfunction "INT2_9") (pintype "bidirectional"))
      (node (ref "X503") (pin "4") (pinfunction "S_4") (pintype "passive"))
    )
    (net (code "68") (name "MPU_DRDY") (class "Default")
      (node (ref "U101") (pin "62") (pinfunction "PD15_62") (pintype "bidirectional"))
      (node (ref "U505") (pin "12") (pinfunction "INT_12") (pintype "bidirectional"))
    )
    (net (code "69") (name "Net-(C102-1)") (class "Default")
      (node (ref "C102") (pin "P$1") (pinfunction "1_P$1") (pintype "passive"))
      (node (ref "U101") (pin "12") (pinfunction "OSC_IN_12") (pintype "input"))
      (node (ref "X101") (pin "3") (pinfunction "3_3") (pintype "bidirectional"))
    )
    (net (code "70") (name "Net-(C103-2)") (class "Default")
      (node (ref "C103") (pin "P$2") (pinfunction "2_P$2") (pintype "passive"))
      (node (ref "U101") (pin "13") (pinfunction "OSC_OUT_13") (pintype "output"))
      (node (ref "X101") (pin "1") (pinfunction "1_1") (pintype "bidirectional"))
    )
    (net (code "71") (name "Net-(C504-1)") (class "Default")
      (node (ref "C504") (pin "P$1") (pinfunction "1_P$1") (pintype "passive"))
      (node (ref "U501") (pin "14") (pinfunction "PLLFILT_14") (pintype "bidirectional"))
    )
    (net (code "72") (name "Net-(C505-1)") (class "Default")
      (node (ref "C505") (pin "P$1") (pinfunction "1_P$1") (pintype "passive"))
      (node (ref "U502") (pin "14") (pinfunction "CAP_14") (pintype "bidirectional"))
    )
    (net (code "73") (name "Net-(C509-1)") (class "Default")
      (node (ref "C509") (pin "P$1") (pinfunction "1_P$1") (pintype "passive"))
      (node (ref "U504") (pin "15") (pinfunction "C1_15") (pintype "bidirectional"))
    )
    (net (code "74") (name "Net-(C510-1)") (class "Default")
      (node (ref "C510") (pin "P$1") (pinfunction "1_P$1") (pintype "passive"))
      (node (ref "U504") (pin "2") (pinfunction "SETC_2") (pintype "bidirectional"))
    )
    (net (code "75") (name "Net-(C510-2)") (class "Default")
      (node (ref "C510") (pin "P$2") (pinfunction "2_P$2") (pintype "passive"))
      (node (ref "U504") (pin "3") (pinfunction "SETP_3") (pintype "bidirectional"))
    )
    (net (code "76") (name "Net-(C512-1)") (class "Default")
      (node (ref "C512") (pin "P$1") (pinfunction "1_P$1") (pintype "passive"))
      (node (ref "U505") (pin "10") (pinfunction "REGOUT_10") (pintype "bidirectional"))
    )
    (net (code "77") (name "Net-(C515-1)") (class "Default")
      (node (ref "C515") (pin "P$1") (pinfunction "1_P$1") (pintype "passive"))
      (node (ref "U505") (pin "20") (pinfunction "CPOUT_20") (pintype "bidirectional"))
    )
    (net (code "78") (name "Net-(C601-1)") (class "Default")
      (node (ref "C601") (pin "P$1") (pinfunction "1_P$1") (pintype "passive"))
      (node (ref "C615") (pin "P$1") (pinfunction "1_P$1") (pintype "passive"))
      (node (ref "L603") (pin "P$2") (pinfunction "P$2_P$2") (pintype "bidirectional"))
      (node (ref "R603") (pin "P$1") (pinfunction "1_P$1") (pintype "passive"))
      (node (ref "U603") (pin "1") (pinfunction "VIN_1") (pintype "bidirectional"))
      (node (ref "U603") (pin "4") (pinfunction "EN2_4") (pintype "bidirectional"))
    )
    (net (code "79") (name "Net-(C602-2)") (class "Default")
      (node (ref "C602") (pin "P$2") (pinfunction "2_P$2") (pintype "passive"))
      (node (ref "U603") (pin "6") (pinfunction "CSET_6") (pintype "bidirectional"))
    )
    (net (code "80") (name "Net-(C611-1)") (class "Default")
      (node (ref "C611") (pin "P$1") (pinfunction "1_P$1") (pintype "passive"))
      (node (ref "U101") (pin "49") (pinfunction "VCAP_1_49") (pintype "power_in"))
    )
    (net (code "81") (name "Net-(C613-1)") (class "Default")
      (node (ref "C613") (pin "P$1") (pinfunction "1_P$1") (pintype "passive"))
      (node (ref "U101") (pin "73") (pinfunction "VCAP_2_73") (pintype "power_in"))
    )
    (net (code "82") (name "Net-(C703-1)") (class "Default")
      (node (ref "C703") (pin "P$1") (pinfunction "1_P$1") (pintype "passive"))
      (node (ref "J701") (pin "1") (pinfunction "1_1") (pintype "passive"))
      (node (ref "R703") (pin "P$1") (pinfunction "1_P$1") (pintype "passive"))
      (node (ref "U702") (pin "1") (pinfunction "OUT_1") (pintype "output"))
    )
    (net (code "83") (name "Net-(C704-1)") (class "Default")
      (node (ref "C704") (pin "P$1") (pinfunction "1_P$1") (pintype "passive"))
      (node (ref "R705") (pin "P$1") (pinfunction "1_P$1") (pintype "passive"))
      (node (ref "U702") (pin "6") (pinfunction "VCC_6") (pintype "bidirectional"))
    )
    (net (code "84") (name "Net-(C805-1)") (class "Default")
      (node (ref "C805") (pin "P$1") (pinfunction "1_P$1") (pintype "passive"))
      (node (ref "U801") (pin "5") (pinfunction "PD0/OSC<=_5") (pintype "bidirectional"))
      (node (ref "X801") (pin "3") (pinfunction "3_3") (pintype "bidirectional"))
    )
    (net (code "85") (name "Net-(C806-2)") (class "Default")
      (node (ref "C806") (pin "P$2") (pinfunction "2_P$2") (pintype "passive"))
      (node (ref "U801") (pin "6") (pinfunction "PD1/OSC=>_6") (pintype "bidirectional"))
      (node (ref "X801") (pin "1") (pinfunction "1_1") (pintype "bidirectional"))
    )
    (net (code "86") (name "Net-(C1002-1)") (class "Default")
      (node (ref "C1002") (pin "P$1") (pinfunction "1_P$1") (pintype "passive"))
      (node (ref "U1002") (pin "6") (pinfunction "CSET_6") (pintype "bidirectional"))
    )
    (net (code "87") (name "Net-(C1105-1)") (class "Default")
      (node (ref "C1105") (pin "P$1") (pinfunction "1_P$1") (pintype "passive"))
      (node (ref "U1101") (pin "P$18") (pinfunction "VS1_P$18") (pintype "bidirectional"))
      (node (ref "U1102") (pin "P$1") (pinfunction "S_P$1") (pintype "passive"))
      (node (ref "U1102") (pin "P$3") (pinfunction "S_P$3") (pintype "passive"))
    )
    (net (code "88") (name "Net-(C1106-1)") (class "Default")
      (node (ref "C1106") (pin "P$1") (pinfunction "1_P$1") (pintype "passive"))
      (node (ref "U1101") (pin "P$16") (pinfunction "VS2_P$16") (pintype "bidirectional"))
      (node (ref "U1103") (pin "P$1") (pinfunction "S_P$1") (pintype "passive"))
      (node (ref "U1103") (pin "P$3") (pinfunction "S_P$3") (pintype "passive"))
    )
    (net (code "89") (name "Net-(C1107-1)") (class "Default")
      (node (ref "C1107") (pin "P$1") (pinfunction "1_P$1") (pintype "passive"))
      (node (ref "U1101") (pin "P$14") (pinfunction "VS3_P$14") (pintype "bidirectional"))
      (node (ref "U1104") (pin "P$1") (pinfunction "S_P$1") (pintype "passive"))
      (node (ref "U1104") (pin "P$3") (pinfunction "S_P$3") (pintype "passive"))
    )
    (net (code "90") (name "Net-(C1108-1)") (class "Default")
      (node (ref "C1108") (pin "P$1") (pinfunction "1_P$1") (pintype "passive"))
      (node (ref "R1105") (pin "P$2") (pinfunction "2_P$2") (pintype "passive"))
      (node (ref "R1106") (pin "P$1") (pinfunction "1_P$1") (pintype "passive"))
      (node (ref "U1101") (pin "P$1") (pinfunction "UV1_P$1") (pintype "bidirectional"))
    )
    (net (code "91") (name "Net-(C1109-1)") (class "Default")
      (node (ref "C1109") (pin "P$1") (pinfunction "1_P$1") (pintype "passive"))
      (node (ref "R1109") (pin "P$2") (pinfunction "2_P$2") (pintype "passive"))
      (node (ref "R1110") (pin "P$1") (pinfunction "1_P$1") (pintype "passive"))
      (node (ref "U1101") (pin "P$3") (pinfunction "UV2_P$3") (pintype "bidirectional"))
    )
    (net (code "92") (name "Net-(C1110-1)") (class "Default")
      (node (ref "C1110") (pin "P$1") (pinfunction "1_P$1") (pintype "passive"))
      (node (ref "R1112") (pin "P$2") (pinfunction "2_P$2") (pintype "passive"))
      (node (ref "R1113") (pin "P$1") (pinfunction "1_P$1") (pintype "passive"))
      (node (ref "U1101") (pin "P$5") (pinfunction "UV3_P$5") (pintype "bidirectional"))
    )
    (net (code "93") (name "Net-(D1-C)") (class "Default")
      (node (ref "D1") (pin "CATHODE") (pinfunction "C_CATHODE") (pintype "passive"))
      (node (ref "D903") (pin "C") (pinfunction "C_C") (pintype "passive"))
      (node (ref "L901") (pin "P$1") (pinfunction "P$1_P$1") (pintype "bidirectional"))
    )
    (net (code "94") (name "Net-(D201-PadC)") (class "Default")
      (node (ref "D201") (pin "C") (pinfunction "C_C") (pintype "passive"))
      (node (ref "J201") (pin "1") (pinfunction "1_1") (pintype "passive"))
      (node (ref "L201") (pin "P$2") (pinfunction "P$2_P$2") (pintype "bidirectional"))
    )
    (net (code "95") (name "Net-(D202-PadC)") (class "Default")
      (node (ref "D202") (pin "C") (pinfunction "C_C") (pintype "passive"))
      (node (ref "J202") (pin "1") (pinfunction "1_1") (pintype "passive"))
      (node (ref "L202") (pin "P$2") (pinfunction "P$2_P$2") (pintype "bidirectional"))
    )
    (net (code "96") (name "Net-(D203-PadC)") (class "Default")
      (node (ref "D203") (pin "C") (pinfunction "C_C") (pintype "passive"))
      (node (ref "J203") (pin "1") (pinfunction "1_1") (pintype "passive"))
      (node (ref "J204") (pin "1") (pinfunction "1_1") (pintype "passive"))
      (node (ref "L203") (pin "P$2") (pinfunction "P$2_P$2") (pintype "bidirectional"))
    )
    (net (code "97") (name "Net-(D401-PadC)") (class "Default")
      (node (ref "D401") (pin "C") (pinfunction "C_C") (pintype "passive"))
      (node (ref "J401") (pin "1") (pinfunction "1_1") (pintype "passive"))
      (node (ref "J402") (pin "1") (pinfunction "1_1") (pintype "passive"))
      (node (ref "L401") (pin "P$2") (pinfunction "P$2_P$2") (pintype "bidirectional"))
    )
    (net (code "98") (name "Net-(D402-PadC)") (class "Default")
      (node (ref "D402") (pin "C") (pinfunction "C_C") (pintype "passive"))
      (node (ref "J403") (pin "1") (pinfunction "1_1") (pintype "passive"))
      (node (ref "L402") (pin "P$2") (pinfunction "P$2_P$2") (pintype "bidirectional"))
    )
    (net (code "99") (name "Net-(D403-PadC)") (class "Default")
      (node (ref "D403") (pin "C") (pinfunction "C_C") (pintype "passive"))
      (node (ref "J404") (pin "1") (pinfunction "1_1") (pintype "passive"))
      (node (ref "L404") (pin "P$2") (pinfunction "P$2_P$2") (pintype "bidirectional"))
    )
    (net (code "100") (name "Net-(D404-PadC)") (class "Default")
      (node (ref "D404") (pin "C") (pinfunction "C_C") (pintype "passive"))
      (node (ref "J405") (pin "1") (pinfunction "1_1") (pintype "passive"))
      (node (ref "L403") (pin "P$2") (pinfunction "P$2_P$2") (pintype "bidirectional"))
    )
    (net (code "101") (name "Net-(D1001-A1)") (class "Default")
      (node (ref "D1001") (pin "1") (pinfunction "A1_1") (pintype "passive"))
      (node (ref "F1001") (pin "2") (pinfunction "2_2") (pintype "bidirectional"))
    )
    (net (code "102") (name "Net-(D1001-A2)") (class "Default")
      (node (ref "D1001") (pin "2") (pinfunction "A2_2") (pintype "passive"))
      (node (ref "U1001") (pin "8") (pinfunction "OUT_8") (pintype "bidirectional"))
    )
    (net (code "103") (name "Net-(J301-2)") (class "Default")
      (node (ref "J301") (pin "D-") (pinfunction "2_D-") (pintype "bidirectional"))
      (node (ref "J302") (pin "3") (pinfunction "3_3") (pintype "passive"))
      (node (ref "U302") (pin "1") (pinfunction "D1I_1") (pintype "bidirectional"))
    )
    (net (code "104") (name "Net-(J301-3)") (class "Default")
      (node (ref "J301") (pin "D+") (pinfunction "3_D+") (pintype "bidirectional"))
      (node (ref "J302") (pin "2") (pinfunction "2_2") (pintype "passive"))
      (node (ref "U302") (pin "3") (pinfunction "D2I_3") (pintype "bidirectional"))
    )
    (net (code "105") (name "Net-(J901A-S)") (class "Default")
      (node (ref "J901") (pin "1") (pinfunction "S_1") (pintype "passive"))
      (node (ref "R909") (pin "P$2") (pinfunction "2_P$2") (pintype "passive"))
    )
    (net (code "106") (name "Net-(J901B-S)") (class "Default")
      (node (ref "J901") (pin "10") (pinfunction "S_10") (pintype "passive"))
      (node (ref "R914") (pin "P$2") (pinfunction "2_P$2") (pintype "passive"))
    )
    (net (code "107") (name "Net-(J901C-S)") (class "Default")
      (node (ref "J901") (pin "13") (pinfunction "S_13") (pintype "passive"))
      (node (ref "R906") (pin "P$2") (pinfunction "2_P$2") (pintype "passive"))
    )
    (net (code "108") (name "Net-(J901D-S)") (class "Default")
      (node (ref "J901") (pin "16") (pinfunction "S_16") (pintype "passive"))
      (node (ref "R915") (pin "P$2") (pinfunction "2_P$2") (pintype "passive"))
    )
    (net (code "109") (name "Net-(J901E-S)") (class "Default")
      (node (ref "J901") (pin "19") (pinfunction "S_19") (pintype "passive"))
      (node (ref "R907") (pin "P$2") (pinfunction "2_P$2") (pintype "passive"))
    )
    (net (code "110") (name "Net-(J901G-S)") (class "Default")
      (node (ref "J901") (pin "22") (pinfunction "S_22") (pintype "passive"))
      (node (ref "R916") (pin "P$2") (pinfunction "2_P$2") (pintype "passive"))
    )
    (net (code "111") (name "Net-(J901H-S)") (class "Default")
      (node (ref "J901") (pin "25") (pinfunction "S_25") (pintype "passive"))
      (node (ref "R908") (pin "P$2") (pinfunction "2_P$2") (pintype "passive"))
    )
    (net (code "112") (name "Net-(J901I-S)") (class "Default")
      (node (ref "J901") (pin "28") (pinfunction "S_28") (pintype "passive"))
      (node (ref "R917") (pin "P$2") (pinfunction "2_P$2") (pintype "passive"))
    )
    (net (code "113") (name "Net-(J901J-S)") (class "Default")
      (node (ref "J901") (pin "31") (pinfunction "S_31") (pintype "passive"))
      (node (ref "R902") (pin "P$2") (pinfunction "2_P$2") (pintype "passive"))
    )
    (net (code "114") (name "Net-(J901K-S)") (class "Default")
      (node (ref "J901") (pin "34") (pinfunction "S_34") (pintype "passive"))
      (node (ref "R911") (pin "P$2") (pinfunction "2_P$2") (pintype "passive"))
    )
    (net (code "115") (name "Net-(J901L-S)") (class "Default")
      (node (ref "J901") (pin "37") (pinfunction "S_37") (pintype "passive"))
      (node (ref "R903") (pin "P$2") (pinfunction "2_P$2") (pintype "passive"))
    )
    (net (code "116") (name "Net-(J901M-S)") (class "Default")
      (node (ref "J901") (pin "4") (pinfunction "S_4") (pintype "passive"))
      (node (ref "R910") (pin "P$2") (pinfunction "2_P$2") (pintype "passive"))
    )
    (net (code "117") (name "Net-(J901N-S)") (class "Default")
      (node (ref "J901") (pin "40") (pinfunction "S_40") (pintype "passive"))
      (node (ref "R912") (pin "P$2") (pinfunction "2_P$2") (pintype "passive"))
    )
    (net (code "118") (name "Net-(J901O-S)") (class "Default")
      (node (ref "J901") (pin "43") (pinfunction "S_43") (pintype "passive"))
      (node (ref "R904") (pin "P$2") (pinfunction "2_P$2") (pintype "passive"))
    )
    (net (code "119") (name "Net-(J901P-S)") (class "Default")
      (node (ref "J901") (pin "46") (pinfunction "S_46") (pintype "passive"))
      (node (ref "R913") (pin "P$2") (pinfunction "2_P$2") (pintype "passive"))
    )
    (net (code "120") (name "Net-(J901Q-S)") (class "Default")
      (node (ref "J901") (pin "7") (pinfunction "S_7") (pintype "passive"))
      (node (ref "R905") (pin "P$2") (pinfunction "2_P$2") (pintype "passive"))
    )
    (net (code "121") (name "Net-(L701-2)") (class "Default")
      (node (ref "L701") (pin "P$2") (pinfunction "2_P$2") (pintype "passive"))
      (node (ref "U702") (pin "5") (pinfunction "SW_5") (pintype "passive"))
    )
    (net (code "122") (name "Net-(Q601-PadC)") (class "Default")
      (node (ref "Q601") (pin "C") (pinfunction "C_C") (pintype "passive"))
      (node (ref "R621") (pin "2") (pinfunction "2_2") (pintype "passive"))
    )
    (net (code "123") (name "Net-(R3-1)") (class "Default")
      (node (ref "R3") (pin "P$1") (pinfunction "1_P$1") (pintype "passive"))
      (node (ref "R707") (pin "P$2") (pinfunction "2_P$2") (pintype "passive"))
    )
    (net (code "124") (name "Net-(R3-2)") (class "Default")
      (node (ref "LED701") (pin "C") (pinfunction "C_C") (pintype "passive"))
      (node (ref "R3") (pin "P$2") (pinfunction "2_P$2") (pintype "passive"))
    )
    (net (code "125") (name "Net-(R4-1)") (class "Default")
      (node (ref "R4") (pin "P$1") (pinfunction "1_P$1") (pintype "passive"))
      (node (ref "R709") (pin "P$2") (pinfunction "2_P$2") (pintype "passive"))
    )
    (net (code "126") (name "Net-(R4-2)") (class "Default")
      (node (ref "LED703") (pin "C") (pinfunction "C_C") (pintype "passive"))
      (node (ref "R4") (pin "P$2") (pinfunction "2_P$2") (pintype "passive"))
    )
    (net (code "127") (name "Net-(R101-1)") (class "Default")
      (node (ref "R101") (pin "P$1") (pinfunction "1_P$1") (pintype "passive"))
      (node (ref "U101") (pin "69") (pinfunction "PA10_69") (pintype "bidirectional"))
    )
    (net (code "128") (name "Net-(R102-1)") (class "Default")
      (node (ref "R102") (pin "P$1") (pinfunction "1_P$1") (pintype "passive"))
      (node (ref "U101") (pin "37") (pinfunction "PB2_37") (pintype "bidirectional"))
    )
    (net (code "129") (name "Net-(R201-1)") (class "Default")
      (node (ref "R201") (pin "P$1") (pinfunction "1_P$1") (pintype "passive"))
      (node (ref "U201") (pin "20") (pinfunction "B1_20") (pintype "bidirectional"))
    )
    (net (code "130") (name "Net-(R202-1)") (class "Default")
      (node (ref "R202") (pin "P$1") (pinfunction "1_P$1") (pintype "passive"))
      (node (ref "U201") (pin "17") (pinfunction "B3_17") (pintype "bidirectional"))
    )
    (net (code "131") (name "Net-(R203-1)") (class "Default")
      (node (ref "R203") (pin "P$1") (pinfunction "1_P$1") (pintype "passive"))
      (node (ref "U201") (pin "15") (pinfunction "B5_15") (pintype "bidirectional"))
    )
    (net (code "132") (name "Net-(R204-1)") (class "Default")
      (node (ref "R204") (pin "P$1") (pinfunction "1_P$1") (pintype "passive"))
      (node (ref "U201") (pin "13") (pinfunction "B7_13") (pintype "bidirectional"))
    )
    (net (code "133") (name "Net-(R205-1)") (class "Default")
      (node (ref "R205") (pin "P$1") (pinfunction "1_P$1") (pintype "passive"))
      (node (ref "U202") (pin "17") (pinfunction "B3_17") (pintype "bidirectional"))
    )
    (net (code "134") (name "Net-(R206-1)") (class "Default")
      (node (ref "R206") (pin "P$1") (pinfunction "1_P$1") (pintype "passive"))
      (node (ref "U202") (pin "15") (pinfunction "B5_15") (pintype "bidirectional"))
    )
    (net (code "135") (name "Net-(R207-1)") (class "Default")
      (node (ref "R207") (pin "P$1") (pinfunction "1_P$1") (pintype "passive"))
      (node (ref "U202") (pin "13") (pinfunction "B7_13") (pintype "bidirectional"))
    )
    (net (code "136") (name "Net-(R208-1)") (class "Default")
      (node (ref "R208") (pin "P$1") (pinfunction "1_P$1") (pintype "passive"))
      (node (ref "U201") (pin "18") (pinfunction "B2_18") (pintype "bidirectional"))
    )
    (net (code "137") (name "Net-(R209-1)") (class "Default")
      (node (ref "R209") (pin "P$1") (pinfunction "1_P$1") (pintype "passive"))
      (node (ref "U201") (pin "16") (pinfunction "B4_16") (pintype "bidirectional"))
    )
    (net (code "138") (name "Net-(R210-1)") (class "Default")
      (node (ref "R210") (pin "P$1") (pinfunction "1_P$1") (pintype "passive"))
      (node (ref "U201") (pin "14") (pinfunction "B6_14") (pintype "bidirectional"))
    )
    (net (code "139") (name "Net-(R211-1)") (class "Default")
      (node (ref "R211") (pin "P$1") (pinfunction "1_P$1") (pintype "passive"))
      (node (ref "U201") (pin "12") (pinfunction "B8_12") (pintype "bidirectional"))
    )
    (net (code "140") (name "Net-(R212-1)") (class "Default")
      (node (ref "R212") (pin "P$1") (pinfunction "1_P$1") (pintype "passive"))
      (node (ref "U202") (pin "16") (pinfunction "B4_16") (pintype "bidirectional"))
    )
    (net (code "141") (name "Net-(R213-1)") (class "Default")
      (node (ref "R213") (pin "P$1") (pinfunction "1_P$1") (pintype "passive"))
      (node (ref "U202") (pin "14") (pinfunction "B6_14") (pintype "bidirectional"))
    )
    (net (code "142") (name "Net-(R214-1)") (class "Default")
      (node (ref "R214") (pin "P$1") (pinfunction "1_P$1") (pintype "passive"))
      (node (ref "U202") (pin "12") (pinfunction "B8_12") (pintype "bidirectional"))
    )
    (net (code "143") (name "Net-(R215-2)") (class "Default")
      (node (ref "J203") (pin "4") (pinfunction "4_4") (pintype "passive"))
      (node (ref "R215") (pin "P$2") (pinfunction "2_P$2") (pintype "passive"))
    )
    (net (code "144") (name "Net-(R216-2)") (class "Default")
      (node (ref "J203") (pin "5") (pinfunction "5_5") (pintype "passive"))
      (node (ref "R216") (pin "P$2") (pinfunction "2_P$2") (pintype "passive"))
    )
    (net (code "145") (name "Net-(R404-2)") (class "Default")
      (node (ref "J401") (pin "2") (pinfunction "2_2") (pintype "passive"))
      (node (ref "R404") (pin "P$2") (pinfunction "2_P$2") (pintype "passive"))
    )
    (net (code "146") (name "Net-(R405-2)") (class "Default")
      (node (ref "J401") (pin "3") (pinfunction "3_3") (pintype "passive"))
      (node (ref "R405") (pin "P$2") (pinfunction "2_P$2") (pintype "passive"))
    )
    (net (code "147") (name "Net-(R407-2)") (class "Default")
      (node (ref "J404") (pin "2") (pinfunction "2_2") (pintype "passive"))
      (node (ref "R407") (pin "P$2") (pinfunction "2_P$2") (pintype "passive"))
    )
    (net (code "148") (name "Net-(R408-2)") (class "Default")
      (node (ref "J404") (pin "4") (pinfunction "4_4") (pintype "passive"))
      (node (ref "R408") (pin "P$2") (pinfunction "2_P$2") (pintype "passive"))
    )
    (net (code "149") (name "Net-(R608-2)") (class "Default")
      (node (ref "D2") (pin "C") (pinfunction "C_C") (pintype "passive"))
      (node (ref "R608") (pin "P$2") (pinfunction "2_P$2") (pintype "passive"))
    )
    (net (code "150") (name "Net-(R616-1)") (class "Default")
      (node (ref "R616") (pin "P$1") (pinfunction "1_P$1") (pintype "passive"))
      (node (ref "U602") (pin "7") (pinfunction "ILIM_7") (pintype "bidirectional"))
    )
    (net (code "151") (name "Net-(R617-1)") (class "Default")
      (node (ref "R617") (pin "P$1") (pinfunction "1_P$1") (pintype "passive"))
      (node (ref "U601") (pin "7") (pinfunction "ILIM_7") (pintype "bidirectional"))
    )
    (net (code "152") (name "Net-(R620-1)") (class "Default")
      (node (ref "Q601") (pin "B") (pinfunction "B_B") (pintype "passive"))
      (node (ref "R620") (pin "P$1") (pinfunction "1_P$1") (pintype "passive"))
    )
    (net (code "153") (name "Net-(R701-1)") (class "Default")
      (node (ref "R701") (pin "P$1") (pinfunction "1_P$1") (pintype "passive"))
      (node (ref "U702") (pin "7") (pinfunction "+IN_7") (pintype "input"))
    )
    (net (code "154") (name "Net-(R702-1)") (class "Default")
      (node (ref "R702") (pin "P$1") (pinfunction "1_P$1") (pintype "passive"))
      (node (ref "R703") (pin "P$2") (pinfunction "2_P$2") (pintype "passive"))
      (node (ref "U702") (pin "8") (pinfunction "-IN_8") (pintype "input"))
    )
    (net (code "155") (name "Net-(R704-2)") (class "Default")
      (node (ref "R704") (pin "P$2") (pinfunction "2_P$2") (pintype "passive"))
      (node (ref "U701") (pin "6") (pinfunction "REXT_6") (pintype "bidirectional"))
    )
    (net (code "156") (name "Net-(R705-2)") (class "Default")
      (node (ref "R705") (pin "P$2") (pinfunction "2_P$2") (pintype "passive"))
      (node (ref "R706") (pin "P$1") (pinfunction "1_P$1") (pintype "passive"))
      (node (ref "U702") (pin "2") (pinfunction "FB_2") (pintype "bidirectional"))
    )
    (net (code "157") (name "Net-(R708-2)") (class "Default")
      (node (ref "LED702") (pin "C") (pinfunction "C_C") (pintype "passive"))
      (node (ref "R708") (pin "P$2") (pinfunction "2_P$2") (pintype "passive"))
    )
    (net (code "158") (name "Net-(R710-1)") (class "Default")
      (node (ref "J702") (pin "2") (pinfunction "2_2") (pintype "passive"))
      (node (ref "R710") (pin "P$1") (pinfunction "1_P$1") (pintype "passive"))
    )
    (net (code "159") (name "Net-(R711-2)") (class "Default")
      (node (ref "LED704") (pin "C") (pinfunction "C_C") (pintype "passive"))
      (node (ref "R711") (pin "P$2") (pinfunction "2_P$2") (pintype "passive"))
    )
    (net (code "160") (name "Net-(R712-2)") (class "Default")
      (node (ref "LED705") (pin "C") (pinfunction "C_C") (pintype "passive"))
      (node (ref "R712") (pin "P$2") (pinfunction "2_P$2") (pintype "passive"))
    )
    (net (code "161") (name "Net-(R802-1)") (class "Default")
      (node (ref "R802") (pin "P$1") (pinfunction "1_P$1") (pintype "passive"))
      (node (ref "U801") (pin "20") (pinfunction "PB2_20") (pintype "bidirectional"))
    )
    (net (code "162") (name "Net-(R803-1)") (class "Default")
      (node (ref "R803") (pin "P$1") (pinfunction "1_P$1") (pintype "passive"))
      (node (ref "U801") (pin "12") (pinfunction "PA2_12") (pintype "bidirectional"))
    )
    (net (code "163") (name "Net-(R804-1)") (class "Default")
      (node (ref "R804") (pin "P$1") (pinfunction "1_P$1") (pintype "passive"))
      (node (ref "U801") (pin "13") (pinfunction "PA3_13") (pintype "bidirectional"))
    )
    (net (code "164") (name "Net-(R901-2)") (class "Default")
      (node (ref "D902") (pin "C") (pinfunction "C_C") (pintype "passive"))
      (node (ref "R901") (pin "P$2") (pinfunction "2_P$2") (pintype "passive"))
      (node (ref "R910") (pin "P$1") (pinfunction "1_P$1") (pintype "passive"))
      (node (ref "U903") (pin "3") (pinfunction "2Y_3") (pintype "bidirectional"))
    )
    (net (code "165") (name "Net-(R902-1)") (class "Default")
      (node (ref "R902") (pin "P$1") (pinfunction "1_P$1") (pintype "passive"))
      (node (ref "U901") (pin "20") (pinfunction "B1_20") (pintype "bidirectional"))
    )
    (net (code "166") (name "Net-(R903-1)") (class "Default")
      (node (ref "R903") (pin "P$1") (pinfunction "1_P$1") (pintype "passive"))
      (node (ref "U901") (pin "17") (pinfunction "B3_17") (pintype "bidirectional"))
    )
    (net (code "167") (name "Net-(R904-1)") (class "Default")
      (node (ref "R904") (pin "P$1") (pinfunction "1_P$1") (pintype "passive"))
      (node (ref "U901") (pin "15") (pinfunction "B5_15") (pintype "bidirectional"))
    )
    (net (code "168") (name "Net-(R905-1)") (class "Default")
      (node (ref "R905") (pin "P$1") (pinfunction "1_P$1") (pintype "passive"))
      (node (ref "U902") (pin "20") (pinfunction "B1_20") (pintype "bidirectional"))
    )
    (net (code "169") (name "Net-(R906-1)") (class "Default")
      (node (ref "R906") (pin "P$1") (pinfunction "1_P$1") (pintype "passive"))
      (node (ref "U902") (pin "17") (pinfunction "B3_17") (pintype "bidirectional"))
    )
    (net (code "170") (name "Net-(R907-1)") (class "Default")
      (node (ref "R907") (pin "P$1") (pinfunction "1_P$1") (pintype "passive"))
      (node (ref "U902") (pin "15") (pinfunction "B5_15") (pintype "bidirectional"))
    )
    (net (code "171") (name "Net-(R908-1)") (class "Default")
      (node (ref "R908") (pin "P$1") (pinfunction "1_P$1") (pintype "passive"))
      (node (ref "U902") (pin "13") (pinfunction "B7_13") (pintype "bidirectional"))
    )
    (net (code "172") (name "Net-(R911-1)") (class "Default")
      (node (ref "R911") (pin "P$1") (pinfunction "1_P$1") (pintype "passive"))
      (node (ref "U901") (pin "18") (pinfunction "B2_18") (pintype "bidirectional"))
    )
    (net (code "173") (name "Net-(R912-1)") (class "Default")
      (node (ref "R912") (pin "P$1") (pinfunction "1_P$1") (pintype "passive"))
      (node (ref "U901") (pin "16") (pinfunction "B4_16") (pintype "bidirectional"))
    )
    (net (code "174") (name "Net-(R913-1)") (class "Default")
      (node (ref "R913") (pin "P$1") (pinfunction "1_P$1") (pintype "passive"))
      (node (ref "U901") (pin "14") (pinfunction "B6_14") (pintype "bidirectional"))
    )
    (net (code "175") (name "Net-(R914-1)") (class "Default")
      (node (ref "R914") (pin "P$1") (pinfunction "1_P$1") (pintype "passive"))
      (node (ref "U902") (pin "18") (pinfunction "B2_18") (pintype "bidirectional"))
    )
    (net (code "176") (name "Net-(R915-1)") (class "Default")
      (node (ref "R915") (pin "P$1") (pinfunction "1_P$1") (pintype "passive"))
      (node (ref "U902") (pin "16") (pinfunction "B4_16") (pintype "bidirectional"))
    )
    (net (code "177") (name "Net-(R916-1)") (class "Default")
      (node (ref "R916") (pin "P$1") (pinfunction "1_P$1") (pintype "passive"))
      (node (ref "U902") (pin "14") (pinfunction "B6_14") (pintype "bidirectional"))
    )
    (net (code "178") (name "Net-(R917-1)") (class "Default")
      (node (ref "R917") (pin "P$1") (pinfunction "1_P$1") (pintype "passive"))
      (node (ref "U902") (pin "12") (pinfunction "B8_12") (pintype "bidirectional"))
    )
    (net (code "179") (name "Net-(R918-2)") (class "Default")
      (node (ref "R918") (pin "P$2") (pinfunction "2_P$2") (pintype "passive"))
      (node (ref "R922") (pin "P$1") (pinfunction "1_P$1") (pintype "passive"))
    )
    (net (code "180") (name "Net-(R1001-2)") (class "Default")
      (node (ref "R1001") (pin "P$2") (pinfunction "2_P$2") (pintype "passive"))
      (node (ref "U1001") (pin "7") (pinfunction "ILIM_7") (pintype "bidirectional"))
    )
    (net (code "181") (name "Net-(R1101-2)") (class "Default")
      (node (ref "L1101") (pin "P$2") (pinfunction "P$2_P$2") (pintype "bidirectional"))
      (node (ref "R1101") (pin "P$2") (pinfunction "2_P$2") (pintype "passive"))
    )
    (net (code "182") (name "Net-(R1102-2)") (class "Default")
      (node (ref "L1102") (pin "P$2") (pinfunction "P$2_P$2") (pintype "bidirectional"))
      (node (ref "R1102") (pin "P$2") (pinfunction "2_P$2") (pintype "passive"))
    )
    (net (code "183") (name "Net-(R1103-1)") (class "Default")
      (node (ref "J601") (pin "4") (pinfunction "4_4") (pintype "passive"))
      (node (ref "L1102") (pin "P$1") (pinfunction "P$1_P$1") (pintype "bidirectional"))
      (node (ref "R1103") (pin "P$1") (pinfunction "1_P$1") (pintype "passive"))
    )
    (net (code "184") (name "Net-(R1104-1)") (class "Default")
      (node (ref "J601") (pin "3") (pinfunction "3_3") (pintype "passive"))
      (node (ref "L1101") (pin "P$1") (pinfunction "P$1_P$1") (pintype "bidirectional"))
      (node (ref "R1104") (pin "P$1") (pinfunction "1_P$1") (pintype "passive"))
    )
    (net (code "185") (name "Net-(R1106-2)") (class "Default")
      (node (ref "R1106") (pin "P$2") (pinfunction "2_P$2") (pintype "passive"))
      (node (ref "R1107") (pin "P$1") (pinfunction "1_P$1") (pintype "passive"))
      (node (ref "U1101") (pin "P$2") (pinfunction "OV1_P$2") (pintype "bidirectional"))
    )
    (net (code "186") (name "Net-(R1110-2)") (class "Default")
      (node (ref "R1110") (pin "P$2") (pinfunction "2_P$2") (pintype "passive"))
      (node (ref "R1111") (pin "P$1") (pinfunction "1_P$1") (pintype "passive"))
      (node (ref "U1101") (pin "P$4") (pinfunction "OV2_P$4") (pintype "bidirectional"))
    )
    (net (code "187") (name "Net-(R1113-2)") (class "Default")
      (node (ref "R1113") (pin "P$2") (pinfunction "2_P$2") (pintype "passive"))
      (node (ref "R1114") (pin "P$1") (pinfunction "1_P$1") (pintype "passive"))
      (node (ref "U1101") (pin "P$6") (pinfunction "OV3_P$6") (pintype "bidirectional"))
    )
    (net (code "188") (name "Net-(R1115-2)") (class "Default")
      (node (ref "R1115") (pin "P$2") (pinfunction "2_P$2") (pintype "passive"))
      (node (ref "U1101") (pin "P$24") (pinfunction "HYS_P$24") (pintype "bidirectional"))
    )
    (net (code "189") (name "Net-(U701-OUT0)") (class "Default")
      (node (ref "U701") (pin "9") (pinfunction "OUT0_9") (pintype "open_collector"))
      (node (ref "U703") (pin "C1") (pinfunction "C_C1") (pintype "passive"))
    )
    (net (code "190") (name "Net-(U701-OUT1)") (class "Default")
      (node (ref "U701") (pin "8") (pinfunction "OUT1_8") (pintype "open_collector"))
      (node (ref "U703") (pin "C2") (pinfunction "C_C2") (pintype "passive"))
    )
    (net (code "191") (name "Net-(U701-OUT2)") (class "Default")
      (node (ref "U701") (pin "7") (pinfunction "OUT2_7") (pintype "open_collector"))
      (node (ref "U703") (pin "C3") (pinfunction "C_C3") (pintype "passive"))
    )
    (net (code "192") (name "Net-(U1101-G1)") (class "Default")
      (node (ref "U1101") (pin "P$17") (pinfunction "G1_P$17") (pintype "bidirectional"))
      (node (ref "U1102") (pin "P$2") (pinfunction "G_P$2") (pintype "passive"))
      (node (ref "U1102") (pin "P$4") (pinfunction "G_P$4") (pintype "passive"))
    )
    (net (code "193") (name "Net-(U1101-G2)") (class "Default")
      (node (ref "U1101") (pin "P$15") (pinfunction "G2_P$15") (pintype "bidirectional"))
      (node (ref "U1103") (pin "P$2") (pinfunction "G_P$2") (pintype "passive"))
      (node (ref "U1103") (pin "P$4") (pinfunction "G_P$4") (pintype "passive"))
    )
    (net (code "194") (name "Net-(U1101-G3)") (class "Default")
      (node (ref "U1101") (pin "P$13") (pinfunction "G3_P$13") (pintype "bidirectional"))
      (node (ref "U1104") (pin "P$2") (pinfunction "G_P$2") (pintype "passive"))
      (node (ref "U1104") (pin "P$4") (pinfunction "G_P$4") (pintype "passive"))
    )
    (net (code "195") (name "OTG_FS_DM") (class "Default")
      (node (ref "U101") (pin "70") (pinfunction "PA11_70") (pintype "bidirectional"))
      (node (ref "U302") (pin "6") (pinfunction "D1O_6") (pintype "bidirectional"))
    )
    (net (code "196") (name "OTG_FS_DP") (class "Default")
      (node (ref "U101") (pin "71") (pinfunction "PA12_71") (pintype "bidirectional"))
      (node (ref "U302") (pin "4") (pinfunction "D2O_4") (pintype "bidirectional"))
    )
    (net (code "197") (name "PPM_INPUT") (class "Default")
      (node (ref "D901") (pin "C") (pinfunction "C_C") (pintype "passive"))
      (node (ref "R909") (pin "P$1") (pinfunction "1_P$1") (pintype "passive"))
      (node (ref "U801") (pin "29") (pinfunction "PA8_29") (pintype "bidirectional"))
      (node (ref "U903") (pin "2") (pinfunction "1A_2") (pintype "bidirectional"))
    )
    (net (code "198") (name "PRESSURE_SENS") (class "Default")
      (node (ref "C401") (pin "P$1") (pinfunction "1_P$1") (pintype "passive"))
      (node (ref "R403") (pin "P$2") (pinfunction "2_P$2") (pintype "passive"))
      (node (ref "R406") (pin "P$1") (pinfunction "1_P$1") (pintype "passive"))
      (node (ref "U101") (pin "34") (pinfunction "PC5_34") (pintype "bidirectional"))
    )
    (net (code "199") (name "PRESSURE_SENS_IN") (class "Default")
      (node (ref "ADC_PR") (pin "P$1") (pinfunction "P$1_P$1") (pintype "passive"))
      (node (ref "J402") (pin "2") (pinfunction "2_2") (pintype "passive"))
      (node (ref "R406") (pin "P$2") (pinfunction "2_P$2") (pintype "passive"))
    )
    (net (code "200") (name "RSSI_IN") (class "Default")
      (node (ref "R901") (pin "P$1") (pinfunction "1_P$1") (pintype "passive"))
      (node (ref "U801") (pin "15") (pinfunction "PA5_15") (pintype "bidirectional"))
      (node (ref "U801") (pin "33") (pinfunction "PA12_33") (pintype "bidirectional"))
    )
    (net (code "201") (name "SAFETY") (class "Default")
      (node (ref "J702") (pin "3") (pinfunction "3_3") (pintype "passive"))
      (node (ref "R713") (pin "P$1") (pinfunction "1_P$1") (pintype "passive"))
      (node (ref "U801") (pin "41") (pinfunction "PB5_41") (pintype "bidirectional"))
    )
    (net (code "202") (name "SBUS_INPUT") (class "Default")
      (node (ref "U801") (pin "22") (pinfunction "PB11_22") (pintype "bidirectional"))
      (node (ref "U903") (pin "6") (pinfunction "1Y_6") (pintype "bidirectional"))
    )
    (net (code "203") (name "SBUS_OUTPUT") (class "Default")
      (node (ref "U801") (pin "21") (pinfunction "PB10_21") (pintype "bidirectional"))
      (node (ref "U903") (pin "5") (pinfunction "2A_5") (pintype "bidirectional"))
    )
    (net (code "204") (name "SDIO_CK") (class "Default")
      (node (ref "U101") (pin "80") (pinfunction "PC12_80") (pintype "bidirectional"))
      (node (ref "U301") (pin "5") (pinfunction "CLK_5") (pintype "bidirectional"))
    )
    (net (code "205") (name "SDIO_CMD") (class "Default")
      (node (ref "R303") (pin "P$1") (pinfunction "1_P$1") (pintype "passive"))
      (node (ref "U101") (pin "83") (pinfunction "PD2_83") (pintype "bidirectional"))
      (node (ref "U301") (pin "3") (pinfunction "CMD_3") (pintype "bidirectional"))
    )
    (net (code "206") (name "SDIO_D0") (class "Default")
      (node (ref "R304") (pin "P$1") (pinfunction "1_P$1") (pintype "passive"))
      (node (ref "U101") (pin "65") (pinfunction "PC8_65") (pintype "bidirectional"))
      (node (ref "U301") (pin "7") (pinfunction "D0_7") (pintype "bidirectional"))
    )
    (net (code "207") (name "SDIO_D1") (class "Default")
      (node (ref "R305") (pin "P$1") (pinfunction "1_P$1") (pintype "passive"))
      (node (ref "U101") (pin "66") (pinfunction "PC9_66") (pintype "bidirectional"))
      (node (ref "U301") (pin "8") (pinfunction "D1_8") (pintype "bidirectional"))
    )
    (net (code "208") (name "SDIO_D2") (class "Default")
      (node (ref "R301") (pin "P$1") (pinfunction "1_P$1") (pintype "passive"))
      (node (ref "U101") (pin "78") (pinfunction "PC10_78") (pintype "bidirectional"))
      (node (ref "U301") (pin "1") (pinfunction "D2_1") (pintype "bidirectional"))
    )
    (net (code "209") (name "SDIO_D3") (class "Default")
      (node (ref "R302") (pin "P$1") (pinfunction "1_P$1") (pintype "passive"))
      (node (ref "U101") (pin "79") (pinfunction "PC11_79") (pintype "bidirectional"))
      (node (ref "U301") (pin "2") (pinfunction "D3_2") (pintype "bidirectional"))
    )
    (net (code "210") (name "SERIAL1_CTS") (class "Default")
      (node (ref "J201") (pin "4") (pinfunction "4_4") (pintype "passive"))
      (node (ref "R211") (pin "P$2") (pinfunction "2_P$2") (pintype "passive"))
    )
    (net (code "211") (name "SERIAL1_RTS") (class "Default")
      (node (ref "J201") (pin "5") (pinfunction "5_5") (pintype "passive"))
      (node (ref "R204") (pin "P$2") (pinfunction "2_P$2") (pintype "passive"))
    )
    (net (code "212") (name "SERIAL1_RX") (class "Default")
      (node (ref "J201") (pin "3") (pinfunction "3_3") (pintype "passive"))
      (node (ref "R203") (pin "P$2") (pinfunction "2_P$2") (pintype "passive"))
      (node (ref "S1RX") (pin "P$1") (pinfunction "P$1_P$1") (pintype "passive"))
    )
    (net (code "213") (name "SERIAL1_TX") (class "Default")
      (node (ref "J201") (pin "2") (pinfunction "2_2") (pintype "passive"))
      (node (ref "R210") (pin "P$2") (pinfunction "2_P$2") (pintype "passive"))
      (node (ref "S1TX") (pin "P$1") (pinfunction "P$1_P$1") (pintype "passive"))
    )
    (net (code "214") (name "SERIAL2_CTS") (class "Default")
      (node (ref "J202") (pin "4") (pinfunction "4_4") (pintype "passive"))
      (node (ref "R208") (pin "P$2") (pinfunction "2_P$2") (pintype "passive"))
    )
    (net (code "215") (name "SERIAL2_RTS") (class "Default")
      (node (ref "J202") (pin "5") (pinfunction "5_5") (pintype "passive"))
      (node (ref "R201") (pin "P$2") (pinfunction "2_P$2") (pintype "passive"))
    )
    (net (code "216") (name "SERIAL2_RX") (class "Default")
      (node (ref "J202") (pin "3") (pinfunction "3_3") (pintype "passive"))
      (node (ref "R202") (pin "P$2") (pinfunction "2_P$2") (pintype "passive"))
      (node (ref "S2RX") (pin "P$1") (pinfunction "P$1_P$1") (pintype "passive"))
    )
    (net (code "217") (name "SERIAL2_TX") (class "Default")
      (node (ref "J202") (pin "2") (pinfunction "2_2") (pintype "passive"))
      (node (ref "R209") (pin "P$2") (pinfunction "2_P$2") (pintype "passive"))
      (node (ref "S2TX") (pin "P$1") (pinfunction "P$1_P$1") (pintype "passive"))
    )
    (net (code "218") (name "SERIAL3_RX") (class "Default")
      (node (ref "J203") (pin "3") (pinfunction "3_3") (pintype "passive"))
      (node (ref "R207") (pin "P$2") (pinfunction "2_P$2") (pintype "passive"))
      (node (ref "S3RX") (pin "P$1") (pinfunction "P$1_P$1") (pintype "passive"))
    )
    (net (code "219") (name "SERIAL3_TX") (class "Default")
      (node (ref "J203") (pin "2") (pinfunction "2_2") (pintype "passive"))
      (node (ref "R214") (pin "P$2") (pinfunction "2_P$2") (pintype "passive"))
      (node (ref "S3TX") (pin "P$1") (pinfunction "P$1_P$1") (pintype "passive"))
    )
    (net (code "220") (name "SERIAL4_RX") (class "Default")
      (node (ref "J204") (pin "3") (pinfunction "3_3") (pintype "passive"))
      (node (ref "R206") (pin "P$2") (pinfunction "2_P$2") (pintype "passive"))
      (node (ref "S4RX") (pin "P$1") (pinfunction "P$1_P$1") (pintype "passive"))
    )
    (net (code "221") (name "SERIAL4_TX") (class "Default")
      (node (ref "J204") (pin "2") (pinfunction "2_2") (pintype "passive"))
      (node (ref "R213") (pin "P$2") (pinfunction "2_P$2") (pintype "passive"))
      (node (ref "S4TX") (pin "P$1") (pinfunction "P$1_P$1") (pintype "passive"))
    )
    (net (code "222") (name "SERIAL5_RX") (class "Default")
      (node (ref "J204") (pin "5") (pinfunction "5_5") (pintype "passive"))
      (node (ref "R205") (pin "P$2") (pinfunction "2_P$2") (pintype "passive"))
      (node (ref "S5_RX") (pin "P$1") (pinfunction "P$1_P$1") (pintype "passive"))
    )
    (net (code "223") (name "SERIAL5_TX") (class "Default")
      (node (ref "J204") (pin "4") (pinfunction "4_4") (pintype "passive"))
      (node (ref "R212") (pin "P$2") (pinfunction "2_P$2") (pintype "passive"))
      (node (ref "S5_TX") (pin "P$1") (pinfunction "P$1_P$1") (pintype "passive"))
    )
    (net (code "224") (name "SERIAL_FMU_TO_IO") (class "Default")
      (node (ref "R804") (pin "P$2") (pinfunction "2_P$2") (pintype "passive"))
      (node (ref "U101") (pin "63") (pinfunction "PC6_63") (pintype "bidirectional"))
    )
    (net (code "225") (name "SERIAL_IO_TO_FMU") (class "Default")
      (node (ref "R803") (pin "P$2") (pinfunction "2_P$2") (pintype "passive"))
      (node (ref "U101") (pin "64") (pinfunction "PC7_64") (pintype "bidirectional"))
    )
    (net (code "226") (name "SPI_EXT_MISO") (class "Default")
      (node (ref "J403") (pin "3") (pinfunction "3_3") (pintype "passive"))
      (node (ref "U101") (pin "4") (pinfunction "PE5_4") (pintype "bidirectional"))
    )
    (net (code "227") (name "SPI_EXT_MOSI") (class "Default")
      (node (ref "J403") (pin "4") (pinfunction "4_4") (pintype "passive"))
      (node (ref "U101") (pin "5") (pinfunction "PE6_5") (pintype "bidirectional"))
    )
    (net (code "228") (name "SPI_EXT_SCK") (class "Default")
      (node (ref "J403") (pin "2") (pinfunction "2_2") (pintype "passive"))
      (node (ref "U101") (pin "1") (pinfunction "PE2_1") (pintype "bidirectional"))
    )
    (net (code "229") (name "SPI_INT_MISO") (class "Default")
      (node (ref "U101") (pin "31") (pinfunction "PA6_31") (pintype "bidirectional"))
      (node (ref "U501") (pin "4") (pinfunction "SDO/SA0_4") (pintype "bidirectional"))
      (node (ref "U502") (pin "4") (pinfunction "SDO/SA0_4") (pintype "bidirectional"))
      (node (ref "U504") (pin "7") (pinfunction "SDO/SA0_7") (pintype "bidirectional"))
      (node (ref "U505") (pin "9") (pinfunction "AD0/SDO_9") (pintype "bidirectional"))
      (node (ref "U506") (pin "6") (pinfunction "SDO_6") (pintype "bidirectional"))
      (node (ref "X503") (pin "9") (pinfunction "S_9") (pintype "passive"))
    )
    (net (code "230") (name "SPI_INT_MOSI") (class "Default")
      (node (ref "U101") (pin "32") (pinfunction "PA7_32") (pintype "bidirectional"))
      (node (ref "U501") (pin "3") (pinfunction "SDA/SDI/SDO_3") (pintype "bidirectional"))
      (node (ref "U502") (pin "3") (pinfunction "SDA/SDI/SDO_3") (pintype "bidirectional"))
      (node (ref "U504") (pin "6") (pinfunction "SDA/SDI/SDO_6") (pintype "bidirectional"))
      (node (ref "U505") (pin "24") (pinfunction "SDA/SDI_24") (pintype "bidirectional"))
      (node (ref "U506") (pin "7") (pinfunction "SDI/SDA_7") (pintype "bidirectional"))
      (node (ref "X503") (pin "8") (pinfunction "S_8") (pintype "passive"))
    )
    (net (code "231") (name "SPI_INT_SCK") (class "Default")
      (node (ref "U101") (pin "30") (pinfunction "PA5_30") (pintype "bidirectional"))
      (node (ref "U501") (pin "2") (pinfunction "SCL/SPC_2") (pintype "input"))
      (node (ref "U502") (pin "2") (pinfunction "SCL/SPC_2") (pintype "bidirectional"))
      (node (ref "U504") (pin "4") (pinfunction "SCL/SPC_4") (pintype "bidirectional"))
      (node (ref "U505") (pin "23") (pinfunction "SCL/SCLK_23") (pintype "bidirectional"))
      (node (ref "U506") (pin "8") (pinfunction "SCLK_8") (pintype "bidirectional"))
      (node (ref "X503") (pin "10") (pinfunction "S_10") (pintype "passive"))
    )
    (net (code "232") (name "VBAT") (class "Default")
      (node (ref "B601") (pin "1") (pinfunction "POS_1") (pintype "bidirectional"))
      (node (ref "R608") (pin "P$1") (pinfunction "1_P$1") (pintype "passive"))
      (node (ref "U101") (pin "6") (pinfunction "VBAT_6") (pintype "power_in"))
      (node (ref "U801") (pin "1") (pinfunction "VBAT_1") (pintype "power_in"))
    )
    (net (code "233") (name "VBUS") (class "Default")
      (node (ref "C1103") (pin "P$1") (pinfunction "1_P$1") (pintype "passive"))
      (node (ref "J301") (pin "VBUS") (pinfunction "1_VBUS") (pintype "power_in"))
      (node (ref "J302") (pin "1") (pinfunction "1_1") (pintype "passive"))
      (node (ref "R1112") (pin "P$1") (pinfunction "1_P$1") (pintype "passive"))
      (node (ref "U101") (pin "68") (pinfunction "PA9_68") (pintype "bidirectional"))
      (node (ref "U1101") (pin "P$19") (pinfunction "V3_P$19") (pintype "bidirectional"))
      (node (ref "U1104") (pin "P$7") (pinfunction "D_P$7") (pintype "passive"))
      (node (ref "U1104") (pin "P$8") (pinfunction "D_P$8") (pintype "passive"))
      (node (ref "U302") (pin "5") (pinfunction "VBUS_5") (pintype "bidirectional"))
      (node (ref "VBUS") (pin "P$1") (pinfunction "P$1_P$1") (pintype "passive"))
    )
    (net (code "234") (name "VDD_3V3_SENSORS") (class "Default")
      (node (ref "C501") (pin "P$1") (pinfunction "1_P$1") (pintype "passive"))
      (node (ref "C502") (pin "P$1") (pinfunction "1_P$1") (pintype "passive"))
      (node (ref "C503") (pin "P$1") (pinfunction "1_P$1") (pintype "passive"))
      (node (ref "C506") (pin "P$1") (pinfunction "1_P$1") (pintype "passive"))
      (node (ref "C507") (pin "P$1") (pinfunction "1_P$1") (pintype "passive"))
      (node (ref "C508") (pin "P$1") (pinfunction "1_P$1") (pintype "passive"))
      (node (ref "C511") (pin "P$1") (pinfunction "1_P$1") (pintype "passive"))
      (node (ref "C513") (pin "P$1") (pinfunction "1_P$1") (pintype "passive"))
      (node (ref "C514") (pin "P$1") (pinfunction "1_P$1") (pintype "passive"))
      (node (ref "C605") (pin "P$1") (pinfunction "1_P$1") (pintype "passive"))
      (node (ref "C617") (pin "P$1") (pinfunction "1_P$1") (pintype "passive"))
      (node (ref "Q601") (pin "E") (pinfunction "E_E") (pintype "passive"))
      (node (ref "U501") (pin "1") (pinfunction "VDD_IO_1") (pintype "bidirectional"))
      (node (ref "U501") (pin "15") (pinfunction "RES_P15_VDD_15") (pintype "bidirectional"))
      (node (ref "U501") (pin "16") (pinfunction "VDD_16") (pintype "bidirectional"))
      (node (ref "U502") (pin "1") (pinfunction "VDD_IO_1") (pintype "bidirectional"))
      (node (ref "U502") (pin "15") (pinfunction "VDD_15") (pintype "bidirectional"))
      (node (ref "U502") (pin "16") (pinfunction "VDD_16") (pintype "bidirectional"))
      (node (ref "U504") (pin "1") (pinfunction "VDD_IO_1") (pintype "bidirectional"))
      (node (ref "U504") (pin "14") (pinfunction "VDD_14") (pintype "bidirectional"))
      (node (ref "U505") (pin "13") (pinfunction "VDD_13") (pintype "bidirectional"))
      (node (ref "U506") (pin "1") (pinfunction "VDD_1") (pintype "bidirectional"))
      (node (ref "U603") (pin "8") (pinfunction "VOUT1_8") (pintype "bidirectional"))
      (node (ref "VDDA_3V1101") (pin "P$1") (pinfunction "P$1_P$1") (pintype "passive"))
      (node (ref "X503") (pin "1") (pinfunction "S_1") (pintype "passive"))
    )
    (net (code "235") (name "VDD_3V3_SENSORS_EN") (class "Default")
      (node (ref "R603") (pin "P$2") (pinfunction "2_P$2") (pintype "passive"))
      (node (ref "R620") (pin "P$2") (pinfunction "2_P$2") (pintype "passive"))
      (node (ref "R635") (pin "P$2") (pinfunction "2_P$2") (pintype "passive"))
      (node (ref "U101") (pin "2") (pinfunction "PE3_2") (pintype "bidirectional"))
      (node (ref "U603") (pin "5") (pinfunction "EN1_5") (pintype "bidirectional"))
    )
    (net (code "236") (name "VDD_3V3_SPEKTRUM") (class "Default")
      (node (ref "C1008") (pin "P$1") (pinfunction "1_P$1") (pintype "passive"))
      (node (ref "D801") (pin "C") (pinfunction "C_C") (pintype "passive"))
      (node (ref "J801") (pin "P$1") (pinfunction "P$1_P$1") (pintype "bidirectional"))
      (node (ref "U1002") (pin "8") (pinfunction "VOUT1_8") (pintype "bidirectional"))
    )
    (net (code "237") (name "VDD_3V3_SPEKTRUM_EN") (class "Default")
      (node (ref "R1002") (pin "P$2") (pinfunction "2_P$2") (pintype "passive"))
      (node (ref "U1002") (pin "5") (pinfunction "EN1_5") (pintype "bidirectional"))
      (node (ref "U801") (pin "2") (pinfunction "PC13_2") (pintype "bidirectional"))
    )
    (net (code "238") (name "VDD_5V_BRICK") (class "Default")
      (node (ref "C1101") (pin "P$1") (pinfunction "1_P$1") (pintype "passive"))
      (node (ref "J601") (pin "1") (pinfunction "1_1") (pintype "passive"))
      (node (ref "J601") (pin "2") (pinfunction "2_2") (pintype "passive"))
      (node (ref "R1105") (pin "P$1") (pinfunction "1_P$1") (pintype "passive"))
      (node (ref "U1101") (pin "P$21") (pinfunction "V1_P$21") (pintype "bidirectional"))
      (node (ref "U1102") (pin "P$7") (pinfunction "D_P$7") (pintype "passive"))
      (node (ref "U1102") (pin "P$8") (pinfunction "D_P$8") (pintype "passive"))
      (node (ref "VDD_5V_BRICK") (pin "P$1") (pinfunction "P$1_P$1") (pintype "passive"))
    )
    (net (code "239") (name "VDD_5V_HIPOWER") (class "Default")
      (node (ref "C614") (pin "P$1") (pinfunction "1_P$1") (pintype "passive"))
      (node (ref "L201") (pin "P$1") (pinfunction "P$1_P$1") (pintype "bidirectional"))
      (node (ref "U601") (pin "8") (pinfunction "OUT_8") (pintype "bidirectional"))
    )
    (net (code "240") (name "VDD_5V_IN") (class "Default")
      (node (ref "C1104") (pin "P$1") (pinfunction "1_P$1") (pintype "passive"))
      (node (ref "C702") (pin "P$1") (pinfunction "1_P$1") (pintype "passive"))
      (node (ref "F1001") (pin "1") (pinfunction "1_1") (pintype "bidirectional"))
      (node (ref "L603") (pin "P$1") (pinfunction "P$1_P$1") (pintype "bidirectional"))
      (node (ref "L701") (pin "P$1") (pinfunction "1_P$1") (pintype "passive"))
      (node (ref "LED701") (pin "A") (pinfunction "A_A") (pintype "passive"))
      (node (ref "LED704") (pin "A") (pinfunction "A_A") (pintype "passive"))
      (node (ref "R609") (pin "P$2") (pinfunction "2_P$2") (pintype "passive"))
      (node (ref "RN1101") (pin "5") (pinfunction "2_5") (pintype "passive"))
      (node (ref "RN1101") (pin "6") (pinfunction "2_6") (pintype "passive"))
      (node (ref "RN1101") (pin "7") (pinfunction "2_7") (pintype "passive"))
      (node (ref "U1101") (pin "P$12") (pinfunction "VOUT_P$12") (pintype "bidirectional"))
      (node (ref "U1102") (pin "P$5") (pinfunction "D_P$5") (pintype "passive"))
      (node (ref "U1102") (pin "P$6") (pinfunction "D_P$6") (pintype "passive"))
      (node (ref "U1103") (pin "P$5") (pinfunction "D_P$5") (pintype "passive"))
      (node (ref "U1103") (pin "P$6") (pinfunction "D_P$6") (pintype "passive"))
      (node (ref "U1104") (pin "P$5") (pinfunction "D_P$5") (pintype "passive"))
      (node (ref "U1104") (pin "P$6") (pinfunction "D_P$6") (pintype "passive"))
      (node (ref "U601") (pin "1") (pinfunction "IN_1") (pintype "bidirectional"))
      (node (ref "U602") (pin "1") (pinfunction "IN_1") (pintype "bidirectional"))
      (node (ref "U702") (pin "3") (pinfunction "VIN_3") (pintype "power_in"))
      (node (ref "U703") (pin "A1") (pinfunction "A_A1") (pintype "passive"))
      (node (ref "U703") (pin "A2") (pinfunction "A_A2") (pintype "passive"))
      (node (ref "U703") (pin "A3") (pinfunction "A_A3") (pintype "passive"))
      (node (ref "VDD_5V_IN") (pin "P$1") (pinfunction "P$1_P$1") (pintype "passive"))
    )
    (net (code "241") (name "VDD_5V_PERIPH") (class "Default")
      (node (ref "C618") (pin "P$1") (pinfunction "1_P$1") (pintype "passive"))
      (node (ref "L202") (pin "P$1") (pinfunction "P$1_P$1") (pintype "bidirectional"))
      (node (ref "L203") (pin "P$1") (pinfunction "P$1_P$1") (pintype "bidirectional"))
      (node (ref "L401") (pin "P$1") (pinfunction "P$1_P$1") (pintype "bidirectional"))
      (node (ref "L402") (pin "P$1") (pinfunction "P$1_P$1") (pintype "bidirectional"))
      (node (ref "L403") (pin "P$1") (pinfunction "P$1_P$1") (pintype "bidirectional"))
      (node (ref "L404") (pin "P$1") (pinfunction "P$1_P$1") (pintype "bidirectional"))
      (node (ref "U602") (pin "8") (pinfunction "OUT_8") (pintype "bidirectional"))
    )
    (net (code "242") (name "VDD_5V_SENS") (class "Default")
      (node (ref "R609") (pin "P$1") (pinfunction "1_P$1") (pintype "passive"))
      (node (ref "R610") (pin "P$1") (pinfunction "1_P$1") (pintype "passive"))
      (node (ref "U101") (pin "29") (pinfunction "PA4_29") (pintype "bidirectional"))
    )
    (net (code "243") (name "VDD_SERVO") (class "Default")
      (node (ref "C1102") (pin "P$1") (pinfunction "1_P$1") (pintype "passive"))
      (node (ref "D1") (pin "ANODE") (pinfunction "A_ANODE") (pintype "passive"))
      (node (ref "J901") (pin "11") (pinfunction "S_11") (pintype "passive"))
      (node (ref "J901") (pin "14") (pinfunction "S_14") (pintype "passive"))
      (node (ref "J901") (pin "17") (pinfunction "S_17") (pintype "passive"))
      (node (ref "J901") (pin "20") (pinfunction "S_20") (pintype "passive"))
      (node (ref "J901") (pin "23") (pinfunction "S_23") (pintype "passive"))
      (node (ref "J901") (pin "26") (pinfunction "S_26") (pintype "passive"))
      (node (ref "J901") (pin "29") (pinfunction "S_29") (pintype "passive"))
      (node (ref "J901") (pin "32") (pinfunction "S_32") (pintype "passive"))
      (node (ref "J901") (pin "35") (pinfunction "S_35") (pintype "passive"))
      (node (ref "J901") (pin "38") (pinfunction "S_38") (pintype "passive"))
      (node (ref "J901") (pin "41") (pinfunction "S_41") (pintype "passive"))
      (node (ref "J901") (pin "44") (pinfunction "S_44") (pintype "passive"))
      (node (ref "J901") (pin "47") (pinfunction "S_47") (pintype "passive"))
      (node (ref "J901") (pin "5") (pinfunction "S_5") (pintype "passive"))
      (node (ref "J901") (pin "8") (pinfunction "S_8") (pintype "passive"))
      (node (ref "R1109") (pin "P$1") (pinfunction "1_P$1") (pintype "passive"))
      (node (ref "R922") (pin "P$2") (pinfunction "2_P$2") (pintype "passive"))
      (node (ref "U1101") (pin "P$20") (pinfunction "V2_P$20") (pintype "bidirectional"))
      (node (ref "U1103") (pin "P$7") (pinfunction "D_P$7") (pintype "passive"))
      (node (ref "U1103") (pin "P$8") (pinfunction "D_P$8") (pintype "passive"))
      (node (ref "VDD_SERVO") (pin "P$1") (pinfunction "P$1_P$1") (pintype "passive"))
    )
    (net (code "244") (name "VDD_SERVO_IN") (class "Default")
      (node (ref "L901") (pin "P$2") (pinfunction "P$2_P$2") (pintype "bidirectional"))
      (node (ref "U1001") (pin "1") (pinfunction "IN_1") (pintype "bidirectional"))
    )
    (net (code "245") (name "VDD_SERVO_SENS") (class "Default")
      (node (ref "R918") (pin "P$1") (pinfunction "1_P$1") (pintype "passive"))
      (node (ref "R919") (pin "P$2") (pinfunction "2_P$2") (pintype "passive"))
      (node (ref "U801") (pin "14") (pinfunction "PA4_14") (pintype "bidirectional"))
    )
    (net (code "246") (name "unconnected-(J301-4-PadID)") (class "Default")
      (node (ref "J301") (pin "ID") (pinfunction "4_ID") (pintype "passive"))
    )
    (net (code "247") (name "unconnected-(JX301A-S-Pad10)") (class "Default")
      (node (ref "JX301") (pin "10") (pinfunction "S_10") (pintype "passive"))
    )
    (net (code "248") (name "unconnected-(JX301F-S-Pad8)") (class "Default")
      (node (ref "JX301") (pin "8") (pinfunction "S_8") (pintype "passive"))
    )
    (net (code "249") (name "unconnected-(JX802A-S-Pad10)") (class "Default")
      (node (ref "JX802") (pin "10") (pinfunction "S_10") (pintype "passive"))
    )
    (net (code "250") (name "unconnected-(JX802F-S-Pad8)") (class "Default")
      (node (ref "JX802") (pin "8") (pinfunction "S_8") (pintype "passive"))
    )
    (net (code "251") (name "unconnected-(U101I-PC1-Pad16)") (class "Default")
      (node (ref "U101") (pin "16") (pinfunction "PC1_16") (pintype "bidirectional"))
    )
    (net (code "252") (name "unconnected-(U202-A1-Pad1)") (class "Default")
      (node (ref "U202") (pin "1") (pinfunction "A1_1") (pintype "bidirectional"))
    )
    (net (code "253") (name "unconnected-(U202-A2-Pad3)") (class "Default")
      (node (ref "U202") (pin "3") (pinfunction "A2_3") (pintype "bidirectional"))
    )
    (net (code "254") (name "unconnected-(U202-B1-Pad20)") (class "Default")
      (node (ref "U202") (pin "20") (pinfunction "B1_20") (pintype "bidirectional"))
    )
    (net (code "255") (name "unconnected-(U202-B2-Pad18)") (class "Default")
      (node (ref "U202") (pin "18") (pinfunction "B2_18") (pintype "bidirectional"))
    )
    (net (code "256") (name "unconnected-(U501-INT1-Pad7)") (class "Default")
      (node (ref "U501") (pin "7") (pinfunction "INT1_7") (pintype "output"))
    )
    (net (code "257") (name "unconnected-(U502-DEN-Pad8)") (class "Default")
      (node (ref "U502") (pin "8") (pinfunction "DEN_8") (pintype "bidirectional"))
    )
    (net (code "258") (name "unconnected-(U502-INT1-Pad7)") (class "Default")
      (node (ref "U502") (pin "7") (pinfunction "INT1_7") (pintype "bidirectional"))
    )
    (net (code "259") (name "unconnected-(U505-AUX_CL-Pad7)") (class "Default")
      (node (ref "U505") (pin "7") (pinfunction "AUX_CL_7") (pintype "bidirectional"))
    )
    (net (code "260") (name "unconnected-(U505-AUX_DA-Pad6)") (class "Default")
      (node (ref "U505") (pin "6") (pinfunction "AUX_DA_6") (pintype "bidirectional"))
    )
    (net (code "261") (name "unconnected-(U505-CLKOUT-Pad22)") (class "Default")
      (node (ref "U505") (pin "22") (pinfunction "CLKOUT_22") (pintype "bidirectional"))
    )
    (net (code "262") (name "unconnected-(U505-FSYNC-Pad11)") (class "Default")
      (node (ref "U505") (pin "11") (pinfunction "FSYNC_11") (pintype "bidirectional"))
    )
    (net (code "263") (name "unconnected-(U505-NC1-Pad2)") (class "Default")
      (node (ref "U505") (pin "2") (pinfunction "NC1_2") (pintype "bidirectional"))
    )
    (net (code "264") (name "unconnected-(U505-NC2-Pad3)") (class "Default")
      (node (ref "U505") (pin "3") (pinfunction "NC2_3") (pintype "bidirectional"))
    )
    (net (code "265") (name "unconnected-(U505-NC3-Pad4)") (class "Default")
      (node (ref "U505") (pin "4") (pinfunction "NC3_4") (pintype "bidirectional"))
    )
    (net (code "266") (name "unconnected-(U505-NC4-Pad5)") (class "Default")
      (node (ref "U505") (pin "5") (pinfunction "NC4_5") (pintype "bidirectional"))
    )
    (net (code "267") (name "unconnected-(U505-NC5-Pad14)") (class "Default")
      (node (ref "U505") (pin "14") (pinfunction "NC5_14") (pintype "bidirectional"))
    )
    (net (code "268") (name "unconnected-(U505-NC6-Pad15)") (class "Default")
      (node (ref "U505") (pin "15") (pinfunction "NC6_15") (pintype "bidirectional"))
    )
    (net (code "269") (name "unconnected-(U505-NC7-Pad16)") (class "Default")
      (node (ref "U505") (pin "16") (pinfunction "NC7_16") (pintype "bidirectional"))
    )
    (net (code "270") (name "unconnected-(U505-NC8-Pad17)") (class "Default")
      (node (ref "U505") (pin "17") (pinfunction "NC8_17") (pintype "bidirectional"))
    )
    (net (code "271") (name "unconnected-(U505-RESV1-Pad19)") (class "Default")
      (node (ref "U505") (pin "19") (pinfunction "RESV1_19") (pintype "bidirectional"))
    )
    (net (code "272") (name "unconnected-(U505-RESV2-Pad21)") (class "Default")
      (node (ref "U505") (pin "21") (pinfunction "RESV2_21") (pintype "bidirectional"))
    )
    (net (code "273") (name "unconnected-(U506-CSB1-Pad4)") (class "Default")
      (node (ref "U506") (pin "4") (pinfunction "CSB1_4") (pintype "bidirectional"))
    )
    (net (code "274") (name "unconnected-(U801B-PA11-Pad32)") (class "Default")
      (node (ref "U801") (pin "32") (pinfunction "PA11_32") (pintype "bidirectional"))
    )
    (net (code "275") (name "unconnected-(U801D-PB12-Pad25)") (class "Default")
      (node (ref "U801") (pin "25") (pinfunction "PB12_25") (pintype "bidirectional"))
    )
    (net (code "276") (name "unconnected-(U801E-PB6-Pad42)") (class "Default")
      (node (ref "U801") (pin "42") (pinfunction "PB6_42") (pintype "bidirectional"))
    )
    (net (code "277") (name "unconnected-(U801E-PB7-Pad43)") (class "Default")
      (node (ref "U801") (pin "43") (pinfunction "PB7_43") (pintype "bidirectional"))
    )
    (net (code "278") (name "unconnected-(U801F-PC14-Pad3)") (class "Default")
      (node (ref "U801") (pin "3") (pinfunction "PC14_3") (pintype "bidirectional"))
    )
    (net (code "279") (name "unconnected-(U801F-PC15-Pad4)") (class "Default")
      (node (ref "U801") (pin "4") (pinfunction "PC15_4") (pintype "bidirectional"))
    )
    (net (code "280") (name "unconnected-(U901-A7-Pad8)") (class "Default")
      (node (ref "U901") (pin "8") (pinfunction "A7_8") (pintype "bidirectional"))
    )
    (net (code "281") (name "unconnected-(U901-A8-Pad9)") (class "Default")
      (node (ref "U901") (pin "9") (pinfunction "A8_9") (pintype "bidirectional"))
    )
    (net (code "282") (name "unconnected-(U901-B7-Pad13)") (class "Default")
      (node (ref "U901") (pin "13") (pinfunction "B7_13") (pintype "bidirectional"))
    )
    (net (code "283") (name "unconnected-(U901-B8-Pad12)") (class "Default")
      (node (ref "U901") (pin "12") (pinfunction "B8_12") (pintype "bidirectional"))
    )
    (net (code "284") (name "unconnected-(U1101-CAS-PadP$11)") (class "Default")
      (node (ref "U1101") (pin "P$11") (pinfunction "CAS_P$11") (pintype "bidirectional"))
    )
    (net (code "285") (name "unconnected-(U1101-EN-PadP$22)") (class "Default")
      (node (ref "U1101") (pin "P$22") (pinfunction "EN_P$22") (pintype "bidirectional"))
    )
    (net (code "286") (name "unconnected-(U1101-~{SHDN}-PadP$23)") (class "Default")
      (node (ref "U1101") (pin "P$23") (pinfunction "~{SHDN}_P$23") (pintype "bidirectional"))
    )
    (net (code "287") (name "~{ACCEL_MAG_CS}") (class "Default")
      (node (ref "U101") (pin "9") (pinfunction "PC15_9") (pintype "bidirectional"))
      (node (ref "U504") (pin "8") (pinfunction "CS_8") (pintype "bidirectional"))
      (node (ref "X503") (pin "6") (pinfunction "S_6") (pintype "passive"))
    )
    (net (code "288") (name "~{BARO_CS}") (class "Default")
      (node (ref "U101") (pin "88") (pinfunction "PD7_88") (pintype "bidirectional"))
      (node (ref "U506") (pin "5") (pinfunction "CSB2_5") (pintype "bidirectional"))
    )
    (net (code "289") (name "~{FMU-LED_AMBER}") (class "Default")
      (node (ref "R707") (pin "P$1") (pinfunction "1_P$1") (pintype "passive"))
      (node (ref "U101") (pin "43") (pinfunction "PE12_43") (pintype "bidirectional"))
    )
    (net (code "290") (name "~{FRAM_CS}") (class "Default")
      (node (ref "U101") (pin "57") (pinfunction "PD10_57") (pintype "bidirectional"))
      (node (ref "U102") (pin "1") (pinfunction "~{S}_1") (pintype "bidirectional"))
    )
    (net (code "291") (name "~{GYRO_CS}") (class "Default")
      (node (ref "U101") (pin "7") (pinfunction "PC13_7") (pintype "bidirectional"))
      (node (ref "U501") (pin "5") (pinfunction "CS_5") (pintype "input"))
      (node (ref "U502") (pin "5") (pinfunction "CS_5") (pintype "bidirectional"))
      (node (ref "X503") (pin "7") (pinfunction "S_7") (pintype "passive"))
    )
    (net (code "292") (name "~{IO-LED_AMBER}") (class "Default")
      (node (ref "R709") (pin "P$1") (pinfunction "1_P$1") (pintype "passive"))
      (node (ref "U801") (pin "28") (pinfunction "PB15_28") (pintype "bidirectional"))
    )
    (net (code "293") (name "~{IO-LED_BLUE}") (class "Default")
      (node (ref "R712") (pin "P$1") (pinfunction "1_P$1") (pintype "passive"))
      (node (ref "U801") (pin "27") (pinfunction "PB14_27") (pintype "bidirectional"))
    )
    (net (code "294") (name "~{IO-LED_SAFETY}") (class "Default")
      (node (ref "R710") (pin "P$2") (pinfunction "2_P$2") (pintype "passive"))
      (node (ref "U801") (pin "26") (pinfunction "PB13_26") (pintype "bidirectional"))
    )
    (net (code "295") (name "~{MPU_CS}") (class "Default")
      (node (ref "U101") (pin "17") (pinfunction "PC2_17") (pintype "bidirectional"))
      (node (ref "U505") (pin "8") (pinfunction "/CS_8") (pintype "bidirectional"))
    )
    (net (code "296") (name "~{SBUS_OUTPUT_EN}") (class "Default")
      (node (ref "U801") (pin "40") (pinfunction "PB4_40") (pintype "bidirectional"))
      (node (ref "U903") (pin "7") (pinfunction "~{2OE}_7") (pintype "input"))
    )
    (net (code "297") (name "~{SPI_EXT_NSS}") (class "Default")
      (node (ref "J403") (pin "5") (pinfunction "5_5") (pintype "passive"))
      (node (ref "U101") (pin "3") (pinfunction "PE4_3") (pintype "bidirectional"))
    )
    (net (code "298") (name "~{VBUS_VALID}") (class "Default")
      (node (ref "!VBUS_VALID") (pin "P$1") (pinfunction "P$1_P$1") (pintype "passive"))
      (node (ref "RN1101") (pin "2") (pinfunction "1_2") (pintype "passive"))
      (node (ref "U101") (pin "15") (pinfunction "PC0_15") (pintype "bidirectional"))
      (node (ref "U1101") (pin "P$9") (pinfunction "~{VALID3}_P$9") (pintype "bidirectional"))
    )
    (net (code "299") (name "~{VDD_5V_HIPOWER_OC}") (class "Default")
      (node (ref "R602") (pin "P$1") (pinfunction "1_P$1") (pintype "passive"))
      (node (ref "U101") (pin "41") (pinfunction "PE10_41") (pintype "bidirectional"))
      (node (ref "U601") (pin "4") (pinfunction "~{FAULT}_4") (pintype "bidirectional"))
    )
    (net (code "300") (name "~{VDD_5V_PERIPH_EN}") (class "Default")
      (node (ref "R615") (pin "P$1") (pinfunction "1_P$1") (pintype "passive"))
      (node (ref "U101") (pin "67") (pinfunction "PA8_67") (pintype "bidirectional"))
      (node (ref "U601") (pin "5") (pinfunction "~{CE}_5") (pintype "bidirectional"))
      (node (ref "U602") (pin "5") (pinfunction "~{CE}_5") (pintype "bidirectional"))
    )
    (net (code "301") (name "~{VDD_5V_PERIPH_OC}") (class "Default")
      (node (ref "R604") (pin "P$1") (pinfunction "1_P$1") (pintype "passive"))
      (node (ref "U101") (pin "46") (pinfunction "PE15_46") (pintype "bidirectional"))
      (node (ref "U602") (pin "4") (pinfunction "~{FAULT}_4") (pintype "bidirectional"))
    )
    (net (code "302") (name "~{VDD_BRICK_VALID}") (class "Default")
      (node (ref "!VDD_BRICK_VALID") (pin "P$1") (pinfunction "P$1_P$1") (pintype "passive"))
      (node (ref "RN1101") (pin "4") (pinfunction "1_4") (pintype "passive"))
      (node (ref "U101") (pin "91") (pinfunction "PB5_91") (pintype "bidirectional"))
      (node (ref "U1101") (pin "P$7") (pinfunction "~{VALID1}_P$7") (pintype "bidirectional"))
    )
    (net (code "303") (name "~{VDD_SERVO_VALID}") (class "Default")
      (node (ref "!VDD_SERVO_VALID") (pin "P$1") (pinfunction "P$1_P$1") (pintype "passive"))
      (node (ref "RN1101") (pin "3") (pinfunction "1_3") (pintype "passive"))
      (node (ref "U101") (pin "93") (pinfunction "PB7_93") (pintype "bidirectional"))
      (node (ref "U1101") (pin "P$8") (pinfunction "~{VALID2}_P$8") (pintype "bidirectional"))
    )
  )
)
